# SCH_Hall_sensor_array_2022-12-20.net
KiCad netlist of a schematic drawn in EasyEDA
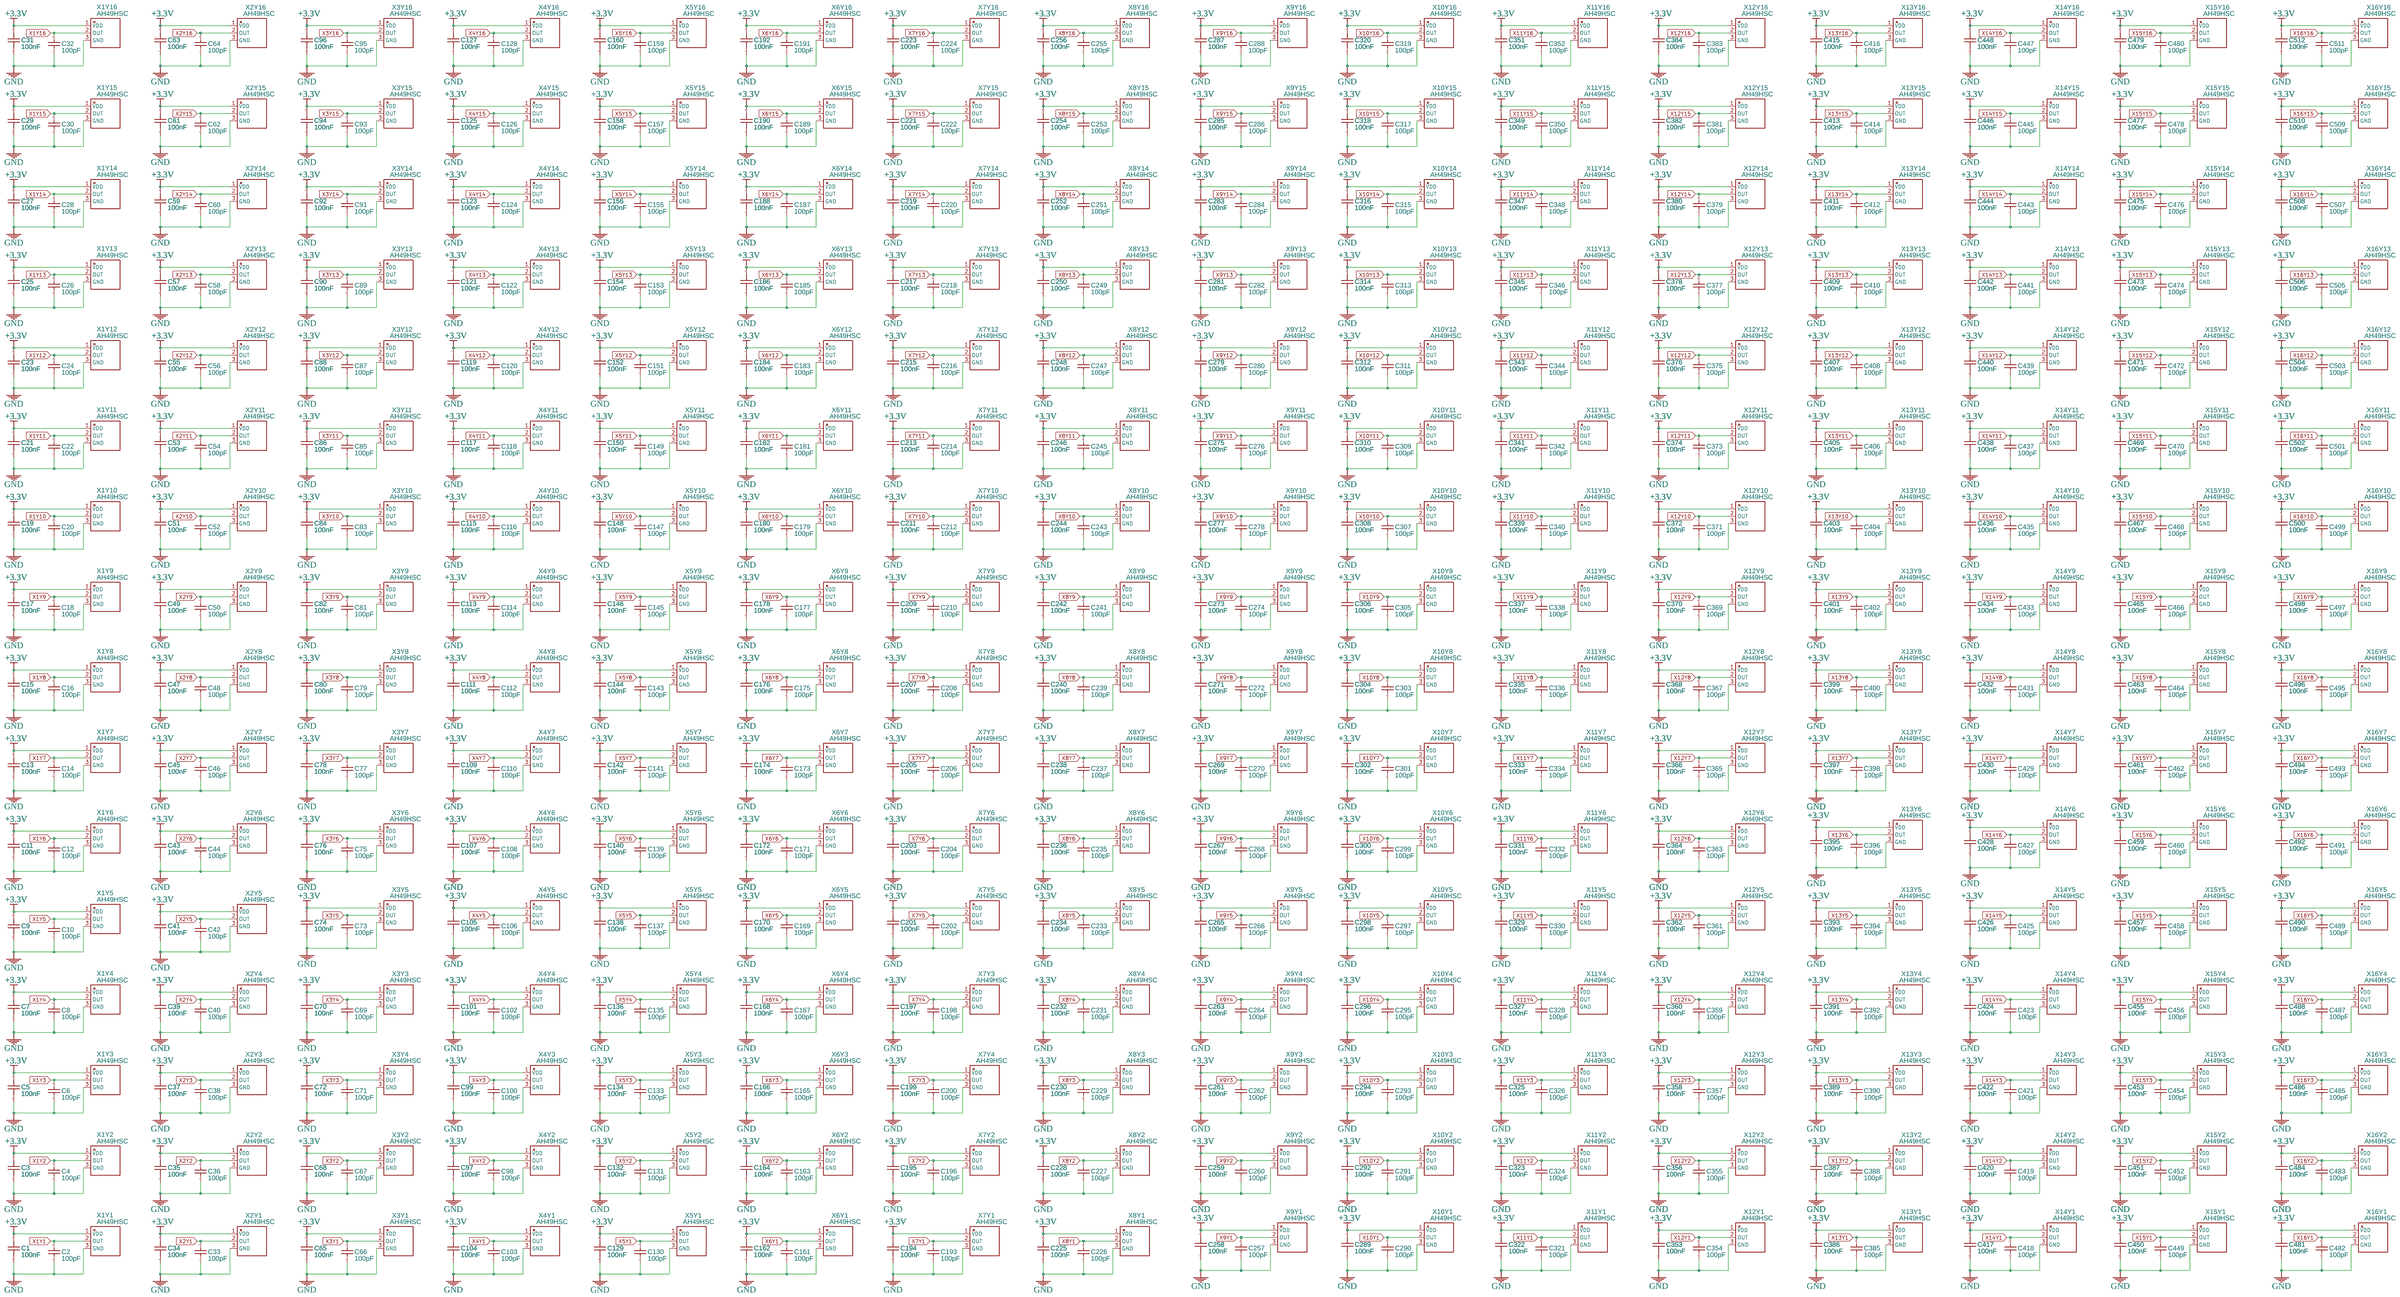
[diagram p0: schematic sheet]

(export (version "E")
  (design (tool "Eeschema 10.0.6"))
  (components
    (comp (ref "C1")
      (value "100nF")
      (fields
        (field (name "BOM_Manufacturer Part") "CL10B104KB8NNNC")
        (field (name "BOM_Supplier Part") "C1591")
      )
      (libsource (lib "") (part "CL10B104KB8NNNC"))
    )
    (comp (ref "C2")
      (value "100pF")
      (fields
        (field (name "BOM_Manufacturer Part") "CL10C101JB8NNNC")
        (field (name "BOM_Supplier Part") "C14858")
      )
      (libsource (lib "") (part "CL10C101JB8NNNC"))
    )
    (comp (ref "C3")
      (value "100nF")
      (fields
        (field (name "BOM_Manufacturer Part") "CL10B104KB8NNNC")
        (field (name "BOM_Supplier Part") "C1591")
      )
      (libsource (lib "") (part "CL10B104KB8NNNC"))
    )
    (comp (ref "C4")
      (value "100pF")
      (fields
        (field (name "BOM_Manufacturer Part") "CL10C101JB8NNNC")
        (field (name "BOM_Supplier Part") "C14858")
      )
      (libsource (lib "") (part "CL10C101JB8NNNC"))
    )
    (comp (ref "C5")
      (value "100nF")
      (fields
        (field (name "BOM_Manufacturer Part") "CL10B104KB8NNNC")
        (field (name "BOM_Supplier Part") "C1591")
      )
      (libsource (lib "") (part "CL10B104KB8NNNC"))
    )
    (comp (ref "C6")
      (value "100pF")
      (fields
        (field (name "BOM_Manufacturer Part") "CL10C101JB8NNNC")
        (field (name "BOM_Supplier Part") "C14858")
      )
      (libsource (lib "") (part "CL10C101JB8NNNC"))
    )
    (comp (ref "C7")
      (value "100nF")
      (fields
        (field (name "BOM_Manufacturer Part") "CL10B104KB8NNNC")
        (field (name "BOM_Supplier Part") "C1591")
      )
      (libsource (lib "") (part "CL10B104KB8NNNC"))
    )
    (comp (ref "C8")
      (value "100pF")
      (fields
        (field (name "BOM_Manufacturer Part") "CL10C101JB8NNNC")
        (field (name "BOM_Supplier Part") "C14858")
      )
      (libsource (lib "") (part "CL10C101JB8NNNC"))
    )
    (comp (ref "C9")
      (value "100nF")
      (fields
        (field (name "BOM_Manufacturer Part") "CL10B104KB8NNNC")
        (field (name "BOM_Supplier Part") "C1591")
      )
      (libsource (lib "") (part "CL10B104KB8NNNC"))
    )
    (comp (ref "C10")
      (value "100pF")
      (fields
        (field (name "BOM_Manufacturer Part") "CL10C101JB8NNNC")
        (field (name "BOM_Supplier Part") "C14858")
      )
      (libsource (lib "") (part "CL10C101JB8NNNC"))
    )
    (comp (ref "C11")
      (value "100nF")
      (fields
        (field (name "BOM_Manufacturer Part") "CL10B104KB8NNNC")
        (field (name "BOM_Supplier Part") "C1591")
      )
      (libsource (lib "") (part "CL10B104KB8NNNC"))
    )
    (comp (ref "C12")
      (value "100pF")
      (fields
        (field (name "BOM_Manufacturer Part") "CL10C101JB8NNNC")
        (field (name "BOM_Supplier Part") "C14858")
      )
      (libsource (lib "") (part "CL10C101JB8NNNC"))
    )
    (comp (ref "C13")
      (value "100nF")
      (fields
        (field (name "BOM_Manufacturer Part") "CL10B104KB8NNNC")
        (field (name "BOM_Supplier Part") "C1591")
      )
      (libsource (lib "") (part "CL10B104KB8NNNC"))
    )
    (comp (ref "C14")
      (value "100pF")
      (fields
        (field (name "BOM_Manufacturer Part") "CL10C101JB8NNNC")
        (field (name "BOM_Supplier Part") "C14858")
      )
      (libsource (lib "") (part "CL10C101JB8NNNC"))
    )
    (comp (ref "C15")
      (value "100nF")
      (fields
        (field (name "BOM_Manufacturer Part") "CL10B104KB8NNNC")
        (field (name "BOM_Supplier Part") "C1591")
      )
      (libsource (lib "") (part "CL10B104KB8NNNC"))
    )
    (comp (ref "C16")
      (value "100pF")
      (fields
        (field (name "BOM_Manufacturer Part") "CL10C101JB8NNNC")
        (field (name "BOM_Supplier Part") "C14858")
      )
      (libsource (lib "") (part "CL10C101JB8NNNC"))
    )
    (comp (ref "C17")
      (value "100nF")
      (fields
        (field (name "BOM_Manufacturer Part") "CL10B104KB8NNNC")
        (field (name "BOM_Supplier Part") "C1591")
      )
      (libsource (lib "") (part "CL10B104KB8NNNC"))
    )
    (comp (ref "C18")
      (value "100pF")
      (fields
        (field (name "BOM_Manufacturer Part") "CL10C101JB8NNNC")
        (field (name "BOM_Supplier Part") "C14858")
      )
      (libsource (lib "") (part "CL10C101JB8NNNC"))
    )
    (comp (ref "C19")
      (value "100nF")
      (fields
        (field (name "BOM_Manufacturer Part") "CL10B104KB8NNNC")
        (field (name "BOM_Supplier Part") "C1591")
      )
      (libsource (lib "") (part "CL10B104KB8NNNC"))
    )
    (comp (ref "C20")
      (value "100pF")
      (fields
        (field (name "BOM_Manufacturer Part") "CL10C101JB8NNNC")
        (field (name "BOM_Supplier Part") "C14858")
      )
      (libsource (lib "") (part "CL10C101JB8NNNC"))
    )
    (comp (ref "C21")
      (value "100nF")
      (fields
        (field (name "BOM_Manufacturer Part") "CL10B104KB8NNNC")
        (field (name "BOM_Supplier Part") "C1591")
      )
      (libsource (lib "") (part "CL10B104KB8NNNC"))
    )
    (comp (ref "C22")
      (value "100pF")
      (fields
        (field (name "BOM_Manufacturer Part") "CL10C101JB8NNNC")
        (field (name "BOM_Supplier Part") "C14858")
      )
      (libsource (lib "") (part "CL10C101JB8NNNC"))
    )
    (comp (ref "C23")
      (value "100nF")
      (fields
        (field (name "BOM_Manufacturer Part") "CL10B104KB8NNNC")
        (field (name "BOM_Supplier Part") "C1591")
      )
      (libsource (lib "") (part "CL10B104KB8NNNC"))
    )
    (comp (ref "C24")
      (value "100pF")
      (fields
        (field (name "BOM_Manufacturer Part") "CL10C101JB8NNNC")
        (field (name "BOM_Supplier Part") "C14858")
      )
      (libsource (lib "") (part "CL10C101JB8NNNC"))
    )
    (comp (ref "C25")
      (value "100nF")
      (fields
        (field (name "BOM_Manufacturer Part") "CL10B104KB8NNNC")
        (field (name "BOM_Supplier Part") "C1591")
      )
      (libsource (lib "") (part "CL10B104KB8NNNC"))
    )
    (comp (ref "C26")
      (value "100pF")
      (fields
        (field (name "BOM_Manufacturer Part") "CL10C101JB8NNNC")
        (field (name "BOM_Supplier Part") "C14858")
      )
      (libsource (lib "") (part "CL10C101JB8NNNC"))
    )
    (comp (ref "C27")
      (value "100nF")
      (fields
        (field (name "BOM_Manufacturer Part") "CL10B104KB8NNNC")
        (field (name "BOM_Supplier Part") "C1591")
      )
      (libsource (lib "") (part "CL10B104KB8NNNC"))
    )
    (comp (ref "C28")
      (value "100pF")
      (fields
        (field (name "BOM_Manufacturer Part") "CL10C101JB8NNNC")
        (field (name "BOM_Supplier Part") "C14858")
      )
      (libsource (lib "") (part "CL10C101JB8NNNC"))
    )
    (comp (ref "C29")
      (value "100nF")
      (fields
        (field (name "BOM_Manufacturer Part") "CL10B104KB8NNNC")
        (field (name "BOM_Supplier Part") "C1591")
      )
      (libsource (lib "") (part "CL10B104KB8NNNC"))
    )
    (comp (ref "C30")
      (value "100pF")
      (fields
        (field (name "BOM_Manufacturer Part") "CL10C101JB8NNNC")
        (field (name "BOM_Supplier Part") "C14858")
      )
      (libsource (lib "") (part "CL10C101JB8NNNC"))
    )
    (comp (ref "C31")
      (value "100nF")
      (fields
        (field (name "BOM_Manufacturer Part") "CL10B104KB8NNNC")
        (field (name "BOM_Supplier Part") "C1591")
      )
      (libsource (lib "") (part "CL10B104KB8NNNC"))
    )
    (comp (ref "C32")
      (value "100pF")
      (fields
        (field (name "BOM_Manufacturer Part") "CL10C101JB8NNNC")
        (field (name "BOM_Supplier Part") "C14858")
      )
      (libsource (lib "") (part "CL10C101JB8NNNC"))
    )
    (comp (ref "C33")
      (value "100pF")
      (fields
        (field (name "BOM_Manufacturer Part") "CL10C101JB8NNNC")
        (field (name "BOM_Supplier Part") "C14858")
      )
      (libsource (lib "") (part "CL10C101JB8NNNC"))
    )
    (comp (ref "C34")
      (value "100nF")
      (fields
        (field (name "BOM_Manufacturer Part") "CL10B104KB8NNNC")
        (field (name "BOM_Supplier Part") "C1591")
      )
      (libsource (lib "") (part "CL10B104KB8NNNC"))
    )
    (comp (ref "C35")
      (value "100nF")
      (fields
        (field (name "BOM_Manufacturer Part") "CL10B104KB8NNNC")
        (field (name "BOM_Supplier Part") "C1591")
      )
      (libsource (lib "") (part "CL10B104KB8NNNC"))
    )
    (comp (ref "C36")
      (value "100pF")
      (fields
        (field (name "BOM_Manufacturer Part") "CL10C101JB8NNNC")
        (field (name "BOM_Supplier Part") "C14858")
      )
      (libsource (lib "") (part "CL10C101JB8NNNC"))
    )
    (comp (ref "C37")
      (value "100nF")
      (fields
        (field (name "BOM_Manufacturer Part") "CL10B104KB8NNNC")
        (field (name "BOM_Supplier Part") "C1591")
      )
      (libsource (lib "") (part "CL10B104KB8NNNC"))
    )
    (comp (ref "C38")
      (value "100pF")
      (fields
        (field (name "BOM_Manufacturer Part") "CL10C101JB8NNNC")
        (field (name "BOM_Supplier Part") "C14858")
      )
      (libsource (lib "") (part "CL10C101JB8NNNC"))
    )
    (comp (ref "C39")
      (value "100nF")
      (fields
        (field (name "BOM_Manufacturer Part") "CL10B104KB8NNNC")
        (field (name "BOM_Supplier Part") "C1591")
      )
      (libsource (lib "") (part "CL10B104KB8NNNC"))
    )
    (comp (ref "C40")
      (value "100pF")
      (fields
        (field (name "BOM_Manufacturer Part") "CL10C101JB8NNNC")
        (field (name "BOM_Supplier Part") "C14858")
      )
      (libsource (lib "") (part "CL10C101JB8NNNC"))
    )
    (comp (ref "C41")
      (value "100nF")
      (fields
        (field (name "BOM_Manufacturer Part") "CL10B104KB8NNNC")
        (field (name "BOM_Supplier Part") "C1591")
      )
      (libsource (lib "") (part "CL10B104KB8NNNC"))
    )
    (comp (ref "C42")
      (value "100pF")
      (fields
        (field (name "BOM_Manufacturer Part") "CL10C101JB8NNNC")
        (field (name "BOM_Supplier Part") "C14858")
      )
      (libsource (lib "") (part "CL10C101JB8NNNC"))
    )
    (comp (ref "C43")
      (value "100nF")
      (fields
        (field (name "BOM_Manufacturer Part") "CL10B104KB8NNNC")
        (field (name "BOM_Supplier Part") "C1591")
      )
      (libsource (lib "") (part "CL10B104KB8NNNC"))
    )
    (comp (ref "C44")
      (value "100pF")
      (fields
        (field (name "BOM_Manufacturer Part") "CL10C101JB8NNNC")
        (field (name "BOM_Supplier Part") "C14858")
      )
      (libsource (lib "") (part "CL10C101JB8NNNC"))
    )
    (comp (ref "C45")
      (value "100nF")
      (fields
        (field (name "BOM_Manufacturer Part") "CL10B104KB8NNNC")
        (field (name "BOM_Supplier Part") "C1591")
      )
      (libsource (lib "") (part "CL10B104KB8NNNC"))
    )
    (comp (ref "C46")
      (value "100pF")
      (fields
        (field (name "BOM_Manufacturer Part") "CL10C101JB8NNNC")
        (field (name "BOM_Supplier Part") "C14858")
      )
      (libsource (lib "") (part "CL10C101JB8NNNC"))
    )
    (comp (ref "C47")
      (value "100nF")
      (fields
        (field (name "BOM_Manufacturer Part") "CL10B104KB8NNNC")
        (field (name "BOM_Supplier Part") "C1591")
      )
      (libsource (lib "") (part "CL10B104KB8NNNC"))
    )
    (comp (ref "C48")
      (value "100pF")
      (fields
        (field (name "BOM_Manufacturer Part") "CL10C101JB8NNNC")
        (field (name "BOM_Supplier Part") "C14858")
      )
      (libsource (lib "") (part "CL10C101JB8NNNC"))
    )
    (comp (ref "C49")
      (value "100nF")
      (fields
        (field (name "BOM_Manufacturer Part") "CL10B104KB8NNNC")
        (field (name "BOM_Supplier Part") "C1591")
      )
      (libsource (lib "") (part "CL10B104KB8NNNC"))
    )
    (comp (ref "C50")
      (value "100pF")
      (fields
        (field (name "BOM_Manufacturer Part") "CL10C101JB8NNNC")
        (field (name "BOM_Supplier Part") "C14858")
      )
      (libsource (lib "") (part "CL10C101JB8NNNC"))
    )
    (comp (ref "C51")
      (value "100nF")
      (fields
        (field (name "BOM_Manufacturer Part") "CL10B104KB8NNNC")
        (field (name "BOM_Supplier Part") "C1591")
      )
      (libsource (lib "") (part "CL10B104KB8NNNC"))
    )
    (comp (ref "C52")
      (value "100pF")
      (fields
        (field (name "BOM_Manufacturer Part") "CL10C101JB8NNNC")
        (field (name "BOM_Supplier Part") "C14858")
      )
      (libsource (lib "") (part "CL10C101JB8NNNC"))
    )
    (comp (ref "C53")
      (value "100nF")
      (fields
        (field (name "BOM_Manufacturer Part") "CL10B104KB8NNNC")
        (field (name "BOM_Supplier Part") "C1591")
      )
      (libsource (lib "") (part "CL10B104KB8NNNC"))
    )
    (comp (ref "C54")
      (value "100pF")
      (fields
        (field (name "BOM_Manufacturer Part") "CL10C101JB8NNNC")
        (field (name "BOM_Supplier Part") "C14858")
      )
      (libsource (lib "") (part "CL10C101JB8NNNC"))
    )
    (comp (ref "C55")
      (value "100nF")
      (fields
        (field (name "BOM_Manufacturer Part") "CL10B104KB8NNNC")
        (field (name "BOM_Supplier Part") "C1591")
      )
      (libsource (lib "") (part "CL10B104KB8NNNC"))
    )
    (comp (ref "C56")
      (value "100pF")
      (fields
        (field (name "BOM_Manufacturer Part") "CL10C101JB8NNNC")
        (field (name "BOM_Supplier Part") "C14858")
      )
      (libsource (lib "") (part "CL10C101JB8NNNC"))
    )
    (comp (ref "C57")
      (value "100nF")
      (fields
        (field (name "BOM_Manufacturer Part") "CL10B104KB8NNNC")
        (field (name "BOM_Supplier Part") "C1591")
      )
      (libsource (lib "") (part "CL10B104KB8NNNC"))
    )
    (comp (ref "C58")
      (value "100pF")
      (fields
        (field (name "BOM_Manufacturer Part") "CL10C101JB8NNNC")
        (field (name "BOM_Supplier Part") "C14858")
      )
      (libsource (lib "") (part "CL10C101JB8NNNC"))
    )
    (comp (ref "C59")
      (value "100nF")
      (fields
        (field (name "BOM_Manufacturer Part") "CL10B104KB8NNNC")
        (field (name "BOM_Supplier Part") "C1591")
      )
      (libsource (lib "") (part "CL10B104KB8NNNC"))
    )
    (comp (ref "C60")
      (value "100pF")
      (fields
        (field (name "BOM_Manufacturer Part") "CL10C101JB8NNNC")
        (field (name "BOM_Supplier Part") "C14858")
      )
      (libsource (lib "") (part "CL10C101JB8NNNC"))
    )
    (comp (ref "C61")
      (value "100nF")
      (fields
        (field (name "BOM_Manufacturer Part") "CL10B104KB8NNNC")
        (field (name "BOM_Supplier Part") "C1591")
      )
      (libsource (lib "") (part "CL10B104KB8NNNC"))
    )
    (comp (ref "C62")
      (value "100pF")
      (fields
        (field (name "BOM_Manufacturer Part") "CL10C101JB8NNNC")
        (field (name "BOM_Supplier Part") "C14858")
      )
      (libsource (lib "") (part "CL10C101JB8NNNC"))
    )
    (comp (ref "C63")
      (value "100nF")
      (fields
        (field (name "BOM_Manufacturer Part") "CL10B104KB8NNNC")
        (field (name "BOM_Supplier Part") "C1591")
      )
      (libsource (lib "") (part "CL10B104KB8NNNC"))
    )
    (comp (ref "C64")
      (value "100pF")
      (fields
        (field (name "BOM_Manufacturer Part") "CL10C101JB8NNNC")
        (field (name "BOM_Supplier Part") "C14858")
      )
      (libsource (lib "") (part "CL10C101JB8NNNC"))
    )
    (comp (ref "C65")
      (value "100nF")
      (fields
        (field (name "BOM_Manufacturer Part") "CL10B104KB8NNNC")
        (field (name "BOM_Supplier Part") "C1591")
      )
      (libsource (lib "") (part "CL10B104KB8NNNC"))
    )
    (comp (ref "C66")
      (value "100pF")
      (fields
        (field (name "BOM_Manufacturer Part") "CL10C101JB8NNNC")
        (field (name "BOM_Supplier Part") "C14858")
      )
      (libsource (lib "") (part "CL10C101JB8NNNC"))
    )
    (comp (ref "C67")
      (value "100pF")
      (fields
        (field (name "BOM_Manufacturer Part") "CL10C101JB8NNNC")
        (field (name "BOM_Supplier Part") "C14858")
      )
      (libsource (lib "") (part "CL10C101JB8NNNC"))
    )
    (comp (ref "C68")
      (value "100nF")
      (fields
        (field (name "BOM_Manufacturer Part") "CL10B104KB8NNNC")
        (field (name "BOM_Supplier Part") "C1591")
      )
      (libsource (lib "") (part "CL10B104KB8NNNC"))
    )
    (comp (ref "C69")
      (value "100pF")
      (fields
        (field (name "BOM_Manufacturer Part") "CL10C101JB8NNNC")
        (field (name "BOM_Supplier Part") "C14858")
      )
      (libsource (lib "") (part "CL10C101JB8NNNC"))
    )
    (comp (ref "C70")
      (value "100nF")
      (fields
        (field (name "BOM_Manufacturer Part") "CL10B104KB8NNNC")
        (field (name "BOM_Supplier Part") "C1591")
      )
      (libsource (lib "") (part "CL10B104KB8NNNC"))
    )
    (comp (ref "C71")
      (value "100pF")
      (fields
        (field (name "BOM_Manufacturer Part") "CL10C101JB8NNNC")
        (field (name "BOM_Supplier Part") "C14858")
      )
      (libsource (lib "") (part "CL10C101JB8NNNC"))
    )
    (comp (ref "C72")
      (value "100nF")
      (fields
        (field (name "BOM_Manufacturer Part") "CL10B104KB8NNNC")
        (field (name "BOM_Supplier Part") "C1591")
      )
      (libsource (lib "") (part "CL10B104KB8NNNC"))
    )
    (comp (ref "C73")
      (value "100pF")
      (fields
        (field (name "BOM_Manufacturer Part") "CL10C101JB8NNNC")
        (field (name "BOM_Supplier Part") "C14858")
      )
      (libsource (lib "") (part "CL10C101JB8NNNC"))
    )
    (comp (ref "C74")
      (value "100nF")
      (fields
        (field (name "BOM_Manufacturer Part") "CL10B104KB8NNNC")
        (field (name "BOM_Supplier Part") "C1591")
      )
      (libsource (lib "") (part "CL10B104KB8NNNC"))
    )
    (comp (ref "C75")
      (value "100pF")
      (fields
        (field (name "BOM_Manufacturer Part") "CL10C101JB8NNNC")
        (field (name "BOM_Supplier Part") "C14858")
      )
      (libsource (lib "") (part "CL10C101JB8NNNC"))
    )
    (comp (ref "C76")
      (value "100nF")
      (fields
        (field (name "BOM_Manufacturer Part") "CL10B104KB8NNNC")
        (field (name "BOM_Supplier Part") "C1591")
      )
      (libsource (lib "") (part "CL10B104KB8NNNC"))
    )
    (comp (ref "C77")
      (value "100pF")
      (fields
        (field (name "BOM_Manufacturer Part") "CL10C101JB8NNNC")
        (field (name "BOM_Supplier Part") "C14858")
      )
      (libsource (lib "") (part "CL10C101JB8NNNC"))
    )
    (comp (ref "C78")
      (value "100nF")
      (fields
        (field (name "BOM_Manufacturer Part") "CL10B104KB8NNNC")
        (field (name "BOM_Supplier Part") "C1591")
      )
      (libsource (lib "") (part "CL10B104KB8NNNC"))
    )
    (comp (ref "C79")
      (value "100pF")
      (fields
        (field (name "BOM_Manufacturer Part") "CL10C101JB8NNNC")
        (field (name "BOM_Supplier Part") "C14858")
      )
      (libsource (lib "") (part "CL10C101JB8NNNC"))
    )
    (comp (ref "C80")
      (value "100nF")
      (fields
        (field (name "BOM_Manufacturer Part") "CL10B104KB8NNNC")
        (field (name "BOM_Supplier Part") "C1591")
      )
      (libsource (lib "") (part "CL10B104KB8NNNC"))
    )
    (comp (ref "C81")
      (value "100pF")
      (fields
        (field (name "BOM_Manufacturer Part") "CL10C101JB8NNNC")
        (field (name "BOM_Supplier Part") "C14858")
      )
      (libsource (lib "") (part "CL10C101JB8NNNC"))
    )
    (comp (ref "C82")
      (value "100nF")
      (fields
        (field (name "BOM_Manufacturer Part") "CL10B104KB8NNNC")
        (field (name "BOM_Supplier Part") "C1591")
      )
      (libsource (lib "") (part "CL10B104KB8NNNC"))
    )
    (comp (ref "C83")
      (value "100pF")
      (fields
        (field (name "BOM_Manufacturer Part") "CL10C101JB8NNNC")
        (field (name "BOM_Supplier Part") "C14858")
      )
      (libsource (lib "") (part "CL10C101JB8NNNC"))
    )
    (comp (ref "C84")
      (value "100nF")
      (fields
        (field (name "BOM_Manufacturer Part") "CL10B104KB8NNNC")
        (field (name "BOM_Supplier Part") "C1591")
      )
      (libsource (lib "") (part "CL10B104KB8NNNC"))
    )
    (comp (ref "C85")
      (value "100pF")
      (fields
        (field (name "BOM_Manufacturer Part") "CL10C101JB8NNNC")
        (field (name "BOM_Supplier Part") "C14858")
      )
      (libsource (lib "") (part "CL10C101JB8NNNC"))
    )
    (comp (ref "C86")
      (value "100nF")
      (fields
        (field (name "BOM_Manufacturer Part") "CL10B104KB8NNNC")
        (field (name "BOM_Supplier Part") "C1591")
      )
      (libsource (lib "") (part "CL10B104KB8NNNC"))
    )
    (comp (ref "C87")
      (value "100pF")
      (fields
        (field (name "BOM_Manufacturer Part") "CL10C101JB8NNNC")
        (field (name "BOM_Supplier Part") "C14858")
      )
      (libsource (lib "") (part "CL10C101JB8NNNC"))
    )
    (comp (ref "C88")
      (value "100nF")
      (fields
        (field (name "BOM_Manufacturer Part") "CL10B104KB8NNNC")
        (field (name "BOM_Supplier Part") "C1591")
      )
      (libsource (lib "") (part "CL10B104KB8NNNC"))
    )
    (comp (ref "C89")
      (value "100pF")
      (fields
        (field (name "BOM_Manufacturer Part") "CL10C101JB8NNNC")
        (field (name "BOM_Supplier Part") "C14858")
      )
      (libsource (lib "") (part "CL10C101JB8NNNC"))
    )
    (comp (ref "C90")
      (value "100nF")
      (fields
        (field (name "BOM_Manufacturer Part") "CL10B104KB8NNNC")
        (field (name "BOM_Supplier Part") "C1591")
      )
      (libsource (lib "") (part "CL10B104KB8NNNC"))
    )
    (comp (ref "C91")
      (value "100pF")
      (fields
        (field (name "BOM_Manufacturer Part") "CL10C101JB8NNNC")
        (field (name "BOM_Supplier Part") "C14858")
      )
      (libsource (lib "") (part "CL10C101JB8NNNC"))
    )
    (comp (ref "C92")
      (value "100nF")
      (fields
        (field (name "BOM_Manufacturer Part") "CL10B104KB8NNNC")
        (field (name "BOM_Supplier Part") "C1591")
      )
      (libsource (lib "") (part "CL10B104KB8NNNC"))
    )
    (comp (ref "C93")
      (value "100pF")
      (fields
        (field (name "BOM_Manufacturer Part") "CL10C101JB8NNNC")
        (field (name "BOM_Supplier Part") "C14858")
      )
      (libsource (lib "") (part "CL10C101JB8NNNC"))
    )
    (comp (ref "C94")
      (value "100nF")
      (fields
        (field (name "BOM_Manufacturer Part") "CL10B104KB8NNNC")
        (field (name "BOM_Supplier Part") "C1591")
      )
      (libsource (lib "") (part "CL10B104KB8NNNC"))
    )
    (comp (ref "C95")
      (value "100pF")
      (fields
        (field (name "BOM_Manufacturer Part") "CL10C101JB8NNNC")
        (field (name "BOM_Supplier Part") "C14858")
      )
      (libsource (lib "") (part "CL10C101JB8NNNC"))
    )
    (comp (ref "C96")
      (value "100nF")
      (fields
        (field (name "BOM_Manufacturer Part") "CL10B104KB8NNNC")
        (field (name "BOM_Supplier Part") "C1591")
      )
      (libsource (lib "") (part "CL10B104KB8NNNC"))
    )
    (comp (ref "C97")
      (value "100nF")
      (fields
        (field (name "BOM_Manufacturer Part") "CL10B104KB8NNNC")
        (field (name "BOM_Supplier Part") "C1591")
      )
      (libsource (lib "") (part "CL10B104KB8NNNC"))
    )
    (comp (ref "C98")
      (value "100pF")
      (fields
        (field (name "BOM_Manufacturer Part") "CL10C101JB8NNNC")
        (field (name "BOM_Supplier Part") "C14858")
      )
      (libsource (lib "") (part "CL10C101JB8NNNC"))
    )
    (comp (ref "C99")
      (value "100nF")
      (fields
        (field (name "BOM_Manufacturer Part") "CL10B104KB8NNNC")
        (field (name "BOM_Supplier Part") "C1591")
      )
      (libsource (lib "") (part "CL10B104KB8NNNC"))
    )
    (comp (ref "C100")
      (value "100pF")
      (fields
        (field (name "BOM_Manufacturer Part") "CL10C101JB8NNNC")
        (field (name "BOM_Supplier Part") "C14858")
      )
      (libsource (lib "") (part "CL10C101JB8NNNC"))
    )
    (comp (ref "C101")
      (value "100nF")
      (fields
        (field (name "BOM_Manufacturer Part") "CL10B104KB8NNNC")
        (field (name "BOM_Supplier Part") "C1591")
      )
      (libsource (lib "") (part "CL10B104KB8NNNC"))
    )
    (comp (ref "C102")
      (value "100pF")
      (fields
        (field (name "BOM_Manufacturer Part") "CL10C101JB8NNNC")
        (field (name "BOM_Supplier Part") "C14858")
      )
      (libsource (lib "") (part "CL10C101JB8NNNC"))
    )
    (comp (ref "C103")
      (value "100pF")
      (fields
        (field (name "BOM_Manufacturer Part") "CL10C101JB8NNNC")
        (field (name "BOM_Supplier Part") "C14858")
      )
      (libsource (lib "") (part "CL10C101JB8NNNC"))
    )
    (comp (ref "C104")
      (value "100nF")
      (fields
        (field (name "BOM_Manufacturer Part") "CL10B104KB8NNNC")
        (field (name "BOM_Supplier Part") "C1591")
      )
      (libsource (lib "") (part "CL10B104KB8NNNC"))
    )
    (comp (ref "C105")
      (value "100nF")
      (fields
        (field (name "BOM_Manufacturer Part") "CL10B104KB8NNNC")
        (field (name "BOM_Supplier Part") "C1591")
      )
      (libsource (lib "") (part "CL10B104KB8NNNC"))
    )
    (comp (ref "C106")
      (value "100pF")
      (fields
        (field (name "BOM_Manufacturer Part") "CL10C101JB8NNNC")
        (field (name "BOM_Supplier Part") "C14858")
      )
      (libsource (lib "") (part "CL10C101JB8NNNC"))
    )
    (comp (ref "C107")
      (value "100nF")
      (fields
        (field (name "BOM_Manufacturer Part") "CL10B104KB8NNNC")
        (field (name "BOM_Supplier Part") "C1591")
      )
      (libsource (lib "") (part "CL10B104KB8NNNC"))
    )
    (comp (ref "C108")
      (value "100pF")
      (fields
        (field (name "BOM_Manufacturer Part") "CL10C101JB8NNNC")
        (field (name "BOM_Supplier Part") "C14858")
      )
      (libsource (lib "") (part "CL10C101JB8NNNC"))
    )
    (comp (ref "C109")
      (value "100nF")
      (fields
        (field (name "BOM_Manufacturer Part") "CL10B104KB8NNNC")
        (field (name "BOM_Supplier Part") "C1591")
      )
      (libsource (lib "") (part "CL10B104KB8NNNC"))
    )
    (comp (ref "C110")
      (value "100pF")
      (fields
        (field (name "BOM_Manufacturer Part") "CL10C101JB8NNNC")
        (field (name "BOM_Supplier Part") "C14858")
      )
      (libsource (lib "") (part "CL10C101JB8NNNC"))
    )
    (comp (ref "C111")
      (value "100nF")
      (fields
        (field (name "BOM_Manufacturer Part") "CL10B104KB8NNNC")
        (field (name "BOM_Supplier Part") "C1591")
      )
      (libsource (lib "") (part "CL10B104KB8NNNC"))
    )
    (comp (ref "C112")
      (value "100pF")
      (fields
        (field (name "BOM_Manufacturer Part") "CL10C101JB8NNNC")
        (field (name "BOM_Supplier Part") "C14858")
      )
      (libsource (lib "") (part "CL10C101JB8NNNC"))
    )
    (comp (ref "C113")
      (value "100nF")
      (fields
        (field (name "BOM_Manufacturer Part") "CL10B104KB8NNNC")
        (field (name "BOM_Supplier Part") "C1591")
      )
      (libsource (lib "") (part "CL10B104KB8NNNC"))
    )
    (comp (ref "C114")
      (value "100pF")
      (fields
        (field (name "BOM_Manufacturer Part") "CL10C101JB8NNNC")
        (field (name "BOM_Supplier Part") "C14858")
      )
      (libsource (lib "") (part "CL10C101JB8NNNC"))
    )
    (comp (ref "C115")
      (value "100nF")
      (fields
        (field (name "BOM_Manufacturer Part") "CL10B104KB8NNNC")
        (field (name "BOM_Supplier Part") "C1591")
      )
      (libsource (lib "") (part "CL10B104KB8NNNC"))
    )
    (comp (ref "C116")
      (value "100pF")
      (fields
        (field (name "BOM_Manufacturer Part") "CL10C101JB8NNNC")
        (field (name "BOM_Supplier Part") "C14858")
      )
      (libsource (lib "") (part "CL10C101JB8NNNC"))
    )
    (comp (ref "C117")
      (value "100nF")
      (fields
        (field (name "BOM_Manufacturer Part") "CL10B104KB8NNNC")
        (field (name "BOM_Supplier Part") "C1591")
      )
      (libsource (lib "") (part "CL10B104KB8NNNC"))
    )
    (comp (ref "C118")
      (value "100pF")
      (fields
        (field (name "BOM_Manufacturer Part") "CL10C101JB8NNNC")
        (field (name "BOM_Supplier Part") "C14858")
      )
      (libsource (lib "") (part "CL10C101JB8NNNC"))
    )
    (comp (ref "C119")
      (value "100nF")
      (fields
        (field (name "BOM_Manufacturer Part") "CL10B104KB8NNNC")
        (field (name "BOM_Supplier Part") "C1591")
      )
      (libsource (lib "") (part "CL10B104KB8NNNC"))
    )
    (comp (ref "C120")
      (value "100pF")
      (fields
        (field (name "BOM_Manufacturer Part") "CL10C101JB8NNNC")
        (field (name "BOM_Supplier Part") "C14858")
      )
      (libsource (lib "") (part "CL10C101JB8NNNC"))
    )
    (comp (ref "C121")
      (value "100nF")
      (fields
        (field (name "BOM_Manufacturer Part") "CL10B104KB8NNNC")
        (field (name "BOM_Supplier Part") "C1591")
      )
      (libsource (lib "") (part "CL10B104KB8NNNC"))
    )
    (comp (ref "C122")
      (value "100pF")
      (fields
        (field (name "BOM_Manufacturer Part") "CL10C101JB8NNNC")
        (field (name "BOM_Supplier Part") "C14858")
      )
      (libsource (lib "") (part "CL10C101JB8NNNC"))
    )
    (comp (ref "C123")
      (value "100nF")
      (fields
        (field (name "BOM_Manufacturer Part") "CL10B104KB8NNNC")
        (field (name "BOM_Supplier Part") "C1591")
      )
      (libsource (lib "") (part "CL10B104KB8NNNC"))
    )
    (comp (ref "C124")
      (value "100pF")
      (fields
        (field (name "BOM_Manufacturer Part") "CL10C101JB8NNNC")
        (field (name "BOM_Supplier Part") "C14858")
      )
      (libsource (lib "") (part "CL10C101JB8NNNC"))
    )
    (comp (ref "C125")
      (value "100nF")
      (fields
        (field (name "BOM_Manufacturer Part") "CL10B104KB8NNNC")
        (field (name "BOM_Supplier Part") "C1591")
      )
      (libsource (lib "") (part "CL10B104KB8NNNC"))
    )
    (comp (ref "C126")
      (value "100pF")
      (fields
        (field (name "BOM_Manufacturer Part") "CL10C101JB8NNNC")
        (field (name "BOM_Supplier Part") "C14858")
      )
      (libsource (lib "") (part "CL10C101JB8NNNC"))
    )
    (comp (ref "C127")
      (value "100nF")
      (fields
        (field (name "BOM_Manufacturer Part") "CL10B104KB8NNNC")
        (field (name "BOM_Supplier Part") "C1591")
      )
      (libsource (lib "") (part "CL10B104KB8NNNC"))
    )
    (comp (ref "C128")
      (value "100pF")
      (fields
        (field (name "BOM_Manufacturer Part") "CL10C101JB8NNNC")
        (field (name "BOM_Supplier Part") "C14858")
      )
      (libsource (lib "") (part "CL10C101JB8NNNC"))
    )
    (comp (ref "C129")
      (value "100nF")
      (fields
        (field (name "BOM_Manufacturer Part") "CL10B104KB8NNNC")
        (field (name "BOM_Supplier Part") "C1591")
      )
      (libsource (lib "") (part "CL10B104KB8NNNC"))
    )
    (comp (ref "C130")
      (value "100pF")
      (fields
        (field (name "BOM_Manufacturer Part") "CL10C101JB8NNNC")
        (field (name "BOM_Supplier Part") "C14858")
      )
      (libsource (lib "") (part "CL10C101JB8NNNC"))
    )
    (comp (ref "C131")
      (value "100pF")
      (fields
        (field (name "BOM_Manufacturer Part") "CL10C101JB8NNNC")
        (field (name "BOM_Supplier Part") "C14858")
      )
      (libsource (lib "") (part "CL10C101JB8NNNC"))
    )
    (comp (ref "C132")
      (value "100nF")
      (fields
        (field (name "BOM_Manufacturer Part") "CL10B104KB8NNNC")
        (field (name "BOM_Supplier Part") "C1591")
      )
      (libsource (lib "") (part "CL10B104KB8NNNC"))
    )
    (comp (ref "C133")
      (value "100pF")
      (fields
        (field (name "BOM_Manufacturer Part") "CL10C101JB8NNNC")
        (field (name "BOM_Supplier Part") "C14858")
      )
      (libsource (lib "") (part "CL10C101JB8NNNC"))
    )
    (comp (ref "C134")
      (value "100nF")
      (fields
        (field (name "BOM_Manufacturer Part") "CL10B104KB8NNNC")
        (field (name "BOM_Supplier Part") "C1591")
      )
      (libsource (lib "") (part "CL10B104KB8NNNC"))
    )
    (comp (ref "C135")
      (value "100pF")
      (fields
        (field (name "BOM_Manufacturer Part") "CL10C101JB8NNNC")
        (field (name "BOM_Supplier Part") "C14858")
      )
      (libsource (lib "") (part "CL10C101JB8NNNC"))
    )
    (comp (ref "C136")
      (value "100nF")
      (fields
        (field (name "BOM_Manufacturer Part") "CL10B104KB8NNNC")
        (field (name "BOM_Supplier Part") "C1591")
      )
      (libsource (lib "") (part "CL10B104KB8NNNC"))
    )
    (comp (ref "C137")
      (value "100pF")
      (fields
        (field (name "BOM_Manufacturer Part") "CL10C101JB8NNNC")
        (field (name "BOM_Supplier Part") "C14858")
      )
      (libsource (lib "") (part "CL10C101JB8NNNC"))
    )
    (comp (ref "C138")
      (value "100nF")
      (fields
        (field (name "BOM_Manufacturer Part") "CL10B104KB8NNNC")
        (field (name "BOM_Supplier Part") "C1591")
      )
      (libsource (lib "") (part "CL10B104KB8NNNC"))
    )
    (comp (ref "C139")
      (value "100pF")
      (fields
        (field (name "BOM_Manufacturer Part") "CL10C101JB8NNNC")
        (field (name "BOM_Supplier Part") "C14858")
      )
      (libsource (lib "") (part "CL10C101JB8NNNC"))
    )
    (comp (ref "C140")
      (value "100nF")
      (fields
        (field (name "BOM_Manufacturer Part") "CL10B104KB8NNNC")
        (field (name "BOM_Supplier Part") "C1591")
      )
      (libsource (lib "") (part "CL10B104KB8NNNC"))
    )
    (comp (ref "C141")
      (value "100pF")
      (fields
        (field (name "BOM_Manufacturer Part") "CL10C101JB8NNNC")
        (field (name "BOM_Supplier Part") "C14858")
      )
      (libsource (lib "") (part "CL10C101JB8NNNC"))
    )
    (comp (ref "C142")
      (value "100nF")
      (fields
        (field (name "BOM_Manufacturer Part") "CL10B104KB8NNNC")
        (field (name "BOM_Supplier Part") "C1591")
      )
      (libsource (lib "") (part "CL10B104KB8NNNC"))
    )
    (comp (ref "C143")
      (value "100pF")
      (fields
        (field (name "BOM_Manufacturer Part") "CL10C101JB8NNNC")
        (field (name "BOM_Supplier Part") "C14858")
      )
      (libsource (lib "") (part "CL10C101JB8NNNC"))
    )
    (comp (ref "C144")
      (value "100nF")
      (fields
        (field (name "BOM_Manufacturer Part") "CL10B104KB8NNNC")
        (field (name "BOM_Supplier Part") "C1591")
      )
      (libsource (lib "") (part "CL10B104KB8NNNC"))
    )
    (comp (ref "C145")
      (value "100pF")
      (fields
        (field (name "BOM_Manufacturer Part") "CL10C101JB8NNNC")
        (field (name "BOM_Supplier Part") "C14858")
      )
      (libsource (lib "") (part "CL10C101JB8NNNC"))
    )
    (comp (ref "C146")
      (value "100nF")
      (fields
        (field (name "BOM_Manufacturer Part") "CL10B104KB8NNNC")
        (field (name "BOM_Supplier Part") "C1591")
      )
      (libsource (lib "") (part "CL10B104KB8NNNC"))
    )
    (comp (ref "C147")
      (value "100pF")
      (fields
        (field (name "BOM_Manufacturer Part") "CL10C101JB8NNNC")
        (field (name "BOM_Supplier Part") "C14858")
      )
      (libsource (lib "") (part "CL10C101JB8NNNC"))
    )
    (comp (ref "C148")
      (value "100nF")
      (fields
        (field (name "BOM_Manufacturer Part") "CL10B104KB8NNNC")
        (field (name "BOM_Supplier Part") "C1591")
      )
      (libsource (lib "") (part "CL10B104KB8NNNC"))
    )
    (comp (ref "C149")
      (value "100pF")
      (fields
        (field (name "BOM_Manufacturer Part") "CL10C101JB8NNNC")
        (field (name "BOM_Supplier Part") "C14858")
      )
      (libsource (lib "") (part "CL10C101JB8NNNC"))
    )
    (comp (ref "C150")
      (value "100nF")
      (fields
        (field (name "BOM_Manufacturer Part") "CL10B104KB8NNNC")
        (field (name "BOM_Supplier Part") "C1591")
      )
      (libsource (lib "") (part "CL10B104KB8NNNC"))
    )
    (comp (ref "C151")
      (value "100pF")
      (fields
        (field (name "BOM_Manufacturer Part") "CL10C101JB8NNNC")
        (field (name "BOM_Supplier Part") "C14858")
      )
      (libsource (lib "") (part "CL10C101JB8NNNC"))
    )
    (comp (ref "C152")
      (value "100nF")
      (fields
        (field (name "BOM_Manufacturer Part") "CL10B104KB8NNNC")
        (field (name "BOM_Supplier Part") "C1591")
      )
      (libsource (lib "") (part "CL10B104KB8NNNC"))
    )
    (comp (ref "C153")
      (value "100pF")
      (fields
        (field (name "BOM_Manufacturer Part") "CL10C101JB8NNNC")
        (field (name "BOM_Supplier Part") "C14858")
      )
      (libsource (lib "") (part "CL10C101JB8NNNC"))
    )
    (comp (ref "C154")
      (value "100nF")
      (fields
        (field (name "BOM_Manufacturer Part") "CL10B104KB8NNNC")
        (field (name "BOM_Supplier Part") "C1591")
      )
      (libsource (lib "") (part "CL10B104KB8NNNC"))
    )
    (comp (ref "C155")
      (value "100pF")
      (fields
        (field (name "BOM_Manufacturer Part") "CL10C101JB8NNNC")
        (field (name "BOM_Supplier Part") "C14858")
      )
      (libsource (lib "") (part "CL10C101JB8NNNC"))
    )
    (comp (ref "C156")
      (value "100nF")
      (fields
        (field (name "BOM_Manufacturer Part") "CL10B104KB8NNNC")
        (field (name "BOM_Supplier Part") "C1591")
      )
      (libsource (lib "") (part "CL10B104KB8NNNC"))
    )
    (comp (ref "C157")
      (value "100pF")
      (fields
        (field (name "BOM_Manufacturer Part") "CL10C101JB8NNNC")
        (field (name "BOM_Supplier Part") "C14858")
      )
      (libsource (lib "") (part "CL10C101JB8NNNC"))
    )
    (comp (ref "C158")
      (value "100nF")
      (fields
        (field (name "BOM_Manufacturer Part") "CL10B104KB8NNNC")
        (field (name "BOM_Supplier Part") "C1591")
      )
      (libsource (lib "") (part "CL10B104KB8NNNC"))
    )
    (comp (ref "C159")
      (value "100pF")
      (fields
        (field (name "BOM_Manufacturer Part") "CL10C101JB8NNNC")
        (field (name "BOM_Supplier Part") "C14858")
      )
      (libsource (lib "") (part "CL10C101JB8NNNC"))
    )
    (comp (ref "C160")
      (value "100nF")
      (fields
        (field (name "BOM_Manufacturer Part") "CL10B104KB8NNNC")
        (field (name "BOM_Supplier Part") "C1591")
      )
      (libsource (lib "") (part "CL10B104KB8NNNC"))
    )
    (comp (ref "C161")
      (value "100pF")
      (fields
        (field (name "BOM_Manufacturer Part") "CL10C101JB8NNNC")
        (field (name "BOM_Supplier Part") "C14858")
      )
      (libsource (lib "") (part "CL10C101JB8NNNC"))
    )
    (comp (ref "C162")
      (value "100nF")
      (fields
        (field (name "BOM_Manufacturer Part") "CL10B104KB8NNNC")
        (field (name "BOM_Supplier Part") "C1591")
      )
      (libsource (lib "") (part "CL10B104KB8NNNC"))
    )
    (comp (ref "C163")
      (value "100pF")
      (fields
        (field (name "BOM_Manufacturer Part") "CL10C101JB8NNNC")
        (field (name "BOM_Supplier Part") "C14858")
      )
      (libsource (lib "") (part "CL10C101JB8NNNC"))
    )
    (comp (ref "C164")
      (value "100nF")
      (fields
        (field (name "BOM_Manufacturer Part") "CL10B104KB8NNNC")
        (field (name "BOM_Supplier Part") "C1591")
      )
      (libsource (lib "") (part "CL10B104KB8NNNC"))
    )
    (comp (ref "C165")
      (value "100pF")
      (fields
        (field (name "BOM_Manufacturer Part") "CL10C101JB8NNNC")
        (field (name "BOM_Supplier Part") "C14858")
      )
      (libsource (lib "") (part "CL10C101JB8NNNC"))
    )
    (comp (ref "C166")
      (value "100nF")
      (fields
        (field (name "BOM_Manufacturer Part") "CL10B104KB8NNNC")
        (field (name "BOM_Supplier Part") "C1591")
      )
      (libsource (lib "") (part "CL10B104KB8NNNC"))
    )
    (comp (ref "C167")
      (value "100pF")
      (fields
        (field (name "BOM_Manufacturer Part") "CL10C101JB8NNNC")
        (field (name "BOM_Supplier Part") "C14858")
      )
      (libsource (lib "") (part "CL10C101JB8NNNC"))
    )
    (comp (ref "C168")
      (value "100nF")
      (fields
        (field (name "BOM_Manufacturer Part") "CL10B104KB8NNNC")
        (field (name "BOM_Supplier Part") "C1591")
      )
      (libsource (lib "") (part "CL10B104KB8NNNC"))
    )
    (comp (ref "C169")
      (value "100pF")
      (fields
        (field (name "BOM_Manufacturer Part") "CL10C101JB8NNNC")
        (field (name "BOM_Supplier Part") "C14858")
      )
      (libsource (lib "") (part "CL10C101JB8NNNC"))
    )
    (comp (ref "C170")
      (value "100nF")
      (fields
        (field (name "BOM_Manufacturer Part") "CL10B104KB8NNNC")
        (field (name "BOM_Supplier Part") "C1591")
      )
      (libsource (lib "") (part "CL10B104KB8NNNC"))
    )
    (comp (ref "C171")
      (value "100pF")
      (fields
        (field (name "BOM_Manufacturer Part") "CL10C101JB8NNNC")
        (field (name "BOM_Supplier Part") "C14858")
      )
      (libsource (lib "") (part "CL10C101JB8NNNC"))
    )
    (comp (ref "C172")
      (value "100nF")
      (fields
        (field (name "BOM_Manufacturer Part") "CL10B104KB8NNNC")
        (field (name "BOM_Supplier Part") "C1591")
      )
      (libsource (lib "") (part "CL10B104KB8NNNC"))
    )
    (comp (ref "C173")
      (value "100pF")
      (fields
        (field (name "BOM_Manufacturer Part") "CL10C101JB8NNNC")
        (field (name "BOM_Supplier Part") "C14858")
      )
      (libsource (lib "") (part "CL10C101JB8NNNC"))
    )
    (comp (ref "C174")
      (value "100nF")
      (fields
        (field (name "BOM_Manufacturer Part") "CL10B104KB8NNNC")
        (field (name "BOM_Supplier Part") "C1591")
      )
      (libsource (lib "") (part "CL10B104KB8NNNC"))
    )
    (comp (ref "C175")
      (value "100pF")
      (fields
        (field (name "BOM_Manufacturer Part") "CL10C101JB8NNNC")
        (field (name "BOM_Supplier Part") "C14858")
      )
      (libsource (lib "") (part "CL10C101JB8NNNC"))
    )
    (comp (ref "C176")
      (value "100nF")
      (fields
        (field (name "BOM_Manufacturer Part") "CL10B104KB8NNNC")
        (field (name "BOM_Supplier Part") "C1591")
      )
      (libsource (lib "") (part "CL10B104KB8NNNC"))
    )
    (comp (ref "C177")
      (value "100pF")
      (fields
        (field (name "BOM_Manufacturer Part") "CL10C101JB8NNNC")
        (field (name "BOM_Supplier Part") "C14858")
      )
      (libsource (lib "") (part "CL10C101JB8NNNC"))
    )
    (comp (ref "C178")
      (value "100nF")
      (fields
        (field (name "BOM_Manufacturer Part") "CL10B104KB8NNNC")
        (field (name "BOM_Supplier Part") "C1591")
      )
      (libsource (lib "") (part "CL10B104KB8NNNC"))
    )
    (comp (ref "C179")
      (value "100pF")
      (fields
        (field (name "BOM_Manufacturer Part") "CL10C101JB8NNNC")
        (field (name "BOM_Supplier Part") "C14858")
      )
      (libsource (lib "") (part "CL10C101JB8NNNC"))
    )
    (comp (ref "C180")
      (value "100nF")
      (fields
        (field (name "BOM_Manufacturer Part") "CL10B104KB8NNNC")
        (field (name "BOM_Supplier Part") "C1591")
      )
      (libsource (lib "") (part "CL10B104KB8NNNC"))
    )
    (comp (ref "C181")
      (value "100pF")
      (fields
        (field (name "BOM_Manufacturer Part") "CL10C101JB8NNNC")
        (field (name "BOM_Supplier Part") "C14858")
      )
      (libsource (lib "") (part "CL10C101JB8NNNC"))
    )
    (comp (ref "C182")
      (value "100nF")
      (fields
        (field (name "BOM_Manufacturer Part") "CL10B104KB8NNNC")
        (field (name "BOM_Supplier Part") "C1591")
      )
      (libsource (lib "") (part "CL10B104KB8NNNC"))
    )
    (comp (ref "C183")
      (value "100pF")
      (fields
        (field (name "BOM_Manufacturer Part") "CL10C101JB8NNNC")
        (field (name "BOM_Supplier Part") "C14858")
      )
      (libsource (lib "") (part "CL10C101JB8NNNC"))
    )
    (comp (ref "C184")
      (value "100nF")
      (fields
        (field (name "BOM_Manufacturer Part") "CL10B104KB8NNNC")
        (field (name "BOM_Supplier Part") "C1591")
      )
      (libsource (lib "") (part "CL10B104KB8NNNC"))
    )
    (comp (ref "C185")
      (value "100pF")
      (fields
        (field (name "BOM_Manufacturer Part") "CL10C101JB8NNNC")
        (field (name "BOM_Supplier Part") "C14858")
      )
      (libsource (lib "") (part "CL10C101JB8NNNC"))
    )
    (comp (ref "C186")
      (value "100nF")
      (fields
        (field (name "BOM_Manufacturer Part") "CL10B104KB8NNNC")
        (field (name "BOM_Supplier Part") "C1591")
      )
      (libsource (lib "") (part "CL10B104KB8NNNC"))
    )
    (comp (ref "C187")
      (value "100pF")
      (fields
        (field (name "BOM_Manufacturer Part") "CL10C101JB8NNNC")
        (field (name "BOM_Supplier Part") "C14858")
      )
      (libsource (lib "") (part "CL10C101JB8NNNC"))
    )
    (comp (ref "C188")
      (value "100nF")
      (fields
        (field (name "BOM_Manufacturer Part") "CL10B104KB8NNNC")
        (field (name "BOM_Supplier Part") "C1591")
      )
      (libsource (lib "") (part "CL10B104KB8NNNC"))
    )
    (comp (ref "C189")
      (value "100pF")
      (fields
        (field (name "BOM_Manufacturer Part") "CL10C101JB8NNNC")
        (field (name "BOM_Supplier Part") "C14858")
      )
      (libsource (lib "") (part "CL10C101JB8NNNC"))
    )
    (comp (ref "C190")
      (value "100nF")
      (fields
        (field (name "BOM_Manufacturer Part") "CL10B104KB8NNNC")
        (field (name "BOM_Supplier Part") "C1591")
      )
      (libsource (lib "") (part "CL10B104KB8NNNC"))
    )
    (comp (ref "C191")
      (value "100pF")
      (fields
        (field (name "BOM_Manufacturer Part") "CL10C101JB8NNNC")
        (field (name "BOM_Supplier Part") "C14858")
      )
      (libsource (lib "") (part "CL10C101JB8NNNC"))
    )
    (comp (ref "C192")
      (value "100nF")
      (fields
        (field (name "BOM_Manufacturer Part") "CL10B104KB8NNNC")
        (field (name "BOM_Supplier Part") "C1591")
      )
      (libsource (lib "") (part "CL10B104KB8NNNC"))
    )
    (comp (ref "C193")
      (value "100pF")
      (fields
        (field (name "BOM_Manufacturer Part") "CL10C101JB8NNNC")
        (field (name "BOM_Supplier Part") "C14858")
      )
      (libsource (lib "") (part "CL10C101JB8NNNC"))
    )
    (comp (ref "C194")
      (value "100nF")
      (fields
        (field (name "BOM_Manufacturer Part") "CL10B104KB8NNNC")
        (field (name "BOM_Supplier Part") "C1591")
      )
      (libsource (lib "") (part "CL10B104KB8NNNC"))
    )
    (comp (ref "C195")
      (value "100nF")
      (fields
        (field (name "BOM_Manufacturer Part") "CL10B104KB8NNNC")
        (field (name "BOM_Supplier Part") "C1591")
      )
      (libsource (lib "") (part "CL10B104KB8NNNC"))
    )
    (comp (ref "C196")
      (value "100pF")
      (fields
        (field (name "BOM_Manufacturer Part") "CL10C101JB8NNNC")
        (field (name "BOM_Supplier Part") "C14858")
      )
      (libsource (lib "") (part "CL10C101JB8NNNC"))
    )
    (comp (ref "C197")
      (value "100nF")
      (fields
        (field (name "BOM_Manufacturer Part") "CL10B104KB8NNNC")
        (field (name "BOM_Supplier Part") "C1591")
      )
      (libsource (lib "") (part "CL10B104KB8NNNC"))
    )
    (comp (ref "C198")
      (value "100pF")
      (fields
        (field (name "BOM_Manufacturer Part") "CL10C101JB8NNNC")
        (field (name "BOM_Supplier Part") "C14858")
      )
      (libsource (lib "") (part "CL10C101JB8NNNC"))
    )
    (comp (ref "C199")
      (value "100nF")
      (fields
        (field (name "BOM_Manufacturer Part") "CL10B104KB8NNNC")
        (field (name "BOM_Supplier Part") "C1591")
      )
      (libsource (lib "") (part "CL10B104KB8NNNC"))
    )
    (comp (ref "C200")
      (value "100pF")
      (fields
        (field (name "BOM_Manufacturer Part") "CL10C101JB8NNNC")
        (field (name "BOM_Supplier Part") "C14858")
      )
      (libsource (lib "") (part "CL10C101JB8NNNC"))
    )
    (comp (ref "C201")
      (value "100nF")
      (fields
        (field (name "BOM_Manufacturer Part") "CL10B104KB8NNNC")
        (field (name "BOM_Supplier Part") "C1591")
      )
      (libsource (lib "") (part "CL10B104KB8NNNC"))
    )
    (comp (ref "C202")
      (value "100pF")
      (fields
        (field (name "BOM_Manufacturer Part") "CL10C101JB8NNNC")
        (field (name "BOM_Supplier Part") "C14858")
      )
      (libsource (lib "") (part "CL10C101JB8NNNC"))
    )
    (comp (ref "C203")
      (value "100nF")
      (fields
        (field (name "BOM_Manufacturer Part") "CL10B104KB8NNNC")
        (field (name "BOM_Supplier Part") "C1591")
      )
      (libsource (lib "") (part "CL10B104KB8NNNC"))
    )
    (comp (ref "C204")
      (value "100pF")
      (fields
        (field (name "BOM_Manufacturer Part") "CL10C101JB8NNNC")
        (field (name "BOM_Supplier Part") "C14858")
      )
      (libsource (lib "") (part "CL10C101JB8NNNC"))
    )
    (comp (ref "C205")
      (value "100nF")
      (fields
        (field (name "BOM_Manufacturer Part") "CL10B104KB8NNNC")
        (field (name "BOM_Supplier Part") "C1591")
      )
      (libsource (lib "") (part "CL10B104KB8NNNC"))
    )
    (comp (ref "C206")
      (value "100pF")
      (fields
        (field (name "BOM_Manufacturer Part") "CL10C101JB8NNNC")
        (field (name "BOM_Supplier Part") "C14858")
      )
      (libsource (lib "") (part "CL10C101JB8NNNC"))
    )
    (comp (ref "C207")
      (value "100nF")
      (fields
        (field (name "BOM_Manufacturer Part") "CL10B104KB8NNNC")
        (field (name "BOM_Supplier Part") "C1591")
      )
      (libsource (lib "") (part "CL10B104KB8NNNC"))
    )
    (comp (ref "C208")
      (value "100pF")
      (fields
        (field (name "BOM_Manufacturer Part") "CL10C101JB8NNNC")
        (field (name "BOM_Supplier Part") "C14858")
      )
      (libsource (lib "") (part "CL10C101JB8NNNC"))
    )
    (comp (ref "C209")
      (value "100nF")
      (fields
        (field (name "BOM_Manufacturer Part") "CL10B104KB8NNNC")
        (field (name "BOM_Supplier Part") "C1591")
      )
      (libsource (lib "") (part "CL10B104KB8NNNC"))
    )
    (comp (ref "C210")
      (value "100pF")
      (fields
        (field (name "BOM_Manufacturer Part") "CL10C101JB8NNNC")
        (field (name "BOM_Supplier Part") "C14858")
      )
      (libsource (lib "") (part "CL10C101JB8NNNC"))
    )
    (comp (ref "C211")
      (value "100nF")
      (fields
        (field (name "BOM_Manufacturer Part") "CL10B104KB8NNNC")
        (field (name "BOM_Supplier Part") "C1591")
      )
      (libsource (lib "") (part "CL10B104KB8NNNC"))
    )
    (comp (ref "C212")
      (value "100pF")
      (fields
        (field (name "BOM_Manufacturer Part") "CL10C101JB8NNNC")
        (field (name "BOM_Supplier Part") "C14858")
      )
      (libsource (lib "") (part "CL10C101JB8NNNC"))
    )
    (comp (ref "C213")
      (value "100nF")
      (fields
        (field (name "BOM_Manufacturer Part") "CL10B104KB8NNNC")
        (field (name "BOM_Supplier Part") "C1591")
      )
      (libsource (lib "") (part "CL10B104KB8NNNC"))
    )
    (comp (ref "C214")
      (value "100pF")
      (fields
        (field (name "BOM_Manufacturer Part") "CL10C101JB8NNNC")
        (field (name "BOM_Supplier Part") "C14858")
      )
      (libsource (lib "") (part "CL10C101JB8NNNC"))
    )
    (comp (ref "C215")
      (value "100nF")
      (fields
        (field (name "BOM_Manufacturer Part") "CL10B104KB8NNNC")
        (field (name "BOM_Supplier Part") "C1591")
      )
      (libsource (lib "") (part "CL10B104KB8NNNC"))
    )
    (comp (ref "C216")
      (value "100pF")
      (fields
        (field (name "BOM_Manufacturer Part") "CL10C101JB8NNNC")
        (field (name "BOM_Supplier Part") "C14858")
      )
      (libsource (lib "") (part "CL10C101JB8NNNC"))
    )
    (comp (ref "C217")
      (value "100nF")
      (fields
        (field (name "BOM_Manufacturer Part") "CL10B104KB8NNNC")
        (field (name "BOM_Supplier Part") "C1591")
      )
      (libsource (lib "") (part "CL10B104KB8NNNC"))
    )
    (comp (ref "C218")
      (value "100pF")
      (fields
        (field (name "BOM_Manufacturer Part") "CL10C101JB8NNNC")
        (field (name "BOM_Supplier Part") "C14858")
      )
      (libsource (lib "") (part "CL10C101JB8NNNC"))
    )
    (comp (ref "C219")
      (value "100nF")
      (fields
        (field (name "BOM_Manufacturer Part") "CL10B104KB8NNNC")
        (field (name "BOM_Supplier Part") "C1591")
      )
      (libsource (lib "") (part "CL10B104KB8NNNC"))
    )
    (comp (ref "C220")
      (value "100pF")
      (fields
        (field (name "BOM_Manufacturer Part") "CL10C101JB8NNNC")
        (field (name "BOM_Supplier Part") "C14858")
      )
      (libsource (lib "") (part "CL10C101JB8NNNC"))
    )
    (comp (ref "C221")
      (value "100nF")
      (fields
        (field (name "BOM_Manufacturer Part") "CL10B104KB8NNNC")
        (field (name "BOM_Supplier Part") "C1591")
      )
      (libsource (lib "") (part "CL10B104KB8NNNC"))
    )
    (comp (ref "C222")
      (value "100pF")
      (fields
        (field (name "BOM_Manufacturer Part") "CL10C101JB8NNNC")
        (field (name "BOM_Supplier Part") "C14858")
      )
      (libsource (lib "") (part "CL10C101JB8NNNC"))
    )
    (comp (ref "C223")
      (value "100nF")
      (fields
        (field (name "BOM_Manufacturer Part") "CL10B104KB8NNNC")
        (field (name "BOM_Supplier Part") "C1591")
      )
      (libsource (lib "") (part "CL10B104KB8NNNC"))
    )
    (comp (ref "C224")
      (value "100pF")
      (fields
        (field (name "BOM_Manufacturer Part") "CL10C101JB8NNNC")
        (field (name "BOM_Supplier Part") "C14858")
      )
      (libsource (lib "") (part "CL10C101JB8NNNC"))
    )
    (comp (ref "C225")
      (value "100nF")
      (fields
        (field (name "BOM_Manufacturer Part") "CL10B104KB8NNNC")
        (field (name "BOM_Supplier Part") "C1591")
      )
      (libsource (lib "") (part "CL10B104KB8NNNC"))
    )
    (comp (ref "C226")
      (value "100pF")
      (fields
        (field (name "BOM_Manufacturer Part") "CL10C101JB8NNNC")
        (field (name "BOM_Supplier Part") "C14858")
      )
      (libsource (lib "") (part "CL10C101JB8NNNC"))
    )
    (comp (ref "C227")
      (value "100pF")
      (fields
        (field (name "BOM_Manufacturer Part") "CL10C101JB8NNNC")
        (field (name "BOM_Supplier Part") "C14858")
      )
      (libsource (lib "") (part "CL10C101JB8NNNC"))
    )
    (comp (ref "C228")
      (value "100nF")
      (fields
        (field (name "BOM_Manufacturer Part") "CL10B104KB8NNNC")
        (field (name "BOM_Supplier Part") "C1591")
      )
      (libsource (lib "") (part "CL10B104KB8NNNC"))
    )
    (comp (ref "C229")
      (value "100pF")
      (fields
        (field (name "BOM_Manufacturer Part") "CL10C101JB8NNNC")
        (field (name "BOM_Supplier Part") "C14858")
      )
      (libsource (lib "") (part "CL10C101JB8NNNC"))
    )
    (comp (ref "C230")
      (value "100nF")
      (fields
        (field (name "BOM_Manufacturer Part") "CL10B104KB8NNNC")
        (field (name "BOM_Supplier Part") "C1591")
      )
      (libsource (lib "") (part "CL10B104KB8NNNC"))
    )
    (comp (ref "C231")
      (value "100pF")
      (fields
        (field (name "BOM_Manufacturer Part") "CL10C101JB8NNNC")
        (field (name "BOM_Supplier Part") "C14858")
      )
      (libsource (lib "") (part "CL10C101JB8NNNC"))
    )
    (comp (ref "C232")
      (value "100nF")
      (fields
        (field (name "BOM_Manufacturer Part") "CL10B104KB8NNNC")
        (field (name "BOM_Supplier Part") "C1591")
      )
      (libsource (lib "") (part "CL10B104KB8NNNC"))
    )
    (comp (ref "C233")
      (value "100pF")
      (fields
        (field (name "BOM_Manufacturer Part") "CL10C101JB8NNNC")
        (field (name "BOM_Supplier Part") "C14858")
      )
      (libsource (lib "") (part "CL10C101JB8NNNC"))
    )
    (comp (ref "C234")
      (value "100nF")
      (fields
        (field (name "BOM_Manufacturer Part") "CL10B104KB8NNNC")
        (field (name "BOM_Supplier Part") "C1591")
      )
      (libsource (lib "") (part "CL10B104KB8NNNC"))
    )
    (comp (ref "C235")
      (value "100pF")
      (fields
        (field (name "BOM_Manufacturer Part") "CL10C101JB8NNNC")
        (field (name "BOM_Supplier Part") "C14858")
      )
      (libsource (lib "") (part "CL10C101JB8NNNC"))
    )
    (comp (ref "C236")
      (value "100nF")
      (fields
        (field (name "BOM_Manufacturer Part") "CL10B104KB8NNNC")
        (field (name "BOM_Supplier Part") "C1591")
      )
      (libsource (lib "") (part "CL10B104KB8NNNC"))
    )
    (comp (ref "C237")
      (value "100pF")
      (fields
        (field (name "BOM_Manufacturer Part") "CL10C101JB8NNNC")
        (field (name "BOM_Supplier Part") "C14858")
      )
      (libsource (lib "") (part "CL10C101JB8NNNC"))
    )
    (comp (ref "C238")
      (value "100nF")
      (fields
        (field (name "BOM_Manufacturer Part") "CL10B104KB8NNNC")
        (field (name "BOM_Supplier Part") "C1591")
      )
      (libsource (lib "") (part "CL10B104KB8NNNC"))
    )
    (comp (ref "C239")
      (value "100pF")
      (fields
        (field (name "BOM_Manufacturer Part") "CL10C101JB8NNNC")
        (field (name "BOM_Supplier Part") "C14858")
      )
      (libsource (lib "") (part "CL10C101JB8NNNC"))
    )
    (comp (ref "C240")
      (value "100nF")
      (fields
        (field (name "BOM_Manufacturer Part") "CL10B104KB8NNNC")
        (field (name "BOM_Supplier Part") "C1591")
      )
      (libsource (lib "") (part "CL10B104KB8NNNC"))
    )
    (comp (ref "C241")
      (value "100pF")
      (fields
        (field (name "BOM_Manufacturer Part") "CL10C101JB8NNNC")
        (field (name "BOM_Supplier Part") "C14858")
      )
      (libsource (lib "") (part "CL10C101JB8NNNC"))
    )
    (comp (ref "C242")
      (value "100nF")
      (fields
        (field (name "BOM_Manufacturer Part") "CL10B104KB8NNNC")
        (field (name "BOM_Supplier Part") "C1591")
      )
      (libsource (lib "") (part "CL10B104KB8NNNC"))
    )
    (comp (ref "C243")
      (value "100pF")
      (fields
        (field (name "BOM_Manufacturer Part") "CL10C101JB8NNNC")
        (field (name "BOM_Supplier Part") "C14858")
      )
      (libsource (lib "") (part "CL10C101JB8NNNC"))
    )
    (comp (ref "C244")
      (value "100nF")
      (fields
        (field (name "BOM_Manufacturer Part") "CL10B104KB8NNNC")
        (field (name "BOM_Supplier Part") "C1591")
      )
      (libsource (lib "") (part "CL10B104KB8NNNC"))
    )
    (comp (ref "C245")
      (value "100pF")
      (fields
        (field (name "BOM_Manufacturer Part") "CL10C101JB8NNNC")
        (field (name "BOM_Supplier Part") "C14858")
      )
      (libsource (lib "") (part "CL10C101JB8NNNC"))
    )
    (comp (ref "C246")
      (value "100nF")
      (fields
        (field (name "BOM_Manufacturer Part") "CL10B104KB8NNNC")
        (field (name "BOM_Supplier Part") "C1591")
      )
      (libsource (lib "") (part "CL10B104KB8NNNC"))
    )
    (comp (ref "C247")
      (value "100pF")
      (fields
        (field (name "BOM_Manufacturer Part") "CL10C101JB8NNNC")
        (field (name "BOM_Supplier Part") "C14858")
      )
      (libsource (lib "") (part "CL10C101JB8NNNC"))
    )
    (comp (ref "C248")
      (value "100nF")
      (fields
        (field (name "BOM_Manufacturer Part") "CL10B104KB8NNNC")
        (field (name "BOM_Supplier Part") "C1591")
      )
      (libsource (lib "") (part "CL10B104KB8NNNC"))
    )
    (comp (ref "C249")
      (value "100pF")
      (fields
        (field (name "BOM_Manufacturer Part") "CL10C101JB8NNNC")
        (field (name "BOM_Supplier Part") "C14858")
      )
      (libsource (lib "") (part "CL10C101JB8NNNC"))
    )
    (comp (ref "C250")
      (value "100nF")
      (fields
        (field (name "BOM_Manufacturer Part") "CL10B104KB8NNNC")
        (field (name "BOM_Supplier Part") "C1591")
      )
      (libsource (lib "") (part "CL10B104KB8NNNC"))
    )
    (comp (ref "C251")
      (value "100pF")
      (fields
        (field (name "BOM_Manufacturer Part") "CL10C101JB8NNNC")
        (field (name "BOM_Supplier Part") "C14858")
      )
      (libsource (lib "") (part "CL10C101JB8NNNC"))
    )
    (comp (ref "C252")
      (value "100nF")
      (fields
        (field (name "BOM_Manufacturer Part") "CL10B104KB8NNNC")
        (field (name "BOM_Supplier Part") "C1591")
      )
      (libsource (lib "") (part "CL10B104KB8NNNC"))
    )
    (comp (ref "C253")
      (value "100pF")
      (fields
        (field (name "BOM_Manufacturer Part") "CL10C101JB8NNNC")
        (field (name "BOM_Supplier Part") "C14858")
      )
      (libsource (lib "") (part "CL10C101JB8NNNC"))
    )
    (comp (ref "C254")
      (value "100nF")
      (fields
        (field (name "BOM_Manufacturer Part") "CL10B104KB8NNNC")
        (field (name "BOM_Supplier Part") "C1591")
      )
      (libsource (lib "") (part "CL10B104KB8NNNC"))
    )
    (comp (ref "C255")
      (value "100pF")
      (fields
        (field (name "BOM_Manufacturer Part") "CL10C101JB8NNNC")
        (field (name "BOM_Supplier Part") "C14858")
      )
      (libsource (lib "") (part "CL10C101JB8NNNC"))
    )
    (comp (ref "C256")
      (value "100nF")
      (fields
        (field (name "BOM_Manufacturer Part") "CL10B104KB8NNNC")
        (field (name "BOM_Supplier Part") "C1591")
      )
      (libsource (lib "") (part "CL10B104KB8NNNC"))
    )
    (comp (ref "C257")
      (value "100pF")
      (fields
        (field (name "BOM_Manufacturer Part") "CL10C101JB8NNNC")
        (field (name "BOM_Supplier Part") "C14858")
      )
      (libsource (lib "") (part "CL10C101JB8NNNC"))
    )
    (comp (ref "C258")
      (value "100nF")
      (fields
        (field (name "BOM_Manufacturer Part") "CL10B104KB8NNNC")
        (field (name "BOM_Supplier Part") "C1591")
      )
      (libsource (lib "") (part "CL10B104KB8NNNC"))
    )
    (comp (ref "C259")
      (value "100nF")
      (fields
        (field (name "BOM_Manufacturer Part") "CL10B104KB8NNNC")
        (field (name "BOM_Supplier Part") "C1591")
      )
      (libsource (lib "") (part "CL10B104KB8NNNC"))
    )
    (comp (ref "C260")
      (value "100pF")
      (fields
        (field (name "BOM_Manufacturer Part") "CL10C101JB8NNNC")
        (field (name "BOM_Supplier Part") "C14858")
      )
      (libsource (lib "") (part "CL10C101JB8NNNC"))
    )
    (comp (ref "C261")
      (value "100nF")
      (fields
        (field (name "BOM_Manufacturer Part") "CL10B104KB8NNNC")
        (field (name "BOM_Supplier Part") "C1591")
      )
      (libsource (lib "") (part "CL10B104KB8NNNC"))
    )
    (comp (ref "C262")
      (value "100pF")
      (fields
        (field (name "BOM_Manufacturer Part") "CL10C101JB8NNNC")
        (field (name "BOM_Supplier Part") "C14858")
      )
      (libsource (lib "") (part "CL10C101JB8NNNC"))
    )
    (comp (ref "C263")
      (value "100nF")
      (fields
        (field (name "BOM_Manufacturer Part") "CL10B104KB8NNNC")
        (field (name "BOM_Supplier Part") "C1591")
      )
      (libsource (lib "") (part "CL10B104KB8NNNC"))
    )
    (comp (ref "C264")
      (value "100pF")
      (fields
        (field (name "BOM_Manufacturer Part") "CL10C101JB8NNNC")
        (field (name "BOM_Supplier Part") "C14858")
      )
      (libsource (lib "") (part "CL10C101JB8NNNC"))
    )
    (comp (ref "C265")
      (value "100nF")
      (fields
        (field (name "BOM_Manufacturer Part") "CL10B104KB8NNNC")
        (field (name "BOM_Supplier Part") "C1591")
      )
      (libsource (lib "") (part "CL10B104KB8NNNC"))
    )
    (comp (ref "C266")
      (value "100pF")
      (fields
        (field (name "BOM_Manufacturer Part") "CL10C101JB8NNNC")
        (field (name "BOM_Supplier Part") "C14858")
      )
      (libsource (lib "") (part "CL10C101JB8NNNC"))
    )
    (comp (ref "C267")
      (value "100nF")
      (fields
        (field (name "BOM_Manufacturer Part") "CL10B104KB8NNNC")
        (field (name "BOM_Supplier Part") "C1591")
      )
      (libsource (lib "") (part "CL10B104KB8NNNC"))
    )
    (comp (ref "C268")
      (value "100pF")
      (fields
        (field (name "BOM_Manufacturer Part") "CL10C101JB8NNNC")
        (field (name "BOM_Supplier Part") "C14858")
      )
      (libsource (lib "") (part "CL10C101JB8NNNC"))
    )
    (comp (ref "C269")
      (value "100nF")
      (fields
        (field (name "BOM_Manufacturer Part") "CL10B104KB8NNNC")
        (field (name "BOM_Supplier Part") "C1591")
      )
      (libsource (lib "") (part "CL10B104KB8NNNC"))
    )
    (comp (ref "C270")
      (value "100pF")
      (fields
        (field (name "BOM_Manufacturer Part") "CL10C101JB8NNNC")
        (field (name "BOM_Supplier Part") "C14858")
      )
      (libsource (lib "") (part "CL10C101JB8NNNC"))
    )
    (comp (ref "C271")
      (value "100nF")
      (fields
        (field (name "BOM_Manufacturer Part") "CL10B104KB8NNNC")
        (field (name "BOM_Supplier Part") "C1591")
      )
      (libsource (lib "") (part "CL10B104KB8NNNC"))
    )
    (comp (ref "C272")
      (value "100pF")
      (fields
        (field (name "BOM_Manufacturer Part") "CL10C101JB8NNNC")
        (field (name "BOM_Supplier Part") "C14858")
      )
      (libsource (lib "") (part "CL10C101JB8NNNC"))
    )
    (comp (ref "C273")
      (value "100nF")
      (fields
        (field (name "BOM_Manufacturer Part") "CL10B104KB8NNNC")
        (field (name "BOM_Supplier Part") "C1591")
      )
      (libsource (lib "") (part "CL10B104KB8NNNC"))
    )
    (comp (ref "C274")
      (value "100pF")
      (fields
        (field (name "BOM_Manufacturer Part") "CL10C101JB8NNNC")
        (field (name "BOM_Supplier Part") "C14858")
      )
      (libsource (lib "") (part "CL10C101JB8NNNC"))
    )
    (comp (ref "C275")
      (value "100nF")
      (fields
        (field (name "BOM_Manufacturer Part") "CL10B104KB8NNNC")
        (field (name "BOM_Supplier Part") "C1591")
      )
      (libsource (lib "") (part "CL10B104KB8NNNC"))
    )
    (comp (ref "C276")
      (value "100pF")
      (fields
        (field (name "BOM_Manufacturer Part") "CL10C101JB8NNNC")
        (field (name "BOM_Supplier Part") "C14858")
      )
      (libsource (lib "") (part "CL10C101JB8NNNC"))
    )
    (comp (ref "C277")
      (value "100nF")
      (fields
        (field (name "BOM_Manufacturer Part") "CL10B104KB8NNNC")
        (field (name "BOM_Supplier Part") "C1591")
      )
      (libsource (lib "") (part "CL10B104KB8NNNC"))
    )
    (comp (ref "C278")
      (value "100pF")
      (fields
        (field (name "BOM_Manufacturer Part") "CL10C101JB8NNNC")
        (field (name "BOM_Supplier Part") "C14858")
      )
      (libsource (lib "") (part "CL10C101JB8NNNC"))
    )
    (comp (ref "C279")
      (value "100nF")
      (fields
        (field (name "BOM_Manufacturer Part") "CL10B104KB8NNNC")
        (field (name "BOM_Supplier Part") "C1591")
      )
      (libsource (lib "") (part "CL10B104KB8NNNC"))
    )
    (comp (ref "C280")
      (value "100pF")
      (fields
        (field (name "BOM_Manufacturer Part") "CL10C101JB8NNNC")
        (field (name "BOM_Supplier Part") "C14858")
      )
      (libsource (lib "") (part "CL10C101JB8NNNC"))
    )
    (comp (ref "C281")
      (value "100nF")
      (fields
        (field (name "BOM_Manufacturer Part") "CL10B104KB8NNNC")
        (field (name "BOM_Supplier Part") "C1591")
      )
      (libsource (lib "") (part "CL10B104KB8NNNC"))
    )
    (comp (ref "C282")
      (value "100pF")
      (fields
        (field (name "BOM_Manufacturer Part") "CL10C101JB8NNNC")
        (field (name "BOM_Supplier Part") "C14858")
      )
      (libsource (lib "") (part "CL10C101JB8NNNC"))
    )
    (comp (ref "C283")
      (value "100nF")
      (fields
        (field (name "BOM_Manufacturer Part") "CL10B104KB8NNNC")
        (field (name "BOM_Supplier Part") "C1591")
      )
      (libsource (lib "") (part "CL10B104KB8NNNC"))
    )
    (comp (ref "C284")
      (value "100pF")
      (fields
        (field (name "BOM_Manufacturer Part") "CL10C101JB8NNNC")
        (field (name "BOM_Supplier Part") "C14858")
      )
      (libsource (lib "") (part "CL10C101JB8NNNC"))
    )
    (comp (ref "C285")
      (value "100nF")
      (fields
        (field (name "BOM_Manufacturer Part") "CL10B104KB8NNNC")
        (field (name "BOM_Supplier Part") "C1591")
      )
      (libsource (lib "") (part "CL10B104KB8NNNC"))
    )
    (comp (ref "C286")
      (value "100pF")
      (fields
        (field (name "BOM_Manufacturer Part") "CL10C101JB8NNNC")
        (field (name "BOM_Supplier Part") "C14858")
      )
      (libsource (lib "") (part "CL10C101JB8NNNC"))
    )
    (comp (ref "C287")
      (value "100nF")
      (fields
        (field (name "BOM_Manufacturer Part") "CL10B104KB8NNNC")
        (field (name "BOM_Supplier Part") "C1591")
      )
      (libsource (lib "") (part "CL10B104KB8NNNC"))
    )
    (comp (ref "C288")
      (value "100pF")
      (fields
        (field (name "BOM_Manufacturer Part") "CL10C101JB8NNNC")
        (field (name "BOM_Supplier Part") "C14858")
      )
      (libsource (lib "") (part "CL10C101JB8NNNC"))
    )
    (comp (ref "C289")
      (value "100nF")
      (fields
        (field (name "BOM_Manufacturer Part") "CL10B104KB8NNNC")
        (field (name "BOM_Supplier Part") "C1591")
      )
      (libsource (lib "") (part "CL10B104KB8NNNC"))
    )
    (comp (ref "C290")
      (value "100pF")
      (fields
        (field (name "BOM_Manufacturer Part") "CL10C101JB8NNNC")
        (field (name "BOM_Supplier Part") "C14858")
      )
      (libsource (lib "") (part "CL10C101JB8NNNC"))
    )
    (comp (ref "C291")
      (value "100pF")
      (fields
        (field (name "BOM_Manufacturer Part") "CL10C101JB8NNNC")
        (field (name "BOM_Supplier Part") "C14858")
      )
      (libsource (lib "") (part "CL10C101JB8NNNC"))
    )
    (comp (ref "C292")
      (value "100nF")
      (fields
        (field (name "BOM_Manufacturer Part") "CL10B104KB8NNNC")
        (field (name "BOM_Supplier Part") "C1591")
      )
      (libsource (lib "") (part "CL10B104KB8NNNC"))
    )
    (comp (ref "C293")
      (value "100pF")
      (fields
        (field (name "BOM_Manufacturer Part") "CL10C101JB8NNNC")
        (field (name "BOM_Supplier Part") "C14858")
      )
      (libsource (lib "") (part "CL10C101JB8NNNC"))
    )
    (comp (ref "C294")
      (value "100nF")
      (fields
        (field (name "BOM_Manufacturer Part") "CL10B104KB8NNNC")
        (field (name "BOM_Supplier Part") "C1591")
      )
      (libsource (lib "") (part "CL10B104KB8NNNC"))
    )
    (comp (ref "C295")
      (value "100pF")
      (fields
        (field (name "BOM_Manufacturer Part") "CL10C101JB8NNNC")
        (field (name "BOM_Supplier Part") "C14858")
      )
      (libsource (lib "") (part "CL10C101JB8NNNC"))
    )
    (comp (ref "C296")
      (value "100nF")
      (fields
        (field (name "BOM_Manufacturer Part") "CL10B104KB8NNNC")
        (field (name "BOM_Supplier Part") "C1591")
      )
      (libsource (lib "") (part "CL10B104KB8NNNC"))
    )
    (comp (ref "C297")
      (value "100pF")
      (fields
        (field (name "BOM_Manufacturer Part") "CL10C101JB8NNNC")
        (field (name "BOM_Supplier Part") "C14858")
      )
      (libsource (lib "") (part "CL10C101JB8NNNC"))
    )
    (comp (ref "C298")
      (value "100nF")
      (fields
        (field (name "BOM_Manufacturer Part") "CL10B104KB8NNNC")
        (field (name "BOM_Supplier Part") "C1591")
      )
      (libsource (lib "") (part "CL10B104KB8NNNC"))
    )
    (comp (ref "C299")
      (value "100pF")
      (fields
        (field (name "BOM_Manufacturer Part") "CL10C101JB8NNNC")
        (field (name "BOM_Supplier Part") "C14858")
      )
      (libsource (lib "") (part "CL10C101JB8NNNC"))
    )
    (comp (ref "C300")
      (value "100nF")
      (fields
        (field (name "BOM_Manufacturer Part") "CL10B104KB8NNNC")
        (field (name "BOM_Supplier Part") "C1591")
      )
      (libsource (lib "") (part "CL10B104KB8NNNC"))
    )
    (comp (ref "C301")
      (value "100pF")
      (fields
        (field (name "BOM_Manufacturer Part") "CL10C101JB8NNNC")
        (field (name "BOM_Supplier Part") "C14858")
      )
      (libsource (lib "") (part "CL10C101JB8NNNC"))
    )
    (comp (ref "C302")
      (value "100nF")
      (fields
        (field (name "BOM_Manufacturer Part") "CL10B104KB8NNNC")
        (field (name "BOM_Supplier Part") "C1591")
      )
      (libsource (lib "") (part "CL10B104KB8NNNC"))
    )
    (comp (ref "C303")
      (value "100pF")
      (fields
        (field (name "BOM_Manufacturer Part") "CL10C101JB8NNNC")
        (field (name "BOM_Supplier Part") "C14858")
      )
      (libsource (lib "") (part "CL10C101JB8NNNC"))
    )
    (comp (ref "C304")
      (value "100nF")
      (fields
        (field (name "BOM_Manufacturer Part") "CL10B104KB8NNNC")
        (field (name "BOM_Supplier Part") "C1591")
      )
      (libsource (lib "") (part "CL10B104KB8NNNC"))
    )
    (comp (ref "C305")
      (value "100pF")
      (fields
        (field (name "BOM_Manufacturer Part") "CL10C101JB8NNNC")
        (field (name "BOM_Supplier Part") "C14858")
      )
      (libsource (lib "") (part "CL10C101JB8NNNC"))
    )
    (comp (ref "C306")
      (value "100nF")
      (fields
        (field (name "BOM_Manufacturer Part") "CL10B104KB8NNNC")
        (field (name "BOM_Supplier Part") "C1591")
      )
      (libsource (lib "") (part "CL10B104KB8NNNC"))
    )
    (comp (ref "C307")
      (value "100pF")
      (fields
        (field (name "BOM_Manufacturer Part") "CL10C101JB8NNNC")
        (field (name "BOM_Supplier Part") "C14858")
      )
      (libsource (lib "") (part "CL10C101JB8NNNC"))
    )
    (comp (ref "C308")
      (value "100nF")
      (fields
        (field (name "BOM_Manufacturer Part") "CL10B104KB8NNNC")
        (field (name "BOM_Supplier Part") "C1591")
      )
      (libsource (lib "") (part "CL10B104KB8NNNC"))
    )
    (comp (ref "C309")
      (value "100pF")
      (fields
        (field (name "BOM_Manufacturer Part") "CL10C101JB8NNNC")
        (field (name "BOM_Supplier Part") "C14858")
      )
      (libsource (lib "") (part "CL10C101JB8NNNC"))
    )
    (comp (ref "C310")
      (value "100nF")
      (fields
        (field (name "BOM_Manufacturer Part") "CL10B104KB8NNNC")
        (field (name "BOM_Supplier Part") "C1591")
      )
      (libsource (lib "") (part "CL10B104KB8NNNC"))
    )
    (comp (ref "C311")
      (value "100pF")
      (fields
        (field (name "BOM_Manufacturer Part") "CL10C101JB8NNNC")
        (field (name "BOM_Supplier Part") "C14858")
      )
      (libsource (lib "") (part "CL10C101JB8NNNC"))
    )
    (comp (ref "C312")
      (value "100nF")
      (fields
        (field (name "BOM_Manufacturer Part") "CL10B104KB8NNNC")
        (field (name "BOM_Supplier Part") "C1591")
      )
      (libsource (lib "") (part "CL10B104KB8NNNC"))
    )
    (comp (ref "C313")
      (value "100pF")
      (fields
        (field (name "BOM_Manufacturer Part") "CL10C101JB8NNNC")
        (field (name "BOM_Supplier Part") "C14858")
      )
      (libsource (lib "") (part "CL10C101JB8NNNC"))
    )
    (comp (ref "C314")
      (value "100nF")
      (fields
        (field (name "BOM_Manufacturer Part") "CL10B104KB8NNNC")
        (field (name "BOM_Supplier Part") "C1591")
      )
      (libsource (lib "") (part "CL10B104KB8NNNC"))
    )
    (comp (ref "C315")
      (value "100pF")
      (fields
        (field (name "BOM_Manufacturer Part") "CL10C101JB8NNNC")
        (field (name "BOM_Supplier Part") "C14858")
      )
      (libsource (lib "") (part "CL10C101JB8NNNC"))
    )
    (comp (ref "C316")
      (value "100nF")
      (fields
        (field (name "BOM_Manufacturer Part") "CL10B104KB8NNNC")
        (field (name "BOM_Supplier Part") "C1591")
      )
      (libsource (lib "") (part "CL10B104KB8NNNC"))
    )
    (comp (ref "C317")
      (value "100pF")
      (fields
        (field (name "BOM_Manufacturer Part") "CL10C101JB8NNNC")
        (field (name "BOM_Supplier Part") "C14858")
      )
      (libsource (lib "") (part "CL10C101JB8NNNC"))
    )
    (comp (ref "C318")
      (value "100nF")
      (fields
        (field (name "BOM_Manufacturer Part") "CL10B104KB8NNNC")
        (field (name "BOM_Supplier Part") "C1591")
      )
      (libsource (lib "") (part "CL10B104KB8NNNC"))
    )
    (comp (ref "C319")
      (value "100pF")
      (fields
        (field (name "BOM_Manufacturer Part") "CL10C101JB8NNNC")
        (field (name "BOM_Supplier Part") "C14858")
      )
      (libsource (lib "") (part "CL10C101JB8NNNC"))
    )
    (comp (ref "C320")
      (value "100nF")
      (fields
        (field (name "BOM_Manufacturer Part") "CL10B104KB8NNNC")
        (field (name "BOM_Supplier Part") "C1591")
      )
      (libsource (lib "") (part "CL10B104KB8NNNC"))
    )
    (comp (ref "C321")
      (value "100pF")
      (fields
        (field (name "BOM_Manufacturer Part") "CL10C101JB8NNNC")
        (field (name "BOM_Supplier Part") "C14858")
      )
      (libsource (lib "") (part "CL10C101JB8NNNC"))
    )
    (comp (ref "C322")
      (value "100nF")
      (fields
        (field (name "BOM_Manufacturer Part") "CL10B104KB8NNNC")
        (field (name "BOM_Supplier Part") "C1591")
      )
      (libsource (lib "") (part "CL10B104KB8NNNC"))
    )
    (comp (ref "C323")
      (value "100nF")
      (fields
        (field (name "BOM_Manufacturer Part") "CL10B104KB8NNNC")
        (field (name "BOM_Supplier Part") "C1591")
      )
      (libsource (lib "") (part "CL10B104KB8NNNC"))
    )
    (comp (ref "C324")
      (value "100pF")
      (fields
        (field (name "BOM_Manufacturer Part") "CL10C101JB8NNNC")
        (field (name "BOM_Supplier Part") "C14858")
      )
      (libsource (lib "") (part "CL10C101JB8NNNC"))
    )
    (comp (ref "C325")
      (value "100nF")
      (fields
        (field (name "BOM_Manufacturer Part") "CL10B104KB8NNNC")
        (field (name "BOM_Supplier Part") "C1591")
      )
      (libsource (lib "") (part "CL10B104KB8NNNC"))
    )
    (comp (ref "C326")
      (value "100pF")
      (fields
        (field (name "BOM_Manufacturer Part") "CL10C101JB8NNNC")
        (field (name "BOM_Supplier Part") "C14858")
      )
      (libsource (lib "") (part "CL10C101JB8NNNC"))
    )
    (comp (ref "C327")
      (value "100nF")
      (fields
        (field (name "BOM_Manufacturer Part") "CL10B104KB8NNNC")
        (field (name "BOM_Supplier Part") "C1591")
      )
      (libsource (lib "") (part "CL10B104KB8NNNC"))
    )
    (comp (ref "C328")
      (value "100pF")
      (fields
        (field (name "BOM_Manufacturer Part") "CL10C101JB8NNNC")
        (field (name "BOM_Supplier Part") "C14858")
      )
      (libsource (lib "") (part "CL10C101JB8NNNC"))
    )
    (comp (ref "C329")
      (value "100nF")
      (fields
        (field (name "BOM_Manufacturer Part") "CL10B104KB8NNNC")
        (field (name "BOM_Supplier Part") "C1591")
      )
      (libsource (lib "") (part "CL10B104KB8NNNC"))
    )
    (comp (ref "C330")
      (value "100pF")
      (fields
        (field (name "BOM_Manufacturer Part") "CL10C101JB8NNNC")
        (field (name "BOM_Supplier Part") "C14858")
      )
      (libsource (lib "") (part "CL10C101JB8NNNC"))
    )
    (comp (ref "C331")
      (value "100nF")
      (fields
        (field (name "BOM_Manufacturer Part") "CL10B104KB8NNNC")
        (field (name "BOM_Supplier Part") "C1591")
      )
      (libsource (lib "") (part "CL10B104KB8NNNC"))
    )
    (comp (ref "C332")
      (value "100pF")
      (fields
        (field (name "BOM_Manufacturer Part") "CL10C101JB8NNNC")
        (field (name "BOM_Supplier Part") "C14858")
      )
      (libsource (lib "") (part "CL10C101JB8NNNC"))
    )
    (comp (ref "C333")
      (value "100nF")
      (fields
        (field (name "BOM_Manufacturer Part") "CL10B104KB8NNNC")
        (field (name "BOM_Supplier Part") "C1591")
      )
      (libsource (lib "") (part "CL10B104KB8NNNC"))
    )
    (comp (ref "C334")
      (value "100pF")
      (fields
        (field (name "BOM_Manufacturer Part") "CL10C101JB8NNNC")
        (field (name "BOM_Supplier Part") "C14858")
      )
      (libsource (lib "") (part "CL10C101JB8NNNC"))
    )
    (comp (ref "C335")
      (value "100nF")
      (fields
        (field (name "BOM_Manufacturer Part") "CL10B104KB8NNNC")
        (field (name "BOM_Supplier Part") "C1591")
      )
      (libsource (lib "") (part "CL10B104KB8NNNC"))
    )
    (comp (ref "C336")
      (value "100pF")
      (fields
        (field (name "BOM_Manufacturer Part") "CL10C101JB8NNNC")
        (field (name "BOM_Supplier Part") "C14858")
      )
      (libsource (lib "") (part "CL10C101JB8NNNC"))
    )
    (comp (ref "C337")
      (value "100nF")
      (fields
        (field (name "BOM_Manufacturer Part") "CL10B104KB8NNNC")
        (field (name "BOM_Supplier Part") "C1591")
      )
      (libsource (lib "") (part "CL10B104KB8NNNC"))
    )
    (comp (ref "C338")
      (value "100pF")
      (fields
        (field (name "BOM_Manufacturer Part") "CL10C101JB8NNNC")
        (field (name "BOM_Supplier Part") "C14858")
      )
      (libsource (lib "") (part "CL10C101JB8NNNC"))
    )
    (comp (ref "C339")
      (value "100nF")
      (fields
        (field (name "BOM_Manufacturer Part") "CL10B104KB8NNNC")
        (field (name "BOM_Supplier Part") "C1591")
      )
      (libsource (lib "") (part "CL10B104KB8NNNC"))
    )
    (comp (ref "C340")
      (value "100pF")
      (fields
        (field (name "BOM_Manufacturer Part") "CL10C101JB8NNNC")
        (field (name "BOM_Supplier Part") "C14858")
      )
      (libsource (lib "") (part "CL10C101JB8NNNC"))
    )
    (comp (ref "C341")
      (value "100nF")
      (fields
        (field (name "BOM_Manufacturer Part") "CL10B104KB8NNNC")
        (field (name "BOM_Supplier Part") "C1591")
      )
      (libsource (lib "") (part "CL10B104KB8NNNC"))
    )
    (comp (ref "C342")
      (value "100pF")
      (fields
        (field (name "BOM_Manufacturer Part") "CL10C101JB8NNNC")
        (field (name "BOM_Supplier Part") "C14858")
      )
      (libsource (lib "") (part "CL10C101JB8NNNC"))
    )
    (comp (ref "C343")
      (value "100nF")
      (fields
        (field (name "BOM_Manufacturer Part") "CL10B104KB8NNNC")
        (field (name "BOM_Supplier Part") "C1591")
      )
      (libsource (lib "") (part "CL10B104KB8NNNC"))
    )
    (comp (ref "C344")
      (value "100pF")
      (fields
        (field (name "BOM_Manufacturer Part") "CL10C101JB8NNNC")
        (field (name "BOM_Supplier Part") "C14858")
      )
      (libsource (lib "") (part "CL10C101JB8NNNC"))
    )
    (comp (ref "C345")
      (value "100nF")
      (fields
        (field (name "BOM_Manufacturer Part") "CL10B104KB8NNNC")
        (field (name "BOM_Supplier Part") "C1591")
      )
      (libsource (lib "") (part "CL10B104KB8NNNC"))
    )
    (comp (ref "C346")
      (value "100pF")
      (fields
        (field (name "BOM_Manufacturer Part") "CL10C101JB8NNNC")
        (field (name "BOM_Supplier Part") "C14858")
      )
      (libsource (lib "") (part "CL10C101JB8NNNC"))
    )
    (comp (ref "C347")
      (value "100nF")
      (fields
        (field (name "BOM_Manufacturer Part") "CL10B104KB8NNNC")
        (field (name "BOM_Supplier Part") "C1591")
      )
      (libsource (lib "") (part "CL10B104KB8NNNC"))
    )
    (comp (ref "C348")
      (value "100pF")
      (fields
        (field (name "BOM_Manufacturer Part") "CL10C101JB8NNNC")
        (field (name "BOM_Supplier Part") "C14858")
      )
      (libsource (lib "") (part "CL10C101JB8NNNC"))
    )
    (comp (ref "C349")
      (value "100nF")
      (fields
        (field (name "BOM_Manufacturer Part") "CL10B104KB8NNNC")
        (field (name "BOM_Supplier Part") "C1591")
      )
      (libsource (lib "") (part "CL10B104KB8NNNC"))
    )
    (comp (ref "C350")
      (value "100pF")
      (fields
        (field (name "BOM_Manufacturer Part") "CL10C101JB8NNNC")
        (field (name "BOM_Supplier Part") "C14858")
      )
      (libsource (lib "") (part "CL10C101JB8NNNC"))
    )
    (comp (ref "C351")
      (value "100nF")
      (fields
        (field (name "BOM_Manufacturer Part") "CL10B104KB8NNNC")
        (field (name "BOM_Supplier Part") "C1591")
      )
      (libsource (lib "") (part "CL10B104KB8NNNC"))
    )
    (comp (ref "C352")
      (value "100pF")
      (fields
        (field (name "BOM_Manufacturer Part") "CL10C101JB8NNNC")
        (field (name "BOM_Supplier Part") "C14858")
      )
      (libsource (lib "") (part "CL10C101JB8NNNC"))
    )
    (comp (ref "C353")
      (value "100nF")
      (fields
        (field (name "BOM_Manufacturer Part") "CL10B104KB8NNNC")
        (field (name "BOM_Supplier Part") "C1591")
      )
      (libsource (lib "") (part "CL10B104KB8NNNC"))
    )
    (comp (ref "C354")
      (value "100pF")
      (fields
        (field (name "BOM_Manufacturer Part") "CL10C101JB8NNNC")
        (field (name "BOM_Supplier Part") "C14858")
      )
      (libsource (lib "") (part "CL10C101JB8NNNC"))
    )
    (comp (ref "C355")
      (value "100pF")
      (fields
        (field (name "BOM_Manufacturer Part") "CL10C101JB8NNNC")
        (field (name "BOM_Supplier Part") "C14858")
      )
      (libsource (lib "") (part "CL10C101JB8NNNC"))
    )
    (comp (ref "C356")
      (value "100nF")
      (fields
        (field (name "BOM_Manufacturer Part") "CL10B104KB8NNNC")
        (field (name "BOM_Supplier Part") "C1591")
      )
      (libsource (lib "") (part "CL10B104KB8NNNC"))
    )
    (comp (ref "C357")
      (value "100pF")
      (fields
        (field (name "BOM_Manufacturer Part") "CL10C101JB8NNNC")
        (field (name "BOM_Supplier Part") "C14858")
      )
      (libsource (lib "") (part "CL10C101JB8NNNC"))
    )
    (comp (ref "C358")
      (value "100nF")
      (fields
        (field (name "BOM_Manufacturer Part") "CL10B104KB8NNNC")
        (field (name "BOM_Supplier Part") "C1591")
      )
      (libsource (lib "") (part "CL10B104KB8NNNC"))
    )
    (comp (ref "C359")
      (value "100pF")
      (fields
        (field (name "BOM_Manufacturer Part") "CL10C101JB8NNNC")
        (field (name "BOM_Supplier Part") "C14858")
      )
      (libsource (lib "") (part "CL10C101JB8NNNC"))
    )
    (comp (ref "C360")
      (value "100nF")
      (fields
        (field (name "BOM_Manufacturer Part") "CL10B104KB8NNNC")
        (field (name "BOM_Supplier Part") "C1591")
      )
      (libsource (lib "") (part "CL10B104KB8NNNC"))
    )
    (comp (ref "C361")
      (value "100pF")
      (fields
        (field (name "BOM_Manufacturer Part") "CL10C101JB8NNNC")
        (field (name "BOM_Supplier Part") "C14858")
      )
      (libsource (lib "") (part "CL10C101JB8NNNC"))
    )
    (comp (ref "C362")
      (value "100nF")
      (fields
        (field (name "BOM_Manufacturer Part") "CL10B104KB8NNNC")
        (field (name "BOM_Supplier Part") "C1591")
      )
      (libsource (lib "") (part "CL10B104KB8NNNC"))
    )
    (comp (ref "C363")
      (value "100pF")
      (fields
        (field (name "BOM_Manufacturer Part") "CL10C101JB8NNNC")
        (field (name "BOM_Supplier Part") "C14858")
      )
      (libsource (lib "") (part "CL10C101JB8NNNC"))
    )
    (comp (ref "C364")
      (value "100nF")
      (fields
        (field (name "BOM_Manufacturer Part") "CL10B104KB8NNNC")
        (field (name "BOM_Supplier Part") "C1591")
      )
      (libsource (lib "") (part "CL10B104KB8NNNC"))
    )
    (comp (ref "C365")
      (value "100pF")
      (fields
        (field (name "BOM_Manufacturer Part") "CL10C101JB8NNNC")
        (field (name "BOM_Supplier Part") "C14858")
      )
      (libsource (lib "") (part "CL10C101JB8NNNC"))
    )
    (comp (ref "C366")
      (value "100nF")
      (fields
        (field (name "BOM_Manufacturer Part") "CL10B104KB8NNNC")
        (field (name "BOM_Supplier Part") "C1591")
      )
      (libsource (lib "") (part "CL10B104KB8NNNC"))
    )
    (comp (ref "C367")
      (value "100pF")
      (fields
        (field (name "BOM_Manufacturer Part") "CL10C101JB8NNNC")
        (field (name "BOM_Supplier Part") "C14858")
      )
      (libsource (lib "") (part "CL10C101JB8NNNC"))
    )
    (comp (ref "C368")
      (value "100nF")
      (fields
        (field (name "BOM_Manufacturer Part") "CL10B104KB8NNNC")
        (field (name "BOM_Supplier Part") "C1591")
      )
      (libsource (lib "") (part "CL10B104KB8NNNC"))
    )
    (comp (ref "C369")
      (value "100pF")
      (fields
        (field (name "BOM_Manufacturer Part") "CL10C101JB8NNNC")
        (field (name "BOM_Supplier Part") "C14858")
      )
      (libsource (lib "") (part "CL10C101JB8NNNC"))
    )
    (comp (ref "C370")
      (value "100nF")
      (fields
        (field (name "BOM_Manufacturer Part") "CL10B104KB8NNNC")
        (field (name "BOM_Supplier Part") "C1591")
      )
      (libsource (lib "") (part "CL10B104KB8NNNC"))
    )
    (comp (ref "C371")
      (value "100pF")
      (fields
        (field (name "BOM_Manufacturer Part") "CL10C101JB8NNNC")
        (field (name "BOM_Supplier Part") "C14858")
      )
      (libsource (lib "") (part "CL10C101JB8NNNC"))
    )
    (comp (ref "C372")
      (value "100nF")
      (fields
        (field (name "BOM_Manufacturer Part") "CL10B104KB8NNNC")
        (field (name "BOM_Supplier Part") "C1591")
      )
      (libsource (lib "") (part "CL10B104KB8NNNC"))
    )
    (comp (ref "C373")
      (value "100pF")
      (fields
        (field (name "BOM_Manufacturer Part") "CL10C101JB8NNNC")
        (field (name "BOM_Supplier Part") "C14858")
      )
      (libsource (lib "") (part "CL10C101JB8NNNC"))
    )
    (comp (ref "C374")
      (value "100nF")
      (fields
        (field (name "BOM_Manufacturer Part") "CL10B104KB8NNNC")
        (field (name "BOM_Supplier Part") "C1591")
      )
      (libsource (lib "") (part "CL10B104KB8NNNC"))
    )
    (comp (ref "C375")
      (value "100pF")
      (fields
        (field (name "BOM_Manufacturer Part") "CL10C101JB8NNNC")
        (field (name "BOM_Supplier Part") "C14858")
      )
      (libsource (lib "") (part "CL10C101JB8NNNC"))
    )
    (comp (ref "C376")
      (value "100nF")
      (fields
        (field (name "BOM_Manufacturer Part") "CL10B104KB8NNNC")
        (field (name "BOM_Supplier Part") "C1591")
      )
      (libsource (lib "") (part "CL10B104KB8NNNC"))
    )
    (comp (ref "C377")
      (value "100pF")
      (fields
        (field (name "BOM_Manufacturer Part") "CL10C101JB8NNNC")
        (field (name "BOM_Supplier Part") "C14858")
      )
      (libsource (lib "") (part "CL10C101JB8NNNC"))
    )
    (comp (ref "C378")
      (value "100nF")
      (fields
        (field (name "BOM_Manufacturer Part") "CL10B104KB8NNNC")
        (field (name "BOM_Supplier Part") "C1591")
      )
      (libsource (lib "") (part "CL10B104KB8NNNC"))
    )
    (comp (ref "C379")
      (value "100pF")
      (fields
        (field (name "BOM_Manufacturer Part") "CL10C101JB8NNNC")
        (field (name "BOM_Supplier Part") "C14858")
      )
      (libsource (lib "") (part "CL10C101JB8NNNC"))
    )
    (comp (ref "C380")
      (value "100nF")
      (fields
        (field (name "BOM_Manufacturer Part") "CL10B104KB8NNNC")
        (field (name "BOM_Supplier Part") "C1591")
      )
      (libsource (lib "") (part "CL10B104KB8NNNC"))
    )
    (comp (ref "C381")
      (value "100pF")
      (fields
        (field (name "BOM_Manufacturer Part") "CL10C101JB8NNNC")
        (field (name "BOM_Supplier Part") "C14858")
      )
      (libsource (lib "") (part "CL10C101JB8NNNC"))
    )
    (comp (ref "C382")
      (value "100nF")
      (fields
        (field (name "BOM_Manufacturer Part") "CL10B104KB8NNNC")
        (field (name "BOM_Supplier Part") "C1591")
      )
      (libsource (lib "") (part "CL10B104KB8NNNC"))
    )
    (comp (ref "C383")
      (value "100pF")
      (fields
        (field (name "BOM_Manufacturer Part") "CL10C101JB8NNNC")
        (field (name "BOM_Supplier Part") "C14858")
      )
      (libsource (lib "") (part "CL10C101JB8NNNC"))
    )
    (comp (ref "C384")
      (value "100nF")
      (fields
        (field (name "BOM_Manufacturer Part") "CL10B104KB8NNNC")
        (field (name "BOM_Supplier Part") "C1591")
      )
      (libsource (lib "") (part "CL10B104KB8NNNC"))
    )
    (comp (ref "C385")
      (value "100pF")
      (fields
        (field (name "BOM_Manufacturer Part") "CL10C101JB8NNNC")
        (field (name "BOM_Supplier Part") "C14858")
      )
      (libsource (lib "") (part "CL10C101JB8NNNC"))
    )
    (comp (ref "C386")
      (value "100nF")
      (fields
        (field (name "BOM_Manufacturer Part") "CL10B104KB8NNNC")
        (field (name "BOM_Supplier Part") "C1591")
      )
      (libsource (lib "") (part "CL10B104KB8NNNC"))
    )
    (comp (ref "C387")
      (value "100nF")
      (fields
        (field (name "BOM_Manufacturer Part") "CL10B104KB8NNNC")
        (field (name "BOM_Supplier Part") "C1591")
      )
      (libsource (lib "") (part "CL10B104KB8NNNC"))
    )
    (comp (ref "C388")
      (value "100pF")
      (fields
        (field (name "BOM_Manufacturer Part") "CL10C101JB8NNNC")
        (field (name "BOM_Supplier Part") "C14858")
      )
      (libsource (lib "") (part "CL10C101JB8NNNC"))
    )
    (comp (ref "C389")
      (value "100nF")
      (fields
        (field (name "BOM_Manufacturer Part") "CL10B104KB8NNNC")
        (field (name "BOM_Supplier Part") "C1591")
      )
      (libsource (lib "") (part "CL10B104KB8NNNC"))
    )
    (comp (ref "C390")
      (value "100pF")
      (fields
        (field (name "BOM_Manufacturer Part") "CL10C101JB8NNNC")
        (field (name "BOM_Supplier Part") "C14858")
      )
      (libsource (lib "") (part "CL10C101JB8NNNC"))
    )
    (comp (ref "C391")
      (value "100nF")
      (fields
        (field (name "BOM_Manufacturer Part") "CL10B104KB8NNNC")
        (field (name "BOM_Supplier Part") "C1591")
      )
      (libsource (lib "") (part "CL10B104KB8NNNC"))
    )
    (comp (ref "C392")
      (value "100pF")
      (fields
        (field (name "BOM_Manufacturer Part") "CL10C101JB8NNNC")
        (field (name "BOM_Supplier Part") "C14858")
      )
      (libsource (lib "") (part "CL10C101JB8NNNC"))
    )
    (comp (ref "C393")
      (value "100nF")
      (fields
        (field (name "BOM_Manufacturer Part") "CL10B104KB8NNNC")
        (field (name "BOM_Supplier Part") "C1591")
      )
      (libsource (lib "") (part "CL10B104KB8NNNC"))
    )
    (comp (ref "C394")
      (value "100pF")
      (fields
        (field (name "BOM_Manufacturer Part") "CL10C101JB8NNNC")
        (field (name "BOM_Supplier Part") "C14858")
      )
      (libsource (lib "") (part "CL10C101JB8NNNC"))
    )
    (comp (ref "C395")
      (value "100nF")
      (fields
        (field (name "BOM_Manufacturer Part") "CL10B104KB8NNNC")
        (field (name "BOM_Supplier Part") "C1591")
      )
      (libsource (lib "") (part "CL10B104KB8NNNC"))
    )
    (comp (ref "C396")
      (value "100pF")
      (fields
        (field (name "BOM_Manufacturer Part") "CL10C101JB8NNNC")
        (field (name "BOM_Supplier Part") "C14858")
      )
      (libsource (lib "") (part "CL10C101JB8NNNC"))
    )
    (comp (ref "C397")
      (value "100nF")
      (fields
        (field (name "BOM_Manufacturer Part") "CL10B104KB8NNNC")
        (field (name "BOM_Supplier Part") "C1591")
      )
      (libsource (lib "") (part "CL10B104KB8NNNC"))
    )
    (comp (ref "C398")
      (value "100pF")
      (fields
        (field (name "BOM_Manufacturer Part") "CL10C101JB8NNNC")
        (field (name "BOM_Supplier Part") "C14858")
      )
      (libsource (lib "") (part "CL10C101JB8NNNC"))
    )
    (comp (ref "C399")
      (value "100nF")
      (fields
        (field (name "BOM_Manufacturer Part") "CL10B104KB8NNNC")
        (field (name "BOM_Supplier Part") "C1591")
      )
      (libsource (lib "") (part "CL10B104KB8NNNC"))
    )
    (comp (ref "C400")
      (value "100pF")
      (fields
        (field (name "BOM_Manufacturer Part") "CL10C101JB8NNNC")
        (field (name "BOM_Supplier Part") "C14858")
      )
      (libsource (lib "") (part "CL10C101JB8NNNC"))
    )
    (comp (ref "C401")
      (value "100nF")
      (fields
        (field (name "BOM_Manufacturer Part") "CL10B104KB8NNNC")
        (field (name "BOM_Supplier Part") "C1591")
      )
      (libsource (lib "") (part "CL10B104KB8NNNC"))
    )
    (comp (ref "C402")
      (value "100pF")
      (fields
        (field (name "BOM_Manufacturer Part") "CL10C101JB8NNNC")
        (field (name "BOM_Supplier Part") "C14858")
      )
      (libsource (lib "") (part "CL10C101JB8NNNC"))
    )
    (comp (ref "C403")
      (value "100nF")
      (fields
        (field (name "BOM_Manufacturer Part") "CL10B104KB8NNNC")
        (field (name "BOM_Supplier Part") "C1591")
      )
      (libsource (lib "") (part "CL10B104KB8NNNC"))
    )
    (comp (ref "C404")
      (value "100pF")
      (fields
        (field (name "BOM_Manufacturer Part") "CL10C101JB8NNNC")
        (field (name "BOM_Supplier Part") "C14858")
      )
      (libsource (lib "") (part "CL10C101JB8NNNC"))
    )
    (comp (ref "C405")
      (value "100nF")
      (fields
        (field (name "BOM_Manufacturer Part") "CL10B104KB8NNNC")
        (field (name "BOM_Supplier Part") "C1591")
      )
      (libsource (lib "") (part "CL10B104KB8NNNC"))
    )
    (comp (ref "C406")
      (value "100pF")
      (fields
        (field (name "BOM_Manufacturer Part") "CL10C101JB8NNNC")
        (field (name "BOM_Supplier Part") "C14858")
      )
      (libsource (lib "") (part "CL10C101JB8NNNC"))
    )
    (comp (ref "C407")
      (value "100nF")
      (fields
        (field (name "BOM_Manufacturer Part") "CL10B104KB8NNNC")
        (field (name "BOM_Supplier Part") "C1591")
      )
      (libsource (lib "") (part "CL10B104KB8NNNC"))
    )
    (comp (ref "C408")
      (value "100pF")
      (fields
        (field (name "BOM_Manufacturer Part") "CL10C101JB8NNNC")
        (field (name "BOM_Supplier Part") "C14858")
      )
      (libsource (lib "") (part "CL10C101JB8NNNC"))
    )
    (comp (ref "C409")
      (value "100nF")
      (fields
        (field (name "BOM_Manufacturer Part") "CL10B104KB8NNNC")
        (field (name "BOM_Supplier Part") "C1591")
      )
      (libsource (lib "") (part "CL10B104KB8NNNC"))
    )
    (comp (ref "C410")
      (value "100pF")
      (fields
        (field (name "BOM_Manufacturer Part") "CL10C101JB8NNNC")
        (field (name "BOM_Supplier Part") "C14858")
      )
      (libsource (lib "") (part "CL10C101JB8NNNC"))
    )
    (comp (ref "C411")
      (value "100nF")
      (fields
        (field (name "BOM_Manufacturer Part") "CL10B104KB8NNNC")
        (field (name "BOM_Supplier Part") "C1591")
      )
      (libsource (lib "") (part "CL10B104KB8NNNC"))
    )
    (comp (ref "C412")
      (value "100pF")
      (fields
        (field (name "BOM_Manufacturer Part") "CL10C101JB8NNNC")
        (field (name "BOM_Supplier Part") "C14858")
      )
      (libsource (lib "") (part "CL10C101JB8NNNC"))
    )
    (comp (ref "C413")
      (value "100nF")
      (fields
        (field (name "BOM_Manufacturer Part") "CL10B104KB8NNNC")
        (field (name "BOM_Supplier Part") "C1591")
      )
      (libsource (lib "") (part "CL10B104KB8NNNC"))
    )
    (comp (ref "C414")
      (value "100pF")
      (fields
        (field (name "BOM_Manufacturer Part") "CL10C101JB8NNNC")
        (field (name "BOM_Supplier Part") "C14858")
      )
      (libsource (lib "") (part "CL10C101JB8NNNC"))
    )
    (comp (ref "C415")
      (value "100nF")
      (fields
        (field (name "BOM_Manufacturer Part") "CL10B104KB8NNNC")
        (field (name "BOM_Supplier Part") "C1591")
      )
      (libsource (lib "") (part "CL10B104KB8NNNC"))
    )
    (comp (ref "C416")
      (value "100pF")
      (fields
        (field (name "BOM_Manufacturer Part") "CL10C101JB8NNNC")
        (field (name "BOM_Supplier Part") "C14858")
      )
      (libsource (lib "") (part "CL10C101JB8NNNC"))
    )
    (comp (ref "C417")
      (value "100nF")
      (fields
        (field (name "BOM_Manufacturer Part") "CL10B104KB8NNNC")
        (field (name "BOM_Supplier Part") "C1591")
      )
      (libsource (lib "") (part "CL10B104KB8NNNC"))
    )
    (comp (ref "C418")
      (value "100pF")
      (fields
        (field (name "BOM_Manufacturer Part") "CL10C101JB8NNNC")
        (field (name "BOM_Supplier Part") "C14858")
      )
      (libsource (lib "") (part "CL10C101JB8NNNC"))
    )
    (comp (ref "C419")
      (value "100pF")
      (fields
        (field (name "BOM_Manufacturer Part") "CL10C101JB8NNNC")
        (field (name "BOM_Supplier Part") "C14858")
      )
      (libsource (lib "") (part "CL10C101JB8NNNC"))
    )
    (comp (ref "C420")
      (value "100nF")
      (fields
        (field (name "BOM_Manufacturer Part") "CL10B104KB8NNNC")
        (field (name "BOM_Supplier Part") "C1591")
      )
      (libsource (lib "") (part "CL10B104KB8NNNC"))
    )
    (comp (ref "C421")
      (value "100pF")
      (fields
        (field (name "BOM_Manufacturer Part") "CL10C101JB8NNNC")
        (field (name "BOM_Supplier Part") "C14858")
      )
      (libsource (lib "") (part "CL10C101JB8NNNC"))
    )
    (comp (ref "C422")
      (value "100nF")
      (fields
        (field (name "BOM_Manufacturer Part") "CL10B104KB8NNNC")
        (field (name "BOM_Supplier Part") "C1591")
      )
      (libsource (lib "") (part "CL10B104KB8NNNC"))
    )
    (comp (ref "C423")
      (value "100pF")
      (fields
        (field (name "BOM_Manufacturer Part") "CL10C101JB8NNNC")
        (field (name "BOM_Supplier Part") "C14858")
      )
      (libsource (lib "") (part "CL10C101JB8NNNC"))
    )
    (comp (ref "C424")
      (value "100nF")
      (fields
        (field (name "BOM_Manufacturer Part") "CL10B104KB8NNNC")
        (field (name "BOM_Supplier Part") "C1591")
      )
      (libsource (lib "") (part "CL10B104KB8NNNC"))
    )
    (comp (ref "C425")
      (value "100pF")
      (fields
        (field (name "BOM_Manufacturer Part") "CL10C101JB8NNNC")
        (field (name "BOM_Supplier Part") "C14858")
      )
      (libsource (lib "") (part "CL10C101JB8NNNC"))
    )
    (comp (ref "C426")
      (value "100nF")
      (fields
        (field (name "BOM_Manufacturer Part") "CL10B104KB8NNNC")
        (field (name "BOM_Supplier Part") "C1591")
      )
      (libsource (lib "") (part "CL10B104KB8NNNC"))
    )
    (comp (ref "C427")
      (value "100pF")
      (fields
        (field (name "BOM_Manufacturer Part") "CL10C101JB8NNNC")
        (field (name "BOM_Supplier Part") "C14858")
      )
      (libsource (lib "") (part "CL10C101JB8NNNC"))
    )
    (comp (ref "C428")
      (value "100nF")
      (fields
        (field (name "BOM_Manufacturer Part") "CL10B104KB8NNNC")
        (field (name "BOM_Supplier Part") "C1591")
      )
      (libsource (lib "") (part "CL10B104KB8NNNC"))
    )
    (comp (ref "C429")
      (value "100pF")
      (fields
        (field (name "BOM_Manufacturer Part") "CL10C101JB8NNNC")
        (field (name "BOM_Supplier Part") "C14858")
      )
      (libsource (lib "") (part "CL10C101JB8NNNC"))
    )
    (comp (ref "C430")
      (value "100nF")
      (fields
        (field (name "BOM_Manufacturer Part") "CL10B104KB8NNNC")
        (field (name "BOM_Supplier Part") "C1591")
      )
      (libsource (lib "") (part "CL10B104KB8NNNC"))
    )
    (comp (ref "C431")
      (value "100pF")
      (fields
        (field (name "BOM_Manufacturer Part") "CL10C101JB8NNNC")
        (field (name "BOM_Supplier Part") "C14858")
      )
      (libsource (lib "") (part "CL10C101JB8NNNC"))
    )
    (comp (ref "C432")
      (value "100nF")
      (fields
        (field (name "BOM_Manufacturer Part") "CL10B104KB8NNNC")
        (field (name "BOM_Supplier Part") "C1591")
      )
      (libsource (lib "") (part "CL10B104KB8NNNC"))
    )
    (comp (ref "C433")
      (value "100pF")
      (fields
        (field (name "BOM_Manufacturer Part") "CL10C101JB8NNNC")
        (field (name "BOM_Supplier Part") "C14858")
      )
      (libsource (lib "") (part "CL10C101JB8NNNC"))
    )
    (comp (ref "C434")
      (value "100nF")
      (fields
        (field (name "BOM_Manufacturer Part") "CL10B104KB8NNNC")
        (field (name "BOM_Supplier Part") "C1591")
      )
      (libsource (lib "") (part "CL10B104KB8NNNC"))
    )
    (comp (ref "C435")
      (value "100pF")
      (fields
        (field (name "BOM_Manufacturer Part") "CL10C101JB8NNNC")
        (field (name "BOM_Supplier Part") "C14858")
      )
      (libsource (lib "") (part "CL10C101JB8NNNC"))
    )
    (comp (ref "C436")
      (value "100nF")
      (fields
        (field (name "BOM_Manufacturer Part") "CL10B104KB8NNNC")
        (field (name "BOM_Supplier Part") "C1591")
      )
      (libsource (lib "") (part "CL10B104KB8NNNC"))
    )
    (comp (ref "C437")
      (value "100pF")
      (fields
        (field (name "BOM_Manufacturer Part") "CL10C101JB8NNNC")
        (field (name "BOM_Supplier Part") "C14858")
      )
      (libsource (lib "") (part "CL10C101JB8NNNC"))
    )
    (comp (ref "C438")
      (value "100nF")
      (fields
        (field (name "BOM_Manufacturer Part") "CL10B104KB8NNNC")
        (field (name "BOM_Supplier Part") "C1591")
      )
      (libsource (lib "") (part "CL10B104KB8NNNC"))
    )
    (comp (ref "C439")
      (value "100pF")
      (fields
        (field (name "BOM_Manufacturer Part") "CL10C101JB8NNNC")
        (field (name "BOM_Supplier Part") "C14858")
      )
      (libsource (lib "") (part "CL10C101JB8NNNC"))
    )
    (comp (ref "C440")
      (value "100nF")
      (fields
        (field (name "BOM_Manufacturer Part") "CL10B104KB8NNNC")
        (field (name "BOM_Supplier Part") "C1591")
      )
      (libsource (lib "") (part "CL10B104KB8NNNC"))
    )
    (comp (ref "C441")
      (value "100pF")
      (fields
        (field (name "BOM_Manufacturer Part") "CL10C101JB8NNNC")
        (field (name "BOM_Supplier Part") "C14858")
      )
      (libsource (lib "") (part "CL10C101JB8NNNC"))
    )
    (comp (ref "C442")
      (value "100nF")
      (fields
        (field (name "BOM_Manufacturer Part") "CL10B104KB8NNNC")
        (field (name "BOM_Supplier Part") "C1591")
      )
      (libsource (lib "") (part "CL10B104KB8NNNC"))
    )
    (comp (ref "C443")
      (value "100pF")
      (fields
        (field (name "BOM_Manufacturer Part") "CL10C101JB8NNNC")
        (field (name "BOM_Supplier Part") "C14858")
      )
      (libsource (lib "") (part "CL10C101JB8NNNC"))
    )
    (comp (ref "C444")
      (value "100nF")
      (fields
        (field (name "BOM_Manufacturer Part") "CL10B104KB8NNNC")
        (field (name "BOM_Supplier Part") "C1591")
      )
      (libsource (lib "") (part "CL10B104KB8NNNC"))
    )
    (comp (ref "C445")
      (value "100pF")
      (fields
        (field (name "BOM_Manufacturer Part") "CL10C101JB8NNNC")
        (field (name "BOM_Supplier Part") "C14858")
      )
      (libsource (lib "") (part "CL10C101JB8NNNC"))
    )
    (comp (ref "C446")
      (value "100nF")
      (fields
        (field (name "BOM_Manufacturer Part") "CL10B104KB8NNNC")
        (field (name "BOM_Supplier Part") "C1591")
      )
      (libsource (lib "") (part "CL10B104KB8NNNC"))
    )
    (comp (ref "C447")
      (value "100pF")
      (fields
        (field (name "BOM_Manufacturer Part") "CL10C101JB8NNNC")
        (field (name "BOM_Supplier Part") "C14858")
      )
      (libsource (lib "") (part "CL10C101JB8NNNC"))
    )
    (comp (ref "C448")
      (value "100nF")
      (fields
        (field (name "BOM_Manufacturer Part") "CL10B104KB8NNNC")
        (field (name "BOM_Supplier Part") "C1591")
      )
      (libsource (lib "") (part "CL10B104KB8NNNC"))
    )
    (comp (ref "C449")
      (value "100pF")
      (fields
        (field (name "BOM_Manufacturer Part") "CL10C101JB8NNNC")
        (field (name "BOM_Supplier Part") "C14858")
      )
      (libsource (lib "") (part "CL10C101JB8NNNC"))
    )
    (comp (ref "C450")
      (value "100nF")
      (fields
        (field (name "BOM_Manufacturer Part") "CL10B104KB8NNNC")
        (field (name "BOM_Supplier Part") "C1591")
      )
      (libsource (lib "") (part "CL10B104KB8NNNC"))
    )
    (comp (ref "C451")
      (value "100nF")
      (fields
        (field (name "BOM_Manufacturer Part") "CL10B104KB8NNNC")
        (field (name "BOM_Supplier Part") "C1591")
      )
      (libsource (lib "") (part "CL10B104KB8NNNC"))
    )
    (comp (ref "C452")
      (value "100pF")
      (fields
        (field (name "BOM_Manufacturer Part") "CL10C101JB8NNNC")
        (field (name "BOM_Supplier Part") "C14858")
      )
      (libsource (lib "") (part "CL10C101JB8NNNC"))
    )
    (comp (ref "C453")
      (value "100nF")
      (fields
        (field (name "BOM_Manufacturer Part") "CL10B104KB8NNNC")
        (field (name "BOM_Supplier Part") "C1591")
      )
      (libsource (lib "") (part "CL10B104KB8NNNC"))
    )
    (comp (ref "C454")
      (value "100pF")
      (fields
        (field (name "BOM_Manufacturer Part") "CL10C101JB8NNNC")
        (field (name "BOM_Supplier Part") "C14858")
      )
      (libsource (lib "") (part "CL10C101JB8NNNC"))
    )
    (comp (ref "C455")
      (value "100nF")
      (fields
        (field (name "BOM_Manufacturer Part") "CL10B104KB8NNNC")
        (field (name "BOM_Supplier Part") "C1591")
      )
      (libsource (lib "") (part "CL10B104KB8NNNC"))
    )
    (comp (ref "C456")
      (value "100pF")
      (fields
        (field (name "BOM_Manufacturer Part") "CL10C101JB8NNNC")
        (field (name "BOM_Supplier Part") "C14858")
      )
      (libsource (lib "") (part "CL10C101JB8NNNC"))
    )
    (comp (ref "C457")
      (value "100nF")
      (fields
        (field (name "BOM_Manufacturer Part") "CL10B104KB8NNNC")
        (field (name "BOM_Supplier Part") "C1591")
      )
      (libsource (lib "") (part "CL10B104KB8NNNC"))
    )
    (comp (ref "C458")
      (value "100pF")
      (fields
        (field (name "BOM_Manufacturer Part") "CL10C101JB8NNNC")
        (field (name "BOM_Supplier Part") "C14858")
      )
      (libsource (lib "") (part "CL10C101JB8NNNC"))
    )
    (comp (ref "C459")
      (value "100nF")
      (fields
        (field (name "BOM_Manufacturer Part") "CL10B104KB8NNNC")
        (field (name "BOM_Supplier Part") "C1591")
      )
      (libsource (lib "") (part "CL10B104KB8NNNC"))
    )
    (comp (ref "C460")
      (value "100pF")
      (fields
        (field (name "BOM_Manufacturer Part") "CL10C101JB8NNNC")
        (field (name "BOM_Supplier Part") "C14858")
      )
      (libsource (lib "") (part "CL10C101JB8NNNC"))
    )
    (comp (ref "C461")
      (value "100nF")
      (fields
        (field (name "BOM_Manufacturer Part") "CL10B104KB8NNNC")
        (field (name "BOM_Supplier Part") "C1591")
      )
      (libsource (lib "") (part "CL10B104KB8NNNC"))
    )
    (comp (ref "C462")
      (value "100pF")
      (fields
        (field (name "BOM_Manufacturer Part") "CL10C101JB8NNNC")
        (field (name "BOM_Supplier Part") "C14858")
      )
      (libsource (lib "") (part "CL10C101JB8NNNC"))
    )
    (comp (ref "C463")
      (value "100nF")
      (fields
        (field (name "BOM_Manufacturer Part") "CL10B104KB8NNNC")
        (field (name "BOM_Supplier Part") "C1591")
      )
      (libsource (lib "") (part "CL10B104KB8NNNC"))
    )
    (comp (ref "C464")
      (value "100pF")
      (fields
        (field (name "BOM_Manufacturer Part") "CL10C101JB8NNNC")
        (field (name "BOM_Supplier Part") "C14858")
      )
      (libsource (lib "") (part "CL10C101JB8NNNC"))
    )
    (comp (ref "C465")
      (value "100nF")
      (fields
        (field (name "BOM_Manufacturer Part") "CL10B104KB8NNNC")
        (field (name "BOM_Supplier Part") "C1591")
      )
      (libsource (lib "") (part "CL10B104KB8NNNC"))
    )
    (comp (ref "C466")
      (value "100pF")
      (fields
        (field (name "BOM_Manufacturer Part") "CL10C101JB8NNNC")
        (field (name "BOM_Supplier Part") "C14858")
      )
      (libsource (lib "") (part "CL10C101JB8NNNC"))
    )
    (comp (ref "C467")
      (value "100nF")
      (fields
        (field (name "BOM_Manufacturer Part") "CL10B104KB8NNNC")
        (field (name "BOM_Supplier Part") "C1591")
      )
      (libsource (lib "") (part "CL10B104KB8NNNC"))
    )
    (comp (ref "C468")
      (value "100pF")
      (fields
        (field (name "BOM_Manufacturer Part") "CL10C101JB8NNNC")
        (field (name "BOM_Supplier Part") "C14858")
      )
      (libsource (lib "") (part "CL10C101JB8NNNC"))
    )
    (comp (ref "C469")
      (value "100nF")
      (fields
        (field (name "BOM_Manufacturer Part") "CL10B104KB8NNNC")
        (field (name "BOM_Supplier Part") "C1591")
      )
      (libsource (lib "") (part "CL10B104KB8NNNC"))
    )
    (comp (ref "C470")
      (value "100pF")
      (fields
        (field (name "BOM_Manufacturer Part") "CL10C101JB8NNNC")
        (field (name "BOM_Supplier Part") "C14858")
      )
      (libsource (lib "") (part "CL10C101JB8NNNC"))
    )
    (comp (ref "C471")
      (value "100nF")
      (fields
        (field (name "BOM_Manufacturer Part") "CL10B104KB8NNNC")
        (field (name "BOM_Supplier Part") "C1591")
      )
      (libsource (lib "") (part "CL10B104KB8NNNC"))
    )
    (comp (ref "C472")
      (value "100pF")
      (fields
        (field (name "BOM_Manufacturer Part") "CL10C101JB8NNNC")
        (field (name "BOM_Supplier Part") "C14858")
      )
      (libsource (lib "") (part "CL10C101JB8NNNC"))
    )
    (comp (ref "C473")
      (value "100nF")
      (fields
        (field (name "BOM_Manufacturer Part") "CL10B104KB8NNNC")
        (field (name "BOM_Supplier Part") "C1591")
      )
      (libsource (lib "") (part "CL10B104KB8NNNC"))
    )
    (comp (ref "C474")
      (value "100pF")
      (fields
        (field (name "BOM_Manufacturer Part") "CL10C101JB8NNNC")
        (field (name "BOM_Supplier Part") "C14858")
      )
      (libsource (lib "") (part "CL10C101JB8NNNC"))
    )
    (comp (ref "C475")
      (value "100nF")
      (fields
        (field (name "BOM_Manufacturer Part") "CL10B104KB8NNNC")
        (field (name "BOM_Supplier Part") "C1591")
      )
      (libsource (lib "") (part "CL10B104KB8NNNC"))
    )
    (comp (ref "C476")
      (value "100pF")
      (fields
        (field (name "BOM_Manufacturer Part") "CL10C101JB8NNNC")
        (field (name "BOM_Supplier Part") "C14858")
      )
      (libsource (lib "") (part "CL10C101JB8NNNC"))
    )
    (comp (ref "C477")
      (value "100nF")
      (fields
        (field (name "BOM_Manufacturer Part") "CL10B104KB8NNNC")
        (field (name "BOM_Supplier Part") "C1591")
      )
      (libsource (lib "") (part "CL10B104KB8NNNC"))
    )
    (comp (ref "C478")
      (value "100pF")
      (fields
        (field (name "BOM_Manufacturer Part") "CL10C101JB8NNNC")
        (field (name "BOM_Supplier Part") "C14858")
      )
      (libsource (lib "") (part "CL10C101JB8NNNC"))
    )
    (comp (ref "C479")
      (value "100nF")
      (fields
        (field (name "BOM_Manufacturer Part") "CL10B104KB8NNNC")
        (field (name "BOM_Supplier Part") "C1591")
      )
      (libsource (lib "") (part "CL10B104KB8NNNC"))
    )
    (comp (ref "C480")
      (value "100pF")
      (fields
        (field (name "BOM_Manufacturer Part") "CL10C101JB8NNNC")
        (field (name "BOM_Supplier Part") "C14858")
      )
      (libsource (lib "") (part "CL10C101JB8NNNC"))
    )
    (comp (ref "C481")
      (value "100nF")
      (fields
        (field (name "BOM_Manufacturer Part") "CL10B104KB8NNNC")
        (field (name "BOM_Supplier Part") "C1591")
      )
      (libsource (lib "") (part "CL10B104KB8NNNC"))
    )
    (comp (ref "C482")
      (value "100pF")
      (fields
        (field (name "BOM_Manufacturer Part") "CL10C101JB8NNNC")
        (field (name "BOM_Supplier Part") "C14858")
      )
      (libsource (lib "") (part "CL10C101JB8NNNC"))
    )
    (comp (ref "C483")
      (value "100pF")
      (fields
        (field (name "BOM_Manufacturer Part") "CL10C101JB8NNNC")
        (field (name "BOM_Supplier Part") "C14858")
      )
      (libsource (lib "") (part "CL10C101JB8NNNC"))
    )
    (comp (ref "C484")
      (value "100nF")
      (fields
        (field (name "BOM_Manufacturer Part") "CL10B104KB8NNNC")
        (field (name "BOM_Supplier Part") "C1591")
      )
      (libsource (lib "") (part "CL10B104KB8NNNC"))
    )
    (comp (ref "C485")
      (value "100pF")
      (fields
        (field (name "BOM_Manufacturer Part") "CL10C101JB8NNNC")
        (field (name "BOM_Supplier Part") "C14858")
      )
      (libsource (lib "") (part "CL10C101JB8NNNC"))
    )
    (comp (ref "C486")
      (value "100nF")
      (fields
        (field (name "BOM_Manufacturer Part") "CL10B104KB8NNNC")
        (field (name "BOM_Supplier Part") "C1591")
      )
      (libsource (lib "") (part "CL10B104KB8NNNC"))
    )
    (comp (ref "C487")
      (value "100pF")
      (fields
        (field (name "BOM_Manufacturer Part") "CL10C101JB8NNNC")
        (field (name "BOM_Supplier Part") "C14858")
      )
      (libsource (lib "") (part "CL10C101JB8NNNC"))
    )
    (comp (ref "C488")
      (value "100nF")
      (fields
        (field (name "BOM_Manufacturer Part") "CL10B104KB8NNNC")
        (field (name "BOM_Supplier Part") "C1591")
      )
      (libsource (lib "") (part "CL10B104KB8NNNC"))
    )
    (comp (ref "C489")
      (value "100pF")
      (fields
        (field (name "BOM_Manufacturer Part") "CL10C101JB8NNNC")
        (field (name "BOM_Supplier Part") "C14858")
      )
      (libsource (lib "") (part "CL10C101JB8NNNC"))
    )
    (comp (ref "C490")
      (value "100nF")
      (fields
        (field (name "BOM_Manufacturer Part") "CL10B104KB8NNNC")
        (field (name "BOM_Supplier Part") "C1591")
      )
      (libsource (lib "") (part "CL10B104KB8NNNC"))
    )
    (comp (ref "C491")
      (value "100pF")
      (fields
        (field (name "BOM_Manufacturer Part") "CL10C101JB8NNNC")
        (field (name "BOM_Supplier Part") "C14858")
      )
      (libsource (lib "") (part "CL10C101JB8NNNC"))
    )
    (comp (ref "C492")
      (value "100nF")
      (fields
        (field (name "BOM_Manufacturer Part") "CL10B104KB8NNNC")
        (field (name "BOM_Supplier Part") "C1591")
      )
      (libsource (lib "") (part "CL10B104KB8NNNC"))
    )
    (comp (ref "C493")
      (value "100pF")
      (fields
        (field (name "BOM_Manufacturer Part") "CL10C101JB8NNNC")
        (field (name "BOM_Supplier Part") "C14858")
      )
      (libsource (lib "") (part "CL10C101JB8NNNC"))
    )
    (comp (ref "C494")
      (value "100nF")
      (fields
        (field (name "BOM_Manufacturer Part") "CL10B104KB8NNNC")
        (field (name "BOM_Supplier Part") "C1591")
      )
      (libsource (lib "") (part "CL10B104KB8NNNC"))
    )
    (comp (ref "C495")
      (value "100pF")
      (fields
        (field (name "BOM_Manufacturer Part") "CL10C101JB8NNNC")
        (field (name "BOM_Supplier Part") "C14858")
      )
      (libsource (lib "") (part "CL10C101JB8NNNC"))
    )
    (comp (ref "C496")
      (value "100nF")
      (fields
        (field (name "BOM_Manufacturer Part") "CL10B104KB8NNNC")
        (field (name "BOM_Supplier Part") "C1591")
      )
      (libsource (lib "") (part "CL10B104KB8NNNC"))
    )
    (comp (ref "C497")
      (value "100pF")
      (fields
        (field (name "BOM_Manufacturer Part") "CL10C101JB8NNNC")
        (field (name "BOM_Supplier Part") "C14858")
      )
      (libsource (lib "") (part "CL10C101JB8NNNC"))
    )
    (comp (ref "C498")
      (value "100nF")
      (fields
        (field (name "BOM_Manufacturer Part") "CL10B104KB8NNNC")
        (field (name "BOM_Supplier Part") "C1591")
      )
      (libsource (lib "") (part "CL10B104KB8NNNC"))
    )
    (comp (ref "C499")
      (value "100pF")
      (fields
        (field (name "BOM_Manufacturer Part") "CL10C101JB8NNNC")
        (field (name "BOM_Supplier Part") "C14858")
      )
      (libsource (lib "") (part "CL10C101JB8NNNC"))
    )
    (comp (ref "C500")
      (value "100nF")
      (fields
        (field (name "BOM_Manufacturer Part") "CL10B104KB8NNNC")
        (field (name "BOM_Supplier Part") "C1591")
      )
      (libsource (lib "") (part "CL10B104KB8NNNC"))
    )
    (comp (ref "C501")
      (value "100pF")
      (fields
        (field (name "BOM_Manufacturer Part") "CL10C101JB8NNNC")
        (field (name "BOM_Supplier Part") "C14858")
      )
      (libsource (lib "") (part "CL10C101JB8NNNC"))
    )
    (comp (ref "C502")
      (value "100nF")
      (fields
        (field (name "BOM_Manufacturer Part") "CL10B104KB8NNNC")
        (field (name "BOM_Supplier Part") "C1591")
      )
      (libsource (lib "") (part "CL10B104KB8NNNC"))
    )
    (comp (ref "C503")
      (value "100pF")
      (fields
        (field (name "BOM_Manufacturer Part") "CL10C101JB8NNNC")
        (field (name "BOM_Supplier Part") "C14858")
      )
      (libsource (lib "") (part "CL10C101JB8NNNC"))
    )
    (comp (ref "C504")
      (value "100nF")
      (fields
        (field (name "BOM_Manufacturer Part") "CL10B104KB8NNNC")
        (field (name "BOM_Supplier Part") "C1591")
      )
      (libsource (lib "") (part "CL10B104KB8NNNC"))
    )
    (comp (ref "C505")
      (value "100pF")
      (fields
        (field (name "BOM_Manufacturer Part") "CL10C101JB8NNNC")
        (field (name "BOM_Supplier Part") "C14858")
      )
      (libsource (lib "") (part "CL10C101JB8NNNC"))
    )
    (comp (ref "C506")
      (value "100nF")
      (fields
        (field (name "BOM_Manufacturer Part") "CL10B104KB8NNNC")
        (field (name "BOM_Supplier Part") "C1591")
      )
      (libsource (lib "") (part "CL10B104KB8NNNC"))
    )
    (comp (ref "C507")
      (value "100pF")
      (fields
        (field (name "BOM_Manufacturer Part") "CL10C101JB8NNNC")
        (field (name "BOM_Supplier Part") "C14858")
      )
      (libsource (lib "") (part "CL10C101JB8NNNC"))
    )
    (comp (ref "C508")
      (value "100nF")
      (fields
        (field (name "BOM_Manufacturer Part") "CL10B104KB8NNNC")
        (field (name "BOM_Supplier Part") "C1591")
      )
      (libsource (lib "") (part "CL10B104KB8NNNC"))
    )
    (comp (ref "C509")
      (value "100pF")
      (fields
        (field (name "BOM_Manufacturer Part") "CL10C101JB8NNNC")
        (field (name "BOM_Supplier Part") "C14858")
      )
      (libsource (lib "") (part "CL10C101JB8NNNC"))
    )
    (comp (ref "C510")
      (value "100nF")
      (fields
        (field (name "BOM_Manufacturer Part") "CL10B104KB8NNNC")
        (field (name "BOM_Supplier Part") "C1591")
      )
      (libsource (lib "") (part "CL10B104KB8NNNC"))
    )
    (comp (ref "C511")
      (value "100pF")
      (fields
        (field (name "BOM_Manufacturer Part") "CL10C101JB8NNNC")
        (field (name "BOM_Supplier Part") "C14858")
      )
      (libsource (lib "") (part "CL10C101JB8NNNC"))
    )
    (comp (ref "C512")
      (value "100nF")
      (fields
        (field (name "BOM_Manufacturer Part") "CL10B104KB8NNNC")
        (field (name "BOM_Supplier Part") "C1591")
      )
      (libsource (lib "") (part "CL10B104KB8NNNC"))
    )
    (comp (ref "X1Y1")
      (value "AH49HSC")
      (fields (field (name "BOM_Supplier Part") "C510723"))
      (libsource (lib "") (part "AH49HSC_11"))
    )
    (comp (ref "X1Y2")
      (value "AH49HSC")
      (fields (field (name "BOM_Supplier Part") "C510723"))
      (libsource (lib "") (part "AH49HSC_11"))
    )
    (comp (ref "X1Y3")
      (value "AH49HSC")
      (fields (field (name "BOM_Supplier Part") "C510723"))
      (libsource (lib "") (part "AH49HSC_11"))
    )
    (comp (ref "X1Y4")
      (value "AH49HSC")
      (fields (field (name "BOM_Supplier Part") "C510723"))
      (libsource (lib "") (part "AH49HSC_11"))
    )
    (comp (ref "X1Y5")
      (value "AH49HSC")
      (fields (field (name "BOM_Supplier Part") "C510723"))
      (libsource (lib "") (part "AH49HSC_11"))
    )
    (comp (ref "X1Y6")
      (value "AH49HSC")
      (fields (field (name "BOM_Supplier Part") "C510723"))
      (libsource (lib "") (part "AH49HSC_11"))
    )
    (comp (ref "X1Y7")
      (value "AH49HSC")
      (fields (field (name "BOM_Supplier Part") "C510723"))
      (libsource (lib "") (part "AH49HSC_11"))
    )
    (comp (ref "X1Y8")
      (value "AH49HSC")
      (fields (field (name "BOM_Supplier Part") "C510723"))
      (libsource (lib "") (part "AH49HSC_11"))
    )
    (comp (ref "X1Y9")
      (value "AH49HSC")
      (fields (field (name "BOM_Supplier Part") "C510723"))
      (libsource (lib "") (part "AH49HSC_11"))
    )
    (comp (ref "X1Y10")
      (value "AH49HSC")
      (fields (field (name "BOM_Supplier Part") "C510723"))
      (libsource (lib "") (part "AH49HSC_11"))
    )
    (comp (ref "X1Y11")
      (value "AH49HSC")
      (fields (field (name "BOM_Supplier Part") "C510723"))
      (libsource (lib "") (part "AH49HSC_11"))
    )
    (comp (ref "X1Y12")
      (value "AH49HSC")
      (fields (field (name "BOM_Supplier Part") "C510723"))
      (libsource (lib "") (part "AH49HSC_11"))
    )
    (comp (ref "X1Y13")
      (value "AH49HSC")
      (fields (field (name "BOM_Supplier Part") "C510723"))
      (libsource (lib "") (part "AH49HSC_11"))
    )
    (comp (ref "X1Y14")
      (value "AH49HSC")
      (fields (field (name "BOM_Supplier Part") "C510723"))
      (libsource (lib "") (part "AH49HSC_11"))
    )
    (comp (ref "X1Y15")
      (value "AH49HSC")
      (fields (field (name "BOM_Supplier Part") "C510723"))
      (libsource (lib "") (part "AH49HSC_11"))
    )
    (comp (ref "X1Y16")
      (value "AH49HSC")
      (fields (field (name "BOM_Supplier Part") "C510723"))
      (libsource (lib "") (part "AH49HSC_11"))
    )
    (comp (ref "X2Y1")
      (value "AH49HSC")
      (fields (field (name "BOM_Supplier Part") "C510723"))
      (libsource (lib "") (part "AH49HSC_8"))
    )
    (comp (ref "X2Y2")
      (value "AH49HSC")
      (fields (field (name "BOM_Supplier Part") "C510723"))
      (libsource (lib "") (part "AH49HSC_8"))
    )
    (comp (ref "X2Y3")
      (value "AH49HSC")
      (fields (field (name "BOM_Supplier Part") "C510723"))
      (libsource (lib "") (part "AH49HSC_8"))
    )
    (comp (ref "X2Y4")
      (value "AH49HSC")
      (fields (field (name "BOM_Supplier Part") "C510723"))
      (libsource (lib "") (part "AH49HSC_8"))
    )
    (comp (ref "X2Y5")
      (value "AH49HSC")
      (fields (field (name "BOM_Supplier Part") "C510723"))
      (libsource (lib "") (part "AH49HSC_8"))
    )
    (comp (ref "X2Y6")
      (value "AH49HSC")
      (fields (field (name "BOM_Supplier Part") "C510723"))
      (libsource (lib "") (part "AH49HSC_8"))
    )
    (comp (ref "X2Y7")
      (value "AH49HSC")
      (fields (field (name "BOM_Supplier Part") "C510723"))
      (libsource (lib "") (part "AH49HSC_8"))
    )
    (comp (ref "X2Y8")
      (value "AH49HSC")
      (fields (field (name "BOM_Supplier Part") "C510723"))
      (libsource (lib "") (part "AH49HSC_8"))
    )
    (comp (ref "X2Y9")
      (value "AH49HSC")
      (fields (field (name "BOM_Supplier Part") "C510723"))
      (libsource (lib "") (part "AH49HSC_8"))
    )
    (comp (ref "X2Y10")
      (value "AH49HSC")
      (fields (field (name "BOM_Supplier Part") "C510723"))
      (libsource (lib "") (part "AH49HSC_8"))
    )
    (comp (ref "X2Y11")
      (value "AH49HSC")
      (fields (field (name "BOM_Supplier Part") "C510723"))
      (libsource (lib "") (part "AH49HSC_8"))
    )
    (comp (ref "X2Y12")
      (value "AH49HSC")
      (fields (field (name "BOM_Supplier Part") "C510723"))
      (libsource (lib "") (part "AH49HSC_8"))
    )
    (comp (ref "X2Y13")
      (value "AH49HSC")
      (fields (field (name "BOM_Supplier Part") "C510723"))
      (libsource (lib "") (part "AH49HSC_8"))
    )
    (comp (ref "X2Y14")
      (value "AH49HSC")
      (fields (field (name "BOM_Supplier Part") "C510723"))
      (libsource (lib "") (part "AH49HSC_8"))
    )
    (comp (ref "X2Y15")
      (value "AH49HSC")
      (fields (field (name "BOM_Supplier Part") "C510723"))
      (libsource (lib "") (part "AH49HSC_8"))
    )
    (comp (ref "X2Y16")
      (value "AH49HSC")
      (fields (field (name "BOM_Supplier Part") "C510723"))
      (libsource (lib "") (part "AH49HSC_8"))
    )
    (comp (ref "X3Y1")
      (value "AH49HSC")
      (fields (field (name "BOM_Supplier Part") "C510723"))
      (libsource (lib "") (part "AH49HSC_3"))
    )
    (comp (ref "X3Y2")
      (value "AH49HSC")
      (fields (field (name "BOM_Supplier Part") "C510723"))
      (libsource (lib "") (part "AH49HSC_3"))
    )
    (comp (ref "X3Y3")
      (value "AH49HSC")
      (fields (field (name "BOM_Supplier Part") "C510723"))
      (libsource (lib "") (part "AH49HSC_3"))
    )
    (comp (ref "X3Y4")
      (value "AH49HSC")
      (fields (field (name "BOM_Supplier Part") "C510723"))
      (libsource (lib "") (part "AH49HSC_3"))
    )
    (comp (ref "X3Y5")
      (value "AH49HSC")
      (fields (field (name "BOM_Supplier Part") "C510723"))
      (libsource (lib "") (part "AH49HSC_3"))
    )
    (comp (ref "X3Y6")
      (value "AH49HSC")
      (fields (field (name "BOM_Supplier Part") "C510723"))
      (libsource (lib "") (part "AH49HSC_3"))
    )
    (comp (ref "X3Y7")
      (value "AH49HSC")
      (fields (field (name "BOM_Supplier Part") "C510723"))
      (libsource (lib "") (part "AH49HSC_3"))
    )
    (comp (ref "X3Y8")
      (value "AH49HSC")
      (fields (field (name "BOM_Supplier Part") "C510723"))
      (libsource (lib "") (part "AH49HSC_3"))
    )
    (comp (ref "X3Y9")
      (value "AH49HSC")
      (fields (field (name "BOM_Supplier Part") "C510723"))
      (libsource (lib "") (part "AH49HSC_3"))
    )
    (comp (ref "X3Y10")
      (value "AH49HSC")
      (fields (field (name "BOM_Supplier Part") "C510723"))
      (libsource (lib "") (part "AH49HSC_3"))
    )
    (comp (ref "X3Y11")
      (value "AH49HSC")
      (fields (field (name "BOM_Supplier Part") "C510723"))
      (libsource (lib "") (part "AH49HSC_3"))
    )
    (comp (ref "X3Y12")
      (value "AH49HSC")
      (fields (field (name "BOM_Supplier Part") "C510723"))
      (libsource (lib "") (part "AH49HSC_3"))
    )
    (comp (ref "X3Y13")
      (value "AH49HSC")
      (fields (field (name "BOM_Supplier Part") "C510723"))
      (libsource (lib "") (part "AH49HSC_3"))
    )
    (comp (ref "X3Y14")
      (value "AH49HSC")
      (fields (field (name "BOM_Supplier Part") "C510723"))
      (libsource (lib "") (part "AH49HSC_3"))
    )
    (comp (ref "X3Y15")
      (value "AH49HSC")
      (fields (field (name "BOM_Supplier Part") "C510723"))
      (libsource (lib "") (part "AH49HSC_3"))
    )
    (comp (ref "X3Y16")
      (value "AH49HSC")
      (fields (field (name "BOM_Supplier Part") "C510723"))
      (libsource (lib "") (part "AH49HSC_3"))
    )
    (comp (ref "X4Y1")
      (value "AH49HSC")
      (fields (field (name "BOM_Supplier Part") "C510723"))
      (libsource (lib "") (part "AH49HSC_7"))
    )
    (comp (ref "X4Y2")
      (value "AH49HSC")
      (fields (field (name "BOM_Supplier Part") "C510723"))
      (libsource (lib "") (part "AH49HSC_7"))
    )
    (comp (ref "X4Y3")
      (value "AH49HSC")
      (fields (field (name "BOM_Supplier Part") "C510723"))
      (libsource (lib "") (part "AH49HSC_7"))
    )
    (comp (ref "X4Y4")
      (value "AH49HSC")
      (fields (field (name "BOM_Supplier Part") "C510723"))
      (libsource (lib "") (part "AH49HSC_7"))
    )
    (comp (ref "X4Y5")
      (value "AH49HSC")
      (fields (field (name "BOM_Supplier Part") "C510723"))
      (libsource (lib "") (part "AH49HSC_7"))
    )
    (comp (ref "X4Y6")
      (value "AH49HSC")
      (fields (field (name "BOM_Supplier Part") "C510723"))
      (libsource (lib "") (part "AH49HSC_7"))
    )
    (comp (ref "X4Y7")
      (value "AH49HSC")
      (fields (field (name "BOM_Supplier Part") "C510723"))
      (libsource (lib "") (part "AH49HSC_7"))
    )
    (comp (ref "X4Y8")
      (value "AH49HSC")
      (fields (field (name "BOM_Supplier Part") "C510723"))
      (libsource (lib "") (part "AH49HSC_7"))
    )
    (comp (ref "X4Y9")
      (value "AH49HSC")
      (fields (field (name "BOM_Supplier Part") "C510723"))
      (libsource (lib "") (part "AH49HSC_7"))
    )
    (comp (ref "X4Y10")
      (value "AH49HSC")
      (fields (field (name "BOM_Supplier Part") "C510723"))
      (libsource (lib "") (part "AH49HSC_7"))
    )
    (comp (ref "X4Y11")
      (value "AH49HSC")
      (fields (field (name "BOM_Supplier Part") "C510723"))
      (libsource (lib "") (part "AH49HSC_7"))
    )
    (comp (ref "X4Y12")
      (value "AH49HSC")
      (fields (field (name "BOM_Supplier Part") "C510723"))
      (libsource (lib "") (part "AH49HSC_7"))
    )
    (comp (ref "X4Y13")
      (value "AH49HSC")
      (fields (field (name "BOM_Supplier Part") "C510723"))
      (libsource (lib "") (part "AH49HSC_7"))
    )
    (comp (ref "X4Y14")
      (value "AH49HSC")
      (fields (field (name "BOM_Supplier Part") "C510723"))
      (libsource (lib "") (part "AH49HSC_7"))
    )
    (comp (ref "X4Y15")
      (value "AH49HSC")
      (fields (field (name "BOM_Supplier Part") "C510723"))
      (libsource (lib "") (part "AH49HSC_7"))
    )
    (comp (ref "X4Y16")
      (value "AH49HSC")
      (fields (field (name "BOM_Supplier Part") "C510723"))
      (libsource (lib "") (part "AH49HSC_7"))
    )
    (comp (ref "X5Y1")
      (value "AH49HSC")
      (fields (field (name "BOM_Supplier Part") "C510723"))
      (libsource (lib "") (part "AH49HSC_4"))
    )
    (comp (ref "X5Y2")
      (value "AH49HSC")
      (fields (field (name "BOM_Supplier Part") "C510723"))
      (libsource (lib "") (part "AH49HSC_4"))
    )
    (comp (ref "X5Y3")
      (value "AH49HSC")
      (fields (field (name "BOM_Supplier Part") "C510723"))
      (libsource (lib "") (part "AH49HSC_4"))
    )
    (comp (ref "X5Y4")
      (value "AH49HSC")
      (fields (field (name "BOM_Supplier Part") "C510723"))
      (libsource (lib "") (part "AH49HSC_4"))
    )
    (comp (ref "X5Y5")
      (value "AH49HSC")
      (fields (field (name "BOM_Supplier Part") "C510723"))
      (libsource (lib "") (part "AH49HSC_4"))
    )
    (comp (ref "X5Y6")
      (value "AH49HSC")
      (fields (field (name "BOM_Supplier Part") "C510723"))
      (libsource (lib "") (part "AH49HSC_4"))
    )
    (comp (ref "X5Y7")
      (value "AH49HSC")
      (fields (field (name "BOM_Supplier Part") "C510723"))
      (libsource (lib "") (part "AH49HSC_4"))
    )
    (comp (ref "X5Y8")
      (value "AH49HSC")
      (fields (field (name "BOM_Supplier Part") "C510723"))
      (libsource (lib "") (part "AH49HSC_4"))
    )
    (comp (ref "X5Y9")
      (value "AH49HSC")
      (fields (field (name "BOM_Supplier Part") "C510723"))
      (libsource (lib "") (part "AH49HSC_4"))
    )
    (comp (ref "X5Y10")
      (value "AH49HSC")
      (fields (field (name "BOM_Supplier Part") "C510723"))
      (libsource (lib "") (part "AH49HSC_4"))
    )
    (comp (ref "X5Y11")
      (value "AH49HSC")
      (fields (field (name "BOM_Supplier Part") "C510723"))
      (libsource (lib "") (part "AH49HSC_4"))
    )
    (comp (ref "X5Y12")
      (value "AH49HSC")
      (fields (field (name "BOM_Supplier Part") "C510723"))
      (libsource (lib "") (part "AH49HSC_4"))
    )
    (comp (ref "X5Y13")
      (value "AH49HSC")
      (fields (field (name "BOM_Supplier Part") "C510723"))
      (libsource (lib "") (part "AH49HSC_4"))
    )
    (comp (ref "X5Y14")
      (value "AH49HSC")
      (fields (field (name "BOM_Supplier Part") "C510723"))
      (libsource (lib "") (part "AH49HSC_4"))
    )
    (comp (ref "X5Y15")
      (value "AH49HSC")
      (fields (field (name "BOM_Supplier Part") "C510723"))
      (libsource (lib "") (part "AH49HSC_4"))
    )
    (comp (ref "X5Y16")
      (value "AH49HSC")
      (fields (field (name "BOM_Supplier Part") "C510723"))
      (libsource (lib "") (part "AH49HSC_4"))
    )
    (comp (ref "X6Y1")
      (value "AH49HSC")
      (fields (field (name "BOM_Supplier Part") "C510723"))
      (libsource (lib "") (part "AH49HSC_9"))
    )
    (comp (ref "X6Y2")
      (value "AH49HSC")
      (fields (field (name "BOM_Supplier Part") "C510723"))
      (libsource (lib "") (part "AH49HSC_9"))
    )
    (comp (ref "X6Y3")
      (value "AH49HSC")
      (fields (field (name "BOM_Supplier Part") "C510723"))
      (libsource (lib "") (part "AH49HSC_9"))
    )
    (comp (ref "X6Y4")
      (value "AH49HSC")
      (fields (field (name "BOM_Supplier Part") "C510723"))
      (libsource (lib "") (part "AH49HSC_9"))
    )
    (comp (ref "X6Y5")
      (value "AH49HSC")
      (fields (field (name "BOM_Supplier Part") "C510723"))
      (libsource (lib "") (part "AH49HSC_9"))
    )
    (comp (ref "X6Y6")
      (value "AH49HSC")
      (fields (field (name "BOM_Supplier Part") "C510723"))
      (libsource (lib "") (part "AH49HSC_9"))
    )
    (comp (ref "X6Y7")
      (value "AH49HSC")
      (fields (field (name "BOM_Supplier Part") "C510723"))
      (libsource (lib "") (part "AH49HSC_9"))
    )
    (comp (ref "X6Y8")
      (value "AH49HSC")
      (fields (field (name "BOM_Supplier Part") "C510723"))
      (libsource (lib "") (part "AH49HSC_9"))
    )
    (comp (ref "X6Y9")
      (value "AH49HSC")
      (fields (field (name "BOM_Supplier Part") "C510723"))
      (libsource (lib "") (part "AH49HSC_9"))
    )
    (comp (ref "X6Y10")
      (value "AH49HSC")
      (fields (field (name "BOM_Supplier Part") "C510723"))
      (libsource (lib "") (part "AH49HSC_9"))
    )
    (comp (ref "X6Y11")
      (value "AH49HSC")
      (fields (field (name "BOM_Supplier Part") "C510723"))
      (libsource (lib "") (part "AH49HSC_9"))
    )
    (comp (ref "X6Y12")
      (value "AH49HSC")
      (fields (field (name "BOM_Supplier Part") "C510723"))
      (libsource (lib "") (part "AH49HSC_9"))
    )
    (comp (ref "X6Y13")
      (value "AH49HSC")
      (fields (field (name "BOM_Supplier Part") "C510723"))
      (libsource (lib "") (part "AH49HSC_9"))
    )
    (comp (ref "X6Y14")
      (value "AH49HSC")
      (fields (field (name "BOM_Supplier Part") "C510723"))
      (libsource (lib "") (part "AH49HSC_9"))
    )
    (comp (ref "X6Y15")
      (value "AH49HSC")
      (fields (field (name "BOM_Supplier Part") "C510723"))
      (libsource (lib "") (part "AH49HSC_9"))
    )
    (comp (ref "X6Y16")
      (value "AH49HSC")
      (fields (field (name "BOM_Supplier Part") "C510723"))
      (libsource (lib "") (part "AH49HSC_9"))
    )
    (comp (ref "X7Y1")
      (value "AH49HSC")
      (fields (field (name "BOM_Supplier Part") "C510723"))
      (libsource (lib "") (part "AH49HSC_14"))
    )
    (comp (ref "X7Y2")
      (value "AH49HSC")
      (fields (field (name "BOM_Supplier Part") "C510723"))
      (libsource (lib "") (part "AH49HSC_14"))
    )
    (comp (ref "X7Y3")
      (value "AH49HSC")
      (fields (field (name "BOM_Supplier Part") "C510723"))
      (libsource (lib "") (part "AH49HSC_14"))
    )
    (comp (ref "X7Y4")
      (value "AH49HSC")
      (fields (field (name "BOM_Supplier Part") "C510723"))
      (libsource (lib "") (part "AH49HSC_14"))
    )
    (comp (ref "X7Y5")
      (value "AH49HSC")
      (fields (field (name "BOM_Supplier Part") "C510723"))
      (libsource (lib "") (part "AH49HSC_14"))
    )
    (comp (ref "X7Y6")
      (value "AH49HSC")
      (fields (field (name "BOM_Supplier Part") "C510723"))
      (libsource (lib "") (part "AH49HSC_14"))
    )
    (comp (ref "X7Y7")
      (value "AH49HSC")
      (fields (field (name "BOM_Supplier Part") "C510723"))
      (libsource (lib "") (part "AH49HSC_14"))
    )
    (comp (ref "X7Y8")
      (value "AH49HSC")
      (fields (field (name "BOM_Supplier Part") "C510723"))
      (libsource (lib "") (part "AH49HSC_14"))
    )
    (comp (ref "X7Y9")
      (value "AH49HSC")
      (fields (field (name "BOM_Supplier Part") "C510723"))
      (libsource (lib "") (part "AH49HSC_14"))
    )
    (comp (ref "X7Y10")
      (value "AH49HSC")
      (fields (field (name "BOM_Supplier Part") "C510723"))
      (libsource (lib "") (part "AH49HSC_14"))
    )
    (comp (ref "X7Y11")
      (value "AH49HSC")
      (fields (field (name "BOM_Supplier Part") "C510723"))
      (libsource (lib "") (part "AH49HSC_14"))
    )
    (comp (ref "X7Y12")
      (value "AH49HSC")
      (fields (field (name "BOM_Supplier Part") "C510723"))
      (libsource (lib "") (part "AH49HSC_14"))
    )
    (comp (ref "X7Y13")
      (value "AH49HSC")
      (fields (field (name "BOM_Supplier Part") "C510723"))
      (libsource (lib "") (part "AH49HSC_14"))
    )
    (comp (ref "X7Y14")
      (value "AH49HSC")
      (fields (field (name "BOM_Supplier Part") "C510723"))
      (libsource (lib "") (part "AH49HSC_14"))
    )
    (comp (ref "X7Y15")
      (value "AH49HSC")
      (fields (field (name "BOM_Supplier Part") "C510723"))
      (libsource (lib "") (part "AH49HSC_14"))
    )
    (comp (ref "X7Y16")
      (value "AH49HSC")
      (fields (field (name "BOM_Supplier Part") "C510723"))
      (libsource (lib "") (part "AH49HSC_14"))
    )
    (comp (ref "X8Y1")
      (value "AH49HSC")
      (fields (field (name "BOM_Supplier Part") "C510723"))
      (libsource (lib "") (part "AH49HSC_10"))
    )
    (comp (ref "X8Y2")
      (value "AH49HSC")
      (fields (field (name "BOM_Supplier Part") "C510723"))
      (libsource (lib "") (part "AH49HSC_10"))
    )
    (comp (ref "X8Y3")
      (value "AH49HSC")
      (fields (field (name "BOM_Supplier Part") "C510723"))
      (libsource (lib "") (part "AH49HSC_10"))
    )
    (comp (ref "X8Y4")
      (value "AH49HSC")
      (fields (field (name "BOM_Supplier Part") "C510723"))
      (libsource (lib "") (part "AH49HSC_10"))
    )
    (comp (ref "X8Y5")
      (value "AH49HSC")
      (fields (field (name "BOM_Supplier Part") "C510723"))
      (libsource (lib "") (part "AH49HSC_10"))
    )
    (comp (ref "X8Y6")
      (value "AH49HSC")
      (fields (field (name "BOM_Supplier Part") "C510723"))
      (libsource (lib "") (part "AH49HSC_10"))
    )
    (comp (ref "X8Y7")
      (value "AH49HSC")
      (fields (field (name "BOM_Supplier Part") "C510723"))
      (libsource (lib "") (part "AH49HSC_10"))
    )
    (comp (ref "X8Y8")
      (value "AH49HSC")
      (fields (field (name "BOM_Supplier Part") "C510723"))
      (libsource (lib "") (part "AH49HSC_10"))
    )
    (comp (ref "X8Y9")
      (value "AH49HSC")
      (fields (field (name "BOM_Supplier Part") "C510723"))
      (libsource (lib "") (part "AH49HSC_10"))
    )
    (comp (ref "X8Y10")
      (value "AH49HSC")
      (fields (field (name "BOM_Supplier Part") "C510723"))
      (libsource (lib "") (part "AH49HSC_10"))
    )
    (comp (ref "X8Y11")
      (value "AH49HSC")
      (fields (field (name "BOM_Supplier Part") "C510723"))
      (libsource (lib "") (part "AH49HSC_10"))
    )
    (comp (ref "X8Y12")
      (value "AH49HSC")
      (fields (field (name "BOM_Supplier Part") "C510723"))
      (libsource (lib "") (part "AH49HSC_10"))
    )
    (comp (ref "X8Y13")
      (value "AH49HSC")
      (fields (field (name "BOM_Supplier Part") "C510723"))
      (libsource (lib "") (part "AH49HSC_10"))
    )
    (comp (ref "X8Y14")
      (value "AH49HSC")
      (fields (field (name "BOM_Supplier Part") "C510723"))
      (libsource (lib "") (part "AH49HSC_10"))
    )
    (comp (ref "X8Y15")
      (value "AH49HSC")
      (fields (field (name "BOM_Supplier Part") "C510723"))
      (libsource (lib "") (part "AH49HSC_10"))
    )
    (comp (ref "X8Y16")
      (value "AH49HSC")
      (fields (field (name "BOM_Supplier Part") "C510723"))
      (libsource (lib "") (part "AH49HSC_10"))
    )
    (comp (ref "X9Y1")
      (value "AH49HSC")
      (fields (field (name "BOM_Supplier Part") "C510723"))
      (libsource (lib "") (part "AH49HSC_6"))
    )
    (comp (ref "X9Y2")
      (value "AH49HSC")
      (fields (field (name "BOM_Supplier Part") "C510723"))
      (libsource (lib "") (part "AH49HSC_6"))
    )
    (comp (ref "X9Y3")
      (value "AH49HSC")
      (fields (field (name "BOM_Supplier Part") "C510723"))
      (libsource (lib "") (part "AH49HSC_6"))
    )
    (comp (ref "X9Y4")
      (value "AH49HSC")
      (fields (field (name "BOM_Supplier Part") "C510723"))
      (libsource (lib "") (part "AH49HSC_6"))
    )
    (comp (ref "X9Y5")
      (value "AH49HSC")
      (fields (field (name "BOM_Supplier Part") "C510723"))
      (libsource (lib "") (part "AH49HSC_6"))
    )
    (comp (ref "X9Y6")
      (value "AH49HSC")
      (fields (field (name "BOM_Supplier Part") "C510723"))
      (libsource (lib "") (part "AH49HSC_6"))
    )
    (comp (ref "X9Y7")
      (value "AH49HSC")
      (fields (field (name "BOM_Supplier Part") "C510723"))
      (libsource (lib "") (part "AH49HSC_6"))
    )
    (comp (ref "X9Y8")
      (value "AH49HSC")
      (fields (field (name "BOM_Supplier Part") "C510723"))
      (libsource (lib "") (part "AH49HSC_6"))
    )
    (comp (ref "X9Y9")
      (value "AH49HSC")
      (fields (field (name "BOM_Supplier Part") "C510723"))
      (libsource (lib "") (part "AH49HSC_6"))
    )
    (comp (ref "X9Y10")
      (value "AH49HSC")
      (fields (field (name "BOM_Supplier Part") "C510723"))
      (libsource (lib "") (part "AH49HSC_6"))
    )
    (comp (ref "X9Y11")
      (value "AH49HSC")
      (fields (field (name "BOM_Supplier Part") "C510723"))
      (libsource (lib "") (part "AH49HSC_6"))
    )
    (comp (ref "X9Y12")
      (value "AH49HSC")
      (fields (field (name "BOM_Supplier Part") "C510723"))
      (libsource (lib "") (part "AH49HSC_6"))
    )
    (comp (ref "X9Y13")
      (value "AH49HSC")
      (fields (field (name "BOM_Supplier Part") "C510723"))
      (libsource (lib "") (part "AH49HSC_6"))
    )
    (comp (ref "X9Y14")
      (value "AH49HSC")
      (fields (field (name "BOM_Supplier Part") "C510723"))
      (libsource (lib "") (part "AH49HSC_6"))
    )
    (comp (ref "X9Y15")
      (value "AH49HSC")
      (fields (field (name "BOM_Supplier Part") "C510723"))
      (libsource (lib "") (part "AH49HSC_6"))
    )
    (comp (ref "X9Y16")
      (value "AH49HSC")
      (fields (field (name "BOM_Supplier Part") "C510723"))
      (libsource (lib "") (part "AH49HSC_6"))
    )
    (comp (ref "X10Y1")
      (value "AH49HSC")
      (fields (field (name "BOM_Supplier Part") "C510723"))
      (libsource (lib "") (part "AH49HSC_2"))
    )
    (comp (ref "X10Y2")
      (value "AH49HSC")
      (fields (field (name "BOM_Supplier Part") "C510723"))
      (libsource (lib "") (part "AH49HSC_2"))
    )
    (comp (ref "X10Y3")
      (value "AH49HSC")
      (fields (field (name "BOM_Supplier Part") "C510723"))
      (libsource (lib "") (part "AH49HSC_2"))
    )
    (comp (ref "X10Y4")
      (value "AH49HSC")
      (fields (field (name "BOM_Supplier Part") "C510723"))
      (libsource (lib "") (part "AH49HSC_2"))
    )
    (comp (ref "X10Y5")
      (value "AH49HSC")
      (fields (field (name "BOM_Supplier Part") "C510723"))
      (libsource (lib "") (part "AH49HSC_2"))
    )
    (comp (ref "X10Y6")
      (value "AH49HSC")
      (fields (field (name "BOM_Supplier Part") "C510723"))
      (libsource (lib "") (part "AH49HSC_2"))
    )
    (comp (ref "X10Y7")
      (value "AH49HSC")
      (fields (field (name "BOM_Supplier Part") "C510723"))
      (libsource (lib "") (part "AH49HSC_2"))
    )
    (comp (ref "X10Y8")
      (value "AH49HSC")
      (fields (field (name "BOM_Supplier Part") "C510723"))
      (libsource (lib "") (part "AH49HSC_2"))
    )
    (comp (ref "X10Y9")
      (value "AH49HSC")
      (fields (field (name "BOM_Supplier Part") "C510723"))
      (libsource (lib "") (part "AH49HSC_2"))
    )
    (comp (ref "X10Y10")
      (value "AH49HSC")
      (fields (field (name "BOM_Supplier Part") "C510723"))
      (libsource (lib "") (part "AH49HSC_2"))
    )
    (comp (ref "X10Y11")
      (value "AH49HSC")
      (fields (field (name "BOM_Supplier Part") "C510723"))
      (libsource (lib "") (part "AH49HSC_2"))
    )
    (comp (ref "X10Y12")
      (value "AH49HSC")
      (fields (field (name "BOM_Supplier Part") "C510723"))
      (libsource (lib "") (part "AH49HSC_2"))
    )
    (comp (ref "X10Y13")
      (value "AH49HSC")
      (fields (field (name "BOM_Supplier Part") "C510723"))
      (libsource (lib "") (part "AH49HSC_2"))
    )
    (comp (ref "X10Y14")
      (value "AH49HSC")
      (fields (field (name "BOM_Supplier Part") "C510723"))
      (libsource (lib "") (part "AH49HSC_2"))
    )
    (comp (ref "X10Y15")
      (value "AH49HSC")
      (fields (field (name "BOM_Supplier Part") "C510723"))
      (libsource (lib "") (part "AH49HSC_2"))
    )
    (comp (ref "X10Y16")
      (value "AH49HSC")
      (fields (field (name "BOM_Supplier Part") "C510723"))
      (libsource (lib "") (part "AH49HSC_2"))
    )
    (comp (ref "X11Y1")
      (value "AH49HSC")
      (fields (field (name "BOM_Supplier Part") "C510723"))
      (libsource (lib "") (part "AH49HSC_12"))
    )
    (comp (ref "X11Y2")
      (value "AH49HSC")
      (fields (field (name "BOM_Supplier Part") "C510723"))
      (libsource (lib "") (part "AH49HSC_12"))
    )
    (comp (ref "X11Y3")
      (value "AH49HSC")
      (fields (field (name "BOM_Supplier Part") "C510723"))
      (libsource (lib "") (part "AH49HSC_12"))
    )
    (comp (ref "X11Y4")
      (value "AH49HSC")
      (fields (field (name "BOM_Supplier Part") "C510723"))
      (libsource (lib "") (part "AH49HSC_12"))
    )
    (comp (ref "X11Y5")
      (value "AH49HSC")
      (fields (field (name "BOM_Supplier Part") "C510723"))
      (libsource (lib "") (part "AH49HSC_12"))
    )
    (comp (ref "X11Y6")
      (value "AH49HSC")
      (fields (field (name "BOM_Supplier Part") "C510723"))
      (libsource (lib "") (part "AH49HSC_12"))
    )
    (comp (ref "X11Y7")
      (value "AH49HSC")
      (fields (field (name "BOM_Supplier Part") "C510723"))
      (libsource (lib "") (part "AH49HSC_12"))
    )
    (comp (ref "X11Y8")
      (value "AH49HSC")
      (fields (field (name "BOM_Supplier Part") "C510723"))
      (libsource (lib "") (part "AH49HSC_12"))
    )
    (comp (ref "X11Y9")
      (value "AH49HSC")
      (fields (field (name "BOM_Supplier Part") "C510723"))
      (libsource (lib "") (part "AH49HSC_12"))
    )
    (comp (ref "X11Y10")
      (value "AH49HSC")
      (fields (field (name "BOM_Supplier Part") "C510723"))
      (libsource (lib "") (part "AH49HSC_12"))
    )
    (comp (ref "X11Y11")
      (value "AH49HSC")
      (fields (field (name "BOM_Supplier Part") "C510723"))
      (libsource (lib "") (part "AH49HSC_12"))
    )
    (comp (ref "X11Y12")
      (value "AH49HSC")
      (fields (field (name "BOM_Supplier Part") "C510723"))
      (libsource (lib "") (part "AH49HSC_12"))
    )
    (comp (ref "X11Y13")
      (value "AH49HSC")
      (fields (field (name "BOM_Supplier Part") "C510723"))
      (libsource (lib "") (part "AH49HSC_12"))
    )
    (comp (ref "X11Y14")
      (value "AH49HSC")
      (fields (field (name "BOM_Supplier Part") "C510723"))
      (libsource (lib "") (part "AH49HSC_12"))
    )
    (comp (ref "X11Y15")
      (value "AH49HSC")
      (fields (field (name "BOM_Supplier Part") "C510723"))
      (libsource (lib "") (part "AH49HSC_12"))
    )
    (comp (ref "X11Y16")
      (value "AH49HSC")
      (fields (field (name "BOM_Supplier Part") "C510723"))
      (libsource (lib "") (part "AH49HSC_12"))
    )
    (comp (ref "X12Y1")
      (value "AH49HSC")
      (fields (field (name "BOM_Supplier Part") "C510723"))
      (libsource (lib "") (part "AH49HSC"))
    )
    (comp (ref "X12Y2")
      (value "AH49HSC")
      (fields (field (name "BOM_Supplier Part") "C510723"))
      (libsource (lib "") (part "AH49HSC"))
    )
    (comp (ref "X12Y3")
      (value "AH49HSC")
      (fields (field (name "BOM_Supplier Part") "C510723"))
      (libsource (lib "") (part "AH49HSC"))
    )
    (comp (ref "X12Y4")
      (value "AH49HSC")
      (fields (field (name "BOM_Supplier Part") "C510723"))
      (libsource (lib "") (part "AH49HSC"))
    )
    (comp (ref "X12Y5")
      (value "AH49HSC")
      (fields (field (name "BOM_Supplier Part") "C510723"))
      (libsource (lib "") (part "AH49HSC"))
    )
    (comp (ref "X12Y6")
      (value "AH49HSC")
      (fields (field (name "BOM_Supplier Part") "C510723"))
      (libsource (lib "") (part "AH49HSC"))
    )
    (comp (ref "X12Y7")
      (value "AH49HSC")
      (fields (field (name "BOM_Supplier Part") "C510723"))
      (libsource (lib "") (part "AH49HSC"))
    )
    (comp (ref "X12Y8")
      (value "AH49HSC")
      (fields (field (name "BOM_Supplier Part") "C510723"))
      (libsource (lib "") (part "AH49HSC"))
    )
    (comp (ref "X12Y9")
      (value "AH49HSC")
      (fields (field (name "BOM_Supplier Part") "C510723"))
      (libsource (lib "") (part "AH49HSC"))
    )
    (comp (ref "X12Y10")
      (value "AH49HSC")
      (fields (field (name "BOM_Supplier Part") "C510723"))
      (libsource (lib "") (part "AH49HSC"))
    )
    (comp (ref "X12Y11")
      (value "AH49HSC")
      (fields (field (name "BOM_Supplier Part") "C510723"))
      (libsource (lib "") (part "AH49HSC"))
    )
    (comp (ref "X12Y12")
      (value "AH49HSC")
      (fields (field (name "BOM_Supplier Part") "C510723"))
      (libsource (lib "") (part "AH49HSC"))
    )
    (comp (ref "X12Y13")
      (value "AH49HSC")
      (fields (field (name "BOM_Supplier Part") "C510723"))
      (libsource (lib "") (part "AH49HSC"))
    )
    (comp (ref "X12Y14")
      (value "AH49HSC")
      (fields (field (name "BOM_Supplier Part") "C510723"))
      (libsource (lib "") (part "AH49HSC"))
    )
    (comp (ref "X12Y15")
      (value "AH49HSC")
      (fields (field (name "BOM_Supplier Part") "C510723"))
      (libsource (lib "") (part "AH49HSC"))
    )
    (comp (ref "X12Y16")
      (value "AH49HSC")
      (fields (field (name "BOM_Supplier Part") "C510723"))
      (libsource (lib "") (part "AH49HSC"))
    )
    (comp (ref "X13Y1")
      (value "AH49HSC")
      (fields (field (name "BOM_Supplier Part") "C510723"))
      (libsource (lib "") (part "AH49HSC_15"))
    )
    (comp (ref "X13Y2")
      (value "AH49HSC")
      (fields (field (name "BOM_Supplier Part") "C510723"))
      (libsource (lib "") (part "AH49HSC_15"))
    )
    (comp (ref "X13Y3")
      (value "AH49HSC")
      (fields (field (name "BOM_Supplier Part") "C510723"))
      (libsource (lib "") (part "AH49HSC_15"))
    )
    (comp (ref "X13Y4")
      (value "AH49HSC")
      (fields (field (name "BOM_Supplier Part") "C510723"))
      (libsource (lib "") (part "AH49HSC_15"))
    )
    (comp (ref "X13Y5")
      (value "AH49HSC")
      (fields (field (name "BOM_Supplier Part") "C510723"))
      (libsource (lib "") (part "AH49HSC_15"))
    )
    (comp (ref "X13Y6")
      (value "AH49HSC")
      (fields (field (name "BOM_Supplier Part") "C510723"))
      (libsource (lib "") (part "AH49HSC_15"))
    )
    (comp (ref "X13Y7")
      (value "AH49HSC")
      (fields (field (name "BOM_Supplier Part") "C510723"))
      (libsource (lib "") (part "AH49HSC_15"))
    )
    (comp (ref "X13Y8")
      (value "AH49HSC")
      (fields (field (name "BOM_Supplier Part") "C510723"))
      (libsource (lib "") (part "AH49HSC_15"))
    )
    (comp (ref "X13Y9")
      (value "AH49HSC")
      (fields (field (name "BOM_Supplier Part") "C510723"))
      (libsource (lib "") (part "AH49HSC_15"))
    )
    (comp (ref "X13Y10")
      (value "AH49HSC")
      (fields (field (name "BOM_Supplier Part") "C510723"))
      (libsource (lib "") (part "AH49HSC_15"))
    )
    (comp (ref "X13Y11")
      (value "AH49HSC")
      (fields (field (name "BOM_Supplier Part") "C510723"))
      (libsource (lib "") (part "AH49HSC_15"))
    )
    (comp (ref "X13Y12")
      (value "AH49HSC")
      (fields (field (name "BOM_Supplier Part") "C510723"))
      (libsource (lib "") (part "AH49HSC_15"))
    )
    (comp (ref "X13Y13")
      (value "AH49HSC")
      (fields (field (name "BOM_Supplier Part") "C510723"))
      (libsource (lib "") (part "AH49HSC_15"))
    )
    (comp (ref "X13Y14")
      (value "AH49HSC")
      (fields (field (name "BOM_Supplier Part") "C510723"))
      (libsource (lib "") (part "AH49HSC_15"))
    )
    (comp (ref "X13Y15")
      (value "AH49HSC")
      (fields (field (name "BOM_Supplier Part") "C510723"))
      (libsource (lib "") (part "AH49HSC_15"))
    )
    (comp (ref "X13Y16")
      (value "AH49HSC")
      (fields (field (name "BOM_Supplier Part") "C510723"))
      (libsource (lib "") (part "AH49HSC_15"))
    )
    (comp (ref "X14Y1")
      (value "AH49HSC")
      (fields (field (name "BOM_Supplier Part") "C510723"))
      (libsource (lib "") (part "AH49HSC_5"))
    )
    (comp (ref "X14Y2")
      (value "AH49HSC")
      (fields (field (name "BOM_Supplier Part") "C510723"))
      (libsource (lib "") (part "AH49HSC_5"))
    )
    (comp (ref "X14Y3")
      (value "AH49HSC")
      (fields (field (name "BOM_Supplier Part") "C510723"))
      (libsource (lib "") (part "AH49HSC_5"))
    )
    (comp (ref "X14Y4")
      (value "AH49HSC")
      (fields (field (name "BOM_Supplier Part") "C510723"))
      (libsource (lib "") (part "AH49HSC_5"))
    )
    (comp (ref "X14Y5")
      (value "AH49HSC")
      (fields (field (name "BOM_Supplier Part") "C510723"))
      (libsource (lib "") (part "AH49HSC_5"))
    )
    (comp (ref "X14Y6")
      (value "AH49HSC")
      (fields (field (name "BOM_Supplier Part") "C510723"))
      (libsource (lib "") (part "AH49HSC_5"))
    )
    (comp (ref "X14Y7")
      (value "AH49HSC")
      (fields (field (name "BOM_Supplier Part") "C510723"))
      (libsource (lib "") (part "AH49HSC_5"))
    )
    (comp (ref "X14Y8")
      (value "AH49HSC")
      (fields (field (name "BOM_Supplier Part") "C510723"))
      (libsource (lib "") (part "AH49HSC_5"))
    )
    (comp (ref "X14Y9")
      (value "AH49HSC")
      (fields (field (name "BOM_Supplier Part") "C510723"))
      (libsource (lib "") (part "AH49HSC_5"))
    )
    (comp (ref "X14Y10")
      (value "AH49HSC")
      (fields (field (name "BOM_Supplier Part") "C510723"))
      (libsource (lib "") (part "AH49HSC_5"))
    )
    (comp (ref "X14Y11")
      (value "AH49HSC")
      (fields (field (name "BOM_Supplier Part") "C510723"))
      (libsource (lib "") (part "AH49HSC_5"))
    )
    (comp (ref "X14Y12")
      (value "AH49HSC")
      (fields (field (name "BOM_Supplier Part") "C510723"))
      (libsource (lib "") (part "AH49HSC_5"))
    )
    (comp (ref "X14Y13")
      (value "AH49HSC")
      (fields (field (name "BOM_Supplier Part") "C510723"))
      (libsource (lib "") (part "AH49HSC_5"))
    )
    (comp (ref "X14Y14")
      (value "AH49HSC")
      (fields (field (name "BOM_Supplier Part") "C510723"))
      (libsource (lib "") (part "AH49HSC_5"))
    )
    (comp (ref "X14Y15")
      (value "AH49HSC")
      (fields (field (name "BOM_Supplier Part") "C510723"))
      (libsource (lib "") (part "AH49HSC_5"))
    )
    (comp (ref "X14Y16")
      (value "AH49HSC")
      (fields (field (name "BOM_Supplier Part") "C510723"))
      (libsource (lib "") (part "AH49HSC_5"))
    )
    (comp (ref "X15Y1")
      (value "AH49HSC")
      (fields (field (name "BOM_Supplier Part") "C510723"))
      (libsource (lib "") (part "AH49HSC_1"))
    )
    (comp (ref "X15Y2")
      (value "AH49HSC")
      (fields (field (name "BOM_Supplier Part") "C510723"))
      (libsource (lib "") (part "AH49HSC_1"))
    )
    (comp (ref "X15Y3")
      (value "AH49HSC")
      (fields (field (name "BOM_Supplier Part") "C510723"))
      (libsource (lib "") (part "AH49HSC_1"))
    )
    (comp (ref "X15Y4")
      (value "AH49HSC")
      (fields (field (name "BOM_Supplier Part") "C510723"))
      (libsource (lib "") (part "AH49HSC_1"))
    )
    (comp (ref "X15Y5")
      (value "AH49HSC")
      (fields (field (name "BOM_Supplier Part") "C510723"))
      (libsource (lib "") (part "AH49HSC_1"))
    )
    (comp (ref "X15Y6")
      (value "AH49HSC")
      (fields (field (name "BOM_Supplier Part") "C510723"))
      (libsource (lib "") (part "AH49HSC_1"))
    )
    (comp (ref "X15Y7")
      (value "AH49HSC")
      (fields (field (name "BOM_Supplier Part") "C510723"))
      (libsource (lib "") (part "AH49HSC_1"))
    )
    (comp (ref "X15Y8")
      (value "AH49HSC")
      (fields (field (name "BOM_Supplier Part") "C510723"))
      (libsource (lib "") (part "AH49HSC_1"))
    )
    (comp (ref "X15Y9")
      (value "AH49HSC")
      (fields (field (name "BOM_Supplier Part") "C510723"))
      (libsource (lib "") (part "AH49HSC_1"))
    )
    (comp (ref "X15Y10")
      (value "AH49HSC")
      (fields (field (name "BOM_Supplier Part") "C510723"))
      (libsource (lib "") (part "AH49HSC_1"))
    )
    (comp (ref "X15Y11")
      (value "AH49HSC")
      (fields (field (name "BOM_Supplier Part") "C510723"))
      (libsource (lib "") (part "AH49HSC_1"))
    )
    (comp (ref "X15Y12")
      (value "AH49HSC")
      (fields (field (name "BOM_Supplier Part") "C510723"))
      (libsource (lib "") (part "AH49HSC_1"))
    )
    (comp (ref "X15Y13")
      (value "AH49HSC")
      (fields (field (name "BOM_Supplier Part") "C510723"))
      (libsource (lib "") (part "AH49HSC_1"))
    )
    (comp (ref "X15Y14")
      (value "AH49HSC")
      (fields (field (name "BOM_Supplier Part") "C510723"))
      (libsource (lib "") (part "AH49HSC_1"))
    )
    (comp (ref "X15Y15")
      (value "AH49HSC")
      (fields (field (name "BOM_Supplier Part") "C510723"))
      (libsource (lib "") (part "AH49HSC_1"))
    )
    (comp (ref "X15Y16")
      (value "AH49HSC")
      (fields (field (name "BOM_Supplier Part") "C510723"))
      (libsource (lib "") (part "AH49HSC_1"))
    )
    (comp (ref "X16Y1")
      (value "AH49HSC")
      (fields (field (name "BOM_Supplier Part") "C510723"))
      (libsource (lib "") (part "AH49HSC_13"))
    )
    (comp (ref "X16Y2")
      (value "AH49HSC")
      (fields (field (name "BOM_Supplier Part") "C510723"))
      (libsource (lib "") (part "AH49HSC_13"))
    )
    (comp (ref "X16Y3")
      (value "AH49HSC")
      (fields (field (name "BOM_Supplier Part") "C510723"))
      (libsource (lib "") (part "AH49HSC_13"))
    )
    (comp (ref "X16Y4")
      (value "AH49HSC")
      (fields (field (name "BOM_Supplier Part") "C510723"))
      (libsource (lib "") (part "AH49HSC_13"))
    )
    (comp (ref "X16Y5")
      (value "AH49HSC")
      (fields (field (name "BOM_Supplier Part") "C510723"))
      (libsource (lib "") (part "AH49HSC_13"))
    )
    (comp (ref "X16Y6")
      (value "AH49HSC")
      (fields (field (name "BOM_Supplier Part") "C510723"))
      (libsource (lib "") (part "AH49HSC_13"))
    )
    (comp (ref "X16Y7")
      (value "AH49HSC")
      (fields (field (name "BOM_Supplier Part") "C510723"))
      (libsource (lib "") (part "AH49HSC_13"))
    )
    (comp (ref "X16Y8")
      (value "AH49HSC")
      (fields (field (name "BOM_Supplier Part") "C510723"))
      (libsource (lib "") (part "AH49HSC_13"))
    )
    (comp (ref "X16Y9")
      (value "AH49HSC")
      (fields (field (name "BOM_Supplier Part") "C510723"))
      (libsource (lib "") (part "AH49HSC_13"))
    )
    (comp (ref "X16Y10")
      (value "AH49HSC")
      (fields (field (name "BOM_Supplier Part") "C510723"))
      (libsource (lib "") (part "AH49HSC_13"))
    )
    (comp (ref "X16Y11")
      (value "AH49HSC")
      (fields (field (name "BOM_Supplier Part") "C510723"))
      (libsource (lib "") (part "AH49HSC_13"))
    )
    (comp (ref "X16Y12")
      (value "AH49HSC")
      (fields (field (name "BOM_Supplier Part") "C510723"))
      (libsource (lib "") (part "AH49HSC_13"))
    )
    (comp (ref "X16Y13")
      (value "AH49HSC")
      (fields (field (name "BOM_Supplier Part") "C510723"))
      (libsource (lib "") (part "AH49HSC_13"))
    )
    (comp (ref "X16Y14")
      (value "AH49HSC")
      (fields (field (name "BOM_Supplier Part") "C510723"))
      (libsource (lib "") (part "AH49HSC_13"))
    )
    (comp (ref "X16Y15")
      (value "AH49HSC")
      (fields (field (name "BOM_Supplier Part") "C510723"))
      (libsource (lib "") (part "AH49HSC_13"))
    )
    (comp (ref "X16Y16")
      (value "AH49HSC")
      (fields (field (name "BOM_Supplier Part") "C510723"))
      (libsource (lib "") (part "AH49HSC_13"))
    )
  )
  (nets
    (net (code "1") (name "+3.3V") (class "Default")
      (node (ref "C1") (pin "2") (pinfunction "2_2") (pintype "unspecified"))
      (node (ref "C101") (pin "2") (pinfunction "2_2") (pintype "unspecified"))
      (node (ref "C104") (pin "2") (pinfunction "2_2") (pintype "unspecified"))
      (node (ref "C105") (pin "2") (pinfunction "2_2") (pintype "unspecified"))
      (node (ref "C107") (pin "2") (pinfunction "2_2") (pintype "unspecified"))
      (node (ref "C109") (pin "2") (pinfunction "2_2") (pintype "unspecified"))
      (node (ref "C11") (pin "2") (pinfunction "2_2") (pintype "unspecified"))
      (node (ref "C111") (pin "2") (pinfunction "2_2") (pintype "unspecified"))
      (node (ref "C113") (pin "2") (pinfunction "2_2") (pintype "unspecified"))
      (node (ref "C115") (pin "2") (pinfunction "2_2") (pintype "unspecified"))
      (node (ref "C117") (pin "2") (pinfunction "2_2") (pintype "unspecified"))
      (node (ref "C119") (pin "2") (pinfunction "2_2") (pintype "unspecified"))
      (node (ref "C121") (pin "2") (pinfunction "2_2") (pintype "unspecified"))
      (node (ref "C123") (pin "2") (pinfunction "2_2") (pintype "unspecified"))
      (node (ref "C125") (pin "2") (pinfunction "2_2") (pintype "unspecified"))
      (node (ref "C127") (pin "2") (pinfunction "2_2") (pintype "unspecified"))
      (node (ref "C129") (pin "2") (pinfunction "2_2") (pintype "unspecified"))
      (node (ref "C13") (pin "2") (pinfunction "2_2") (pintype "unspecified"))
      (node (ref "C132") (pin "2") (pinfunction "2_2") (pintype "unspecified"))
      (node (ref "C134") (pin "2") (pinfunction "2_2") (pintype "unspecified"))
      (node (ref "C136") (pin "2") (pinfunction "2_2") (pintype "unspecified"))
      (node (ref "C138") (pin "2") (pinfunction "2_2") (pintype "unspecified"))
      (node (ref "C140") (pin "2") (pinfunction "2_2") (pintype "unspecified"))
      (node (ref "C142") (pin "2") (pinfunction "2_2") (pintype "unspecified"))
      (node (ref "C144") (pin "2") (pinfunction "2_2") (pintype "unspecified"))
      (node (ref "C146") (pin "2") (pinfunction "2_2") (pintype "unspecified"))
      (node (ref "C148") (pin "2") (pinfunction "2_2") (pintype "unspecified"))
      (node (ref "C15") (pin "2") (pinfunction "2_2") (pintype "unspecified"))
      (node (ref "C150") (pin "2") (pinfunction "2_2") (pintype "unspecified"))
      (node (ref "C152") (pin "2") (pinfunction "2_2") (pintype "unspecified"))
      (node (ref "C154") (pin "2") (pinfunction "2_2") (pintype "unspecified"))
      (node (ref "C156") (pin "2") (pinfunction "2_2") (pintype "unspecified"))
      (node (ref "C158") (pin "2") (pinfunction "2_2") (pintype "unspecified"))
      (node (ref "C160") (pin "2") (pinfunction "2_2") (pintype "unspecified"))
      (node (ref "C162") (pin "2") (pinfunction "2_2") (pintype "unspecified"))
      (node (ref "C164") (pin "2") (pinfunction "2_2") (pintype "unspecified"))
      (node (ref "C166") (pin "2") (pinfunction "2_2") (pintype "unspecified"))
      (node (ref "C168") (pin "2") (pinfunction "2_2") (pintype "unspecified"))
      (node (ref "C17") (pin "2") (pinfunction "2_2") (pintype "unspecified"))
      (node (ref "C170") (pin "2") (pinfunction "2_2") (pintype "unspecified"))
      (node (ref "C172") (pin "2") (pinfunction "2_2") (pintype "unspecified"))
      (node (ref "C174") (pin "2") (pinfunction "2_2") (pintype "unspecified"))
      (node (ref "C176") (pin "2") (pinfunction "2_2") (pintype "unspecified"))
      (node (ref "C178") (pin "2") (pinfunction "2_2") (pintype "unspecified"))
      (node (ref "C180") (pin "2") (pinfunction "2_2") (pintype "unspecified"))
      (node (ref "C182") (pin "2") (pinfunction "2_2") (pintype "unspecified"))
      (node (ref "C184") (pin "2") (pinfunction "2_2") (pintype "unspecified"))
      (node (ref "C186") (pin "2") (pinfunction "2_2") (pintype "unspecified"))
      (node (ref "C188") (pin "2") (pinfunction "2_2") (pintype "unspecified"))
      (node (ref "C19") (pin "2") (pinfunction "2_2") (pintype "unspecified"))
      (node (ref "C190") (pin "2") (pinfunction "2_2") (pintype "unspecified"))
      (node (ref "C192") (pin "2") (pinfunction "2_2") (pintype "unspecified"))
      (node (ref "C194") (pin "2") (pinfunction "2_2") (pintype "unspecified"))
      (node (ref "C195") (pin "2") (pinfunction "2_2") (pintype "unspecified"))
      (node (ref "C197") (pin "2") (pinfunction "2_2") (pintype "unspecified"))
      (node (ref "C199") (pin "2") (pinfunction "2_2") (pintype "unspecified"))
      (node (ref "C201") (pin "2") (pinfunction "2_2") (pintype "unspecified"))
      (node (ref "C203") (pin "2") (pinfunction "2_2") (pintype "unspecified"))
      (node (ref "C205") (pin "2") (pinfunction "2_2") (pintype "unspecified"))
      (node (ref "C207") (pin "2") (pinfunction "2_2") (pintype "unspecified"))
      (node (ref "C209") (pin "2") (pinfunction "2_2") (pintype "unspecified"))
      (node (ref "C21") (pin "2") (pinfunction "2_2") (pintype "unspecified"))
      (node (ref "C211") (pin "2") (pinfunction "2_2") (pintype "unspecified"))
      (node (ref "C213") (pin "2") (pinfunction "2_2") (pintype "unspecified"))
      (node (ref "C215") (pin "2") (pinfunction "2_2") (pintype "unspecified"))
      (node (ref "C217") (pin "2") (pinfunction "2_2") (pintype "unspecified"))
      (node (ref "C219") (pin "2") (pinfunction "2_2") (pintype "unspecified"))
      (node (ref "C221") (pin "2") (pinfunction "2_2") (pintype "unspecified"))
      (node (ref "C223") (pin "2") (pinfunction "2_2") (pintype "unspecified"))
      (node (ref "C225") (pin "2") (pinfunction "2_2") (pintype "unspecified"))
      (node (ref "C228") (pin "2") (pinfunction "2_2") (pintype "unspecified"))
      (node (ref "C23") (pin "2") (pinfunction "2_2") (pintype "unspecified"))
      (node (ref "C230") (pin "2") (pinfunction "2_2") (pintype "unspecified"))
      (node (ref "C232") (pin "2") (pinfunction "2_2") (pintype "unspecified"))
      (node (ref "C234") (pin "2") (pinfunction "2_2") (pintype "unspecified"))
      (node (ref "C236") (pin "2") (pinfunction "2_2") (pintype "unspecified"))
      (node (ref "C238") (pin "2") (pinfunction "2_2") (pintype "unspecified"))
      (node (ref "C240") (pin "2") (pinfunction "2_2") (pintype "unspecified"))
      (node (ref "C242") (pin "2") (pinfunction "2_2") (pintype "unspecified"))
      (node (ref "C244") (pin "2") (pinfunction "2_2") (pintype "unspecified"))
      (node (ref "C246") (pin "2") (pinfunction "2_2") (pintype "unspecified"))
      (node (ref "C248") (pin "2") (pinfunction "2_2") (pintype "unspecified"))
      (node (ref "C25") (pin "2") (pinfunction "2_2") (pintype "unspecified"))
      (node (ref "C250") (pin "2") (pinfunction "2_2") (pintype "unspecified"))
      (node (ref "C252") (pin "2") (pinfunction "2_2") (pintype "unspecified"))
      (node (ref "C254") (pin "2") (pinfunction "2_2") (pintype "unspecified"))
      (node (ref "C256") (pin "2") (pinfunction "2_2") (pintype "unspecified"))
      (node (ref "C258") (pin "2") (pinfunction "2_2") (pintype "unspecified"))
      (node (ref "C259") (pin "2") (pinfunction "2_2") (pintype "unspecified"))
      (node (ref "C261") (pin "2") (pinfunction "2_2") (pintype "unspecified"))
      (node (ref "C263") (pin "2") (pinfunction "2_2") (pintype "unspecified"))
      (node (ref "C265") (pin "2") (pinfunction "2_2") (pintype "unspecified"))
      (node (ref "C267") (pin "2") (pinfunction "2_2") (pintype "unspecified"))
      (node (ref "C269") (pin "2") (pinfunction "2_2") (pintype "unspecified"))
      (node (ref "C27") (pin "2") (pinfunction "2_2") (pintype "unspecified"))
      (node (ref "C271") (pin "2") (pinfunction "2_2") (pintype "unspecified"))
      (node (ref "C273") (pin "2") (pinfunction "2_2") (pintype "unspecified"))
      (node (ref "C275") (pin "2") (pinfunction "2_2") (pintype "unspecified"))
      (node (ref "C277") (pin "2") (pinfunction "2_2") (pintype "unspecified"))
      (node (ref "C279") (pin "2") (pinfunction "2_2") (pintype "unspecified"))
      (node (ref "C281") (pin "2") (pinfunction "2_2") (pintype "unspecified"))
      (node (ref "C283") (pin "2") (pinfunction "2_2") (pintype "unspecified"))
      (node (ref "C285") (pin "2") (pinfunction "2_2") (pintype "unspecified"))
      (node (ref "C287") (pin "2") (pinfunction "2_2") (pintype "unspecified"))
      (node (ref "C289") (pin "2") (pinfunction "2_2") (pintype "unspecified"))
      (node (ref "C29") (pin "2") (pinfunction "2_2") (pintype "unspecified"))
      (node (ref "C292") (pin "2") (pinfunction "2_2") (pintype "unspecified"))
      (node (ref "C294") (pin "2") (pinfunction "2_2") (pintype "unspecified"))
      (node (ref "C296") (pin "2") (pinfunction "2_2") (pintype "unspecified"))
      (node (ref "C298") (pin "2") (pinfunction "2_2") (pintype "unspecified"))
      (node (ref "C3") (pin "2") (pinfunction "2_2") (pintype "unspecified"))
      (node (ref "C300") (pin "2") (pinfunction "2_2") (pintype "unspecified"))
      (node (ref "C302") (pin "2") (pinfunction "2_2") (pintype "unspecified"))
      (node (ref "C304") (pin "2") (pinfunction "2_2") (pintype "unspecified"))
      (node (ref "C306") (pin "2") (pinfunction "2_2") (pintype "unspecified"))
      (node (ref "C308") (pin "2") (pinfunction "2_2") (pintype "unspecified"))
      (node (ref "C31") (pin "2") (pinfunction "2_2") (pintype "unspecified"))
      (node (ref "C310") (pin "2") (pinfunction "2_2") (pintype "unspecified"))
      (node (ref "C312") (pin "2") (pinfunction "2_2") (pintype "unspecified"))
      (node (ref "C314") (pin "2") (pinfunction "2_2") (pintype "unspecified"))
      (node (ref "C316") (pin "2") (pinfunction "2_2") (pintype "unspecified"))
      (node (ref "C318") (pin "2") (pinfunction "2_2") (pintype "unspecified"))
      (node (ref "C320") (pin "2") (pinfunction "2_2") (pintype "unspecified"))
      (node (ref "C322") (pin "2") (pinfunction "2_2") (pintype "unspecified"))
      (node (ref "C323") (pin "2") (pinfunction "2_2") (pintype "unspecified"))
      (node (ref "C325") (pin "2") (pinfunction "2_2") (pintype "unspecified"))
      (node (ref "C327") (pin "2") (pinfunction "2_2") (pintype "unspecified"))
      (node (ref "C329") (pin "2") (pinfunction "2_2") (pintype "unspecified"))
      (node (ref "C331") (pin "2") (pinfunction "2_2") (pintype "unspecified"))
      (node (ref "C333") (pin "2") (pinfunction "2_2") (pintype "unspecified"))
      (node (ref "C335") (pin "2") (pinfunction "2_2") (pintype "unspecified"))
      (node (ref "C337") (pin "2") (pinfunction "2_2") (pintype "unspecified"))
      (node (ref "C339") (pin "2") (pinfunction "2_2") (pintype "unspecified"))
      (node (ref "C34") (pin "2") (pinfunction "2_2") (pintype "unspecified"))
      (node (ref "C341") (pin "2") (pinfunction "2_2") (pintype "unspecified"))
      (node (ref "C343") (pin "2") (pinfunction "2_2") (pintype "unspecified"))
      (node (ref "C345") (pin "2") (pinfunction "2_2") (pintype "unspecified"))
      (node (ref "C347") (pin "2") (pinfunction "2_2") (pintype "unspecified"))
      (node (ref "C349") (pin "2") (pinfunction "2_2") (pintype "unspecified"))
      (node (ref "C35") (pin "2") (pinfunction "2_2") (pintype "unspecified"))
      (node (ref "C351") (pin "2") (pinfunction "2_2") (pintype "unspecified"))
      (node (ref "C353") (pin "2") (pinfunction "2_2") (pintype "unspecified"))
      (node (ref "C356") (pin "2") (pinfunction "2_2") (pintype "unspecified"))
      (node (ref "C358") (pin "2") (pinfunction "2_2") (pintype "unspecified"))
      (node (ref "C360") (pin "2") (pinfunction "2_2") (pintype "unspecified"))
      (node (ref "C362") (pin "2") (pinfunction "2_2") (pintype "unspecified"))
      (node (ref "C364") (pin "2") (pinfunction "2_2") (pintype "unspecified"))
      (node (ref "C366") (pin "2") (pinfunction "2_2") (pintype "unspecified"))
      (node (ref "C368") (pin "2") (pinfunction "2_2") (pintype "unspecified"))
      (node (ref "C37") (pin "2") (pinfunction "2_2") (pintype "unspecified"))
      (node (ref "C370") (pin "2") (pinfunction "2_2") (pintype "unspecified"))
      (node (ref "C372") (pin "2") (pinfunction "2_2") (pintype "unspecified"))
      (node (ref "C374") (pin "2") (pinfunction "2_2") (pintype "unspecified"))
      (node (ref "C376") (pin "2") (pinfunction "2_2") (pintype "unspecified"))
      (node (ref "C378") (pin "2") (pinfunction "2_2") (pintype "unspecified"))
      (node (ref "C380") (pin "2") (pinfunction "2_2") (pintype "unspecified"))
      (node (ref "C382") (pin "2") (pinfunction "2_2") (pintype "unspecified"))
      (node (ref "C384") (pin "2") (pinfunction "2_2") (pintype "unspecified"))
      (node (ref "C386") (pin "2") (pinfunction "2_2") (pintype "unspecified"))
      (node (ref "C387") (pin "2") (pinfunction "2_2") (pintype "unspecified"))
      (node (ref "C389") (pin "2") (pinfunction "2_2") (pintype "unspecified"))
      (node (ref "C39") (pin "2") (pinfunction "2_2") (pintype "unspecified"))
      (node (ref "C391") (pin "2") (pinfunction "2_2") (pintype "unspecified"))
      (node (ref "C393") (pin "2") (pinfunction "2_2") (pintype "unspecified"))
      (node (ref "C395") (pin "2") (pinfunction "2_2") (pintype "unspecified"))
      (node (ref "C397") (pin "2") (pinfunction "2_2") (pintype "unspecified"))
      (node (ref "C399") (pin "2") (pinfunction "2_2") (pintype "unspecified"))
      (node (ref "C401") (pin "2") (pinfunction "2_2") (pintype "unspecified"))
      (node (ref "C403") (pin "2") (pinfunction "2_2") (pintype "unspecified"))
      (node (ref "C405") (pin "2") (pinfunction "2_2") (pintype "unspecified"))
      (node (ref "C407") (pin "2") (pinfunction "2_2") (pintype "unspecified"))
      (node (ref "C409") (pin "2") (pinfunction "2_2") (pintype "unspecified"))
      (node (ref "C41") (pin "2") (pinfunction "2_2") (pintype "unspecified"))
      (node (ref "C411") (pin "2") (pinfunction "2_2") (pintype "unspecified"))
      (node (ref "C413") (pin "2") (pinfunction "2_2") (pintype "unspecified"))
      (node (ref "C415") (pin "2") (pinfunction "2_2") (pintype "unspecified"))
      (node (ref "C417") (pin "2") (pinfunction "2_2") (pintype "unspecified"))
      (node (ref "C420") (pin "2") (pinfunction "2_2") (pintype "unspecified"))
      (node (ref "C422") (pin "2") (pinfunction "2_2") (pintype "unspecified"))
      (node (ref "C424") (pin "2") (pinfunction "2_2") (pintype "unspecified"))
      (node (ref "C426") (pin "2") (pinfunction "2_2") (pintype "unspecified"))
      (node (ref "C428") (pin "2") (pinfunction "2_2") (pintype "unspecified"))
      (node (ref "C43") (pin "2") (pinfunction "2_2") (pintype "unspecified"))
      (node (ref "C430") (pin "2") (pinfunction "2_2") (pintype "unspecified"))
      (node (ref "C432") (pin "2") (pinfunction "2_2") (pintype "unspecified"))
      (node (ref "C434") (pin "2") (pinfunction "2_2") (pintype "unspecified"))
      (node (ref "C436") (pin "2") (pinfunction "2_2") (pintype "unspecified"))
      (node (ref "C438") (pin "2") (pinfunction "2_2") (pintype "unspecified"))
      (node (ref "C440") (pin "2") (pinfunction "2_2") (pintype "unspecified"))
      (node (ref "C442") (pin "2") (pinfunction "2_2") (pintype "unspecified"))
      (node (ref "C444") (pin "2") (pinfunction "2_2") (pintype "unspecified"))
      (node (ref "C446") (pin "2") (pinfunction "2_2") (pintype "unspecified"))
      (node (ref "C448") (pin "2") (pinfunction "2_2") (pintype "unspecified"))
      (node (ref "C45") (pin "2") (pinfunction "2_2") (pintype "unspecified"))
      (node (ref "C450") (pin "2") (pinfunction "2_2") (pintype "unspecified"))
      (node (ref "C451") (pin "2") (pinfunction "2_2") (pintype "unspecified"))
      (node (ref "C453") (pin "2") (pinfunction "2_2") (pintype "unspecified"))
      (node (ref "C455") (pin "2") (pinfunction "2_2") (pintype "unspecified"))
      (node (ref "C457") (pin "2") (pinfunction "2_2") (pintype "unspecified"))
      (node (ref "C459") (pin "2") (pinfunction "2_2") (pintype "unspecified"))
      (node (ref "C461") (pin "2") (pinfunction "2_2") (pintype "unspecified"))
      (node (ref "C463") (pin "2") (pinfunction "2_2") (pintype "unspecified"))
      (node (ref "C465") (pin "2") (pinfunction "2_2") (pintype "unspecified"))
      (node (ref "C467") (pin "2") (pinfunction "2_2") (pintype "unspecified"))
      (node (ref "C469") (pin "2") (pinfunction "2_2") (pintype "unspecified"))
      (node (ref "C47") (pin "2") (pinfunction "2_2") (pintype "unspecified"))
      (node (ref "C471") (pin "2") (pinfunction "2_2") (pintype "unspecified"))
      (node (ref "C473") (pin "2") (pinfunction "2_2") (pintype "unspecified"))
      (node (ref "C475") (pin "2") (pinfunction "2_2") (pintype "unspecified"))
      (node (ref "C477") (pin "2") (pinfunction "2_2") (pintype "unspecified"))
      (node (ref "C479") (pin "2") (pinfunction "2_2") (pintype "unspecified"))
      (node (ref "C481") (pin "2") (pinfunction "2_2") (pintype "unspecified"))
      (node (ref "C484") (pin "2") (pinfunction "2_2") (pintype "unspecified"))
      (node (ref "C486") (pin "2") (pinfunction "2_2") (pintype "unspecified"))
      (node (ref "C488") (pin "2") (pinfunction "2_2") (pintype "unspecified"))
      (node (ref "C49") (pin "2") (pinfunction "2_2") (pintype "unspecified"))
      (node (ref "C490") (pin "2") (pinfunction "2_2") (pintype "unspecified"))
      (node (ref "C492") (pin "2") (pinfunction "2_2") (pintype "unspecified"))
      (node (ref "C494") (pin "2") (pinfunction "2_2") (pintype "unspecified"))
      (node (ref "C496") (pin "2") (pinfunction "2_2") (pintype "unspecified"))
      (node (ref "C498") (pin "2") (pinfunction "2_2") (pintype "unspecified"))
      (node (ref "C5") (pin "2") (pinfunction "2_2") (pintype "unspecified"))
      (node (ref "C500") (pin "2") (pinfunction "2_2") (pintype "unspecified"))
      (node (ref "C502") (pin "2") (pinfunction "2_2") (pintype "unspecified"))
      (node (ref "C504") (pin "2") (pinfunction "2_2") (pintype "unspecified"))
      (node (ref "C506") (pin "2") (pinfunction "2_2") (pintype "unspecified"))
      (node (ref "C508") (pin "2") (pinfunction "2_2") (pintype "unspecified"))
      (node (ref "C51") (pin "2") (pinfunction "2_2") (pintype "unspecified"))
      (node (ref "C510") (pin "2") (pinfunction "2_2") (pintype "unspecified"))
      (node (ref "C512") (pin "2") (pinfunction "2_2") (pintype "unspecified"))
      (node (ref "C53") (pin "2") (pinfunction "2_2") (pintype "unspecified"))
      (node (ref "C55") (pin "2") (pinfunction "2_2") (pintype "unspecified"))
      (node (ref "C57") (pin "2") (pinfunction "2_2") (pintype "unspecified"))
      (node (ref "C59") (pin "2") (pinfunction "2_2") (pintype "unspecified"))
      (node (ref "C61") (pin "2") (pinfunction "2_2") (pintype "unspecified"))
      (node (ref "C63") (pin "2") (pinfunction "2_2") (pintype "unspecified"))
      (node (ref "C65") (pin "2") (pinfunction "2_2") (pintype "unspecified"))
      (node (ref "C68") (pin "2") (pinfunction "2_2") (pintype "unspecified"))
      (node (ref "C7") (pin "2") (pinfunction "2_2") (pintype "unspecified"))
      (node (ref "C70") (pin "2") (pinfunction "2_2") (pintype "unspecified"))
      (node (ref "C72") (pin "2") (pinfunction "2_2") (pintype "unspecified"))
      (node (ref "C74") (pin "2") (pinfunction "2_2") (pintype "unspecified"))
      (node (ref "C76") (pin "2") (pinfunction "2_2") (pintype "unspecified"))
      (node (ref "C78") (pin "2") (pinfunction "2_2") (pintype "unspecified"))
      (node (ref "C80") (pin "2") (pinfunction "2_2") (pintype "unspecified"))
      (node (ref "C82") (pin "2") (pinfunction "2_2") (pintype "unspecified"))
      (node (ref "C84") (pin "2") (pinfunction "2_2") (pintype "unspecified"))
      (node (ref "C86") (pin "2") (pinfunction "2_2") (pintype "unspecified"))
      (node (ref "C88") (pin "2") (pinfunction "2_2") (pintype "unspecified"))
      (node (ref "C9") (pin "2") (pinfunction "2_2") (pintype "unspecified"))
      (node (ref "C90") (pin "2") (pinfunction "2_2") (pintype "unspecified"))
      (node (ref "C92") (pin "2") (pinfunction "2_2") (pintype "unspecified"))
      (node (ref "C94") (pin "2") (pinfunction "2_2") (pintype "unspecified"))
      (node (ref "C96") (pin "2") (pinfunction "2_2") (pintype "unspecified"))
      (node (ref "C97") (pin "2") (pinfunction "2_2") (pintype "unspecified"))
      (node (ref "C99") (pin "2") (pinfunction "2_2") (pintype "unspecified"))
      (node (ref "X10Y1") (pin "1") (pinfunction "VDD_1") (pintype "unspecified"))
      (node (ref "X10Y10") (pin "1") (pinfunction "VDD_1") (pintype "unspecified"))
      (node (ref "X10Y11") (pin "1") (pinfunction "VDD_1") (pintype "unspecified"))
      (node (ref "X10Y12") (pin "1") (pinfunction "VDD_1") (pintype "unspecified"))
      (node (ref "X10Y13") (pin "1") (pinfunction "VDD_1") (pintype "unspecified"))
      (node (ref "X10Y14") (pin "1") (pinfunction "VDD_1") (pintype "unspecified"))
      (node (ref "X10Y15") (pin "1") (pinfunction "VDD_1") (pintype "unspecified"))
      (node (ref "X10Y16") (pin "1") (pinfunction "VDD_1") (pintype "unspecified"))
      (node (ref "X10Y2") (pin "1") (pinfunction "VDD_1") (pintype "unspecified"))
      (node (ref "X10Y3") (pin "1") (pinfunction "VDD_1") (pintype "unspecified"))
      (node (ref "X10Y4") (pin "1") (pinfunction "VDD_1") (pintype "unspecified"))
      (node (ref "X10Y5") (pin "1") (pinfunction "VDD_1") (pintype "unspecified"))
      (node (ref "X10Y6") (pin "1") (pinfunction "VDD_1") (pintype "unspecified"))
      (node (ref "X10Y7") (pin "1") (pinfunction "VDD_1") (pintype "unspecified"))
      (node (ref "X10Y8") (pin "1") (pinfunction "VDD_1") (pintype "unspecified"))
      (node (ref "X10Y9") (pin "1") (pinfunction "VDD_1") (pintype "unspecified"))
      (node (ref "X11Y1") (pin "1") (pinfunction "VDD_1") (pintype "unspecified"))
      (node (ref "X11Y10") (pin "1") (pinfunction "VDD_1") (pintype "unspecified"))
      (node (ref "X11Y11") (pin "1") (pinfunction "VDD_1") (pintype "unspecified"))
      (node (ref "X11Y12") (pin "1") (pinfunction "VDD_1") (pintype "unspecified"))
      (node (ref "X11Y13") (pin "1") (pinfunction "VDD_1") (pintype "unspecified"))
      (node (ref "X11Y14") (pin "1") (pinfunction "VDD_1") (pintype "unspecified"))
      (node (ref "X11Y15") (pin "1") (pinfunction "VDD_1") (pintype "unspecified"))
      (node (ref "X11Y16") (pin "1") (pinfunction "VDD_1") (pintype "unspecified"))
      (node (ref "X11Y2") (pin "1") (pinfunction "VDD_1") (pintype "unspecified"))
      (node (ref "X11Y3") (pin "1") (pinfunction "VDD_1") (pintype "unspecified"))
      (node (ref "X11Y4") (pin "1") (pinfunction "VDD_1") (pintype "unspecified"))
      (node (ref "X11Y5") (pin "1") (pinfunction "VDD_1") (pintype "unspecified"))
      (node (ref "X11Y6") (pin "1") (pinfunction "VDD_1") (pintype "unspecified"))
      (node (ref "X11Y7") (pin "1") (pinfunction "VDD_1") (pintype "unspecified"))
      (node (ref "X11Y8") (pin "1") (pinfunction "VDD_1") (pintype "unspecified"))
      (node (ref "X11Y9") (pin "1") (pinfunction "VDD_1") (pintype "unspecified"))
      (node (ref "X12Y1") (pin "1") (pinfunction "VDD_1") (pintype "unspecified"))
      (node (ref "X12Y10") (pin "1") (pinfunction "VDD_1") (pintype "unspecified"))
      (node (ref "X12Y11") (pin "1") (pinfunction "VDD_1") (pintype "unspecified"))
      (node (ref "X12Y12") (pin "1") (pinfunction "VDD_1") (pintype "unspecified"))
      (node (ref "X12Y13") (pin "1") (pinfunction "VDD_1") (pintype "unspecified"))
      (node (ref "X12Y14") (pin "1") (pinfunction "VDD_1") (pintype "unspecified"))
      (node (ref "X12Y15") (pin "1") (pinfunction "VDD_1") (pintype "unspecified"))
      (node (ref "X12Y16") (pin "1") (pinfunction "VDD_1") (pintype "unspecified"))
      (node (ref "X12Y2") (pin "1") (pinfunction "VDD_1") (pintype "unspecified"))
      (node (ref "X12Y3") (pin "1") (pinfunction "VDD_1") (pintype "unspecified"))
      (node (ref "X12Y4") (pin "1") (pinfunction "VDD_1") (pintype "unspecified"))
      (node (ref "X12Y5") (pin "1") (pinfunction "VDD_1") (pintype "unspecified"))
      (node (ref "X12Y6") (pin "1") (pinfunction "VDD_1") (pintype "unspecified"))
      (node (ref "X12Y7") (pin "1") (pinfunction "VDD_1") (pintype "unspecified"))
      (node (ref "X12Y8") (pin "1") (pinfunction "VDD_1") (pintype "unspecified"))
      (node (ref "X12Y9") (pin "1") (pinfunction "VDD_1") (pintype "unspecified"))
      (node (ref "X13Y1") (pin "1") (pinfunction "VDD_1") (pintype "unspecified"))
      (node (ref "X13Y10") (pin "1") (pinfunction "VDD_1") (pintype "unspecified"))
      (node (ref "X13Y11") (pin "1") (pinfunction "VDD_1") (pintype "unspecified"))
      (node (ref "X13Y12") (pin "1") (pinfunction "VDD_1") (pintype "unspecified"))
      (node (ref "X13Y13") (pin "1") (pinfunction "VDD_1") (pintype "unspecified"))
      (node (ref "X13Y14") (pin "1") (pinfunction "VDD_1") (pintype "unspecified"))
      (node (ref "X13Y15") (pin "1") (pinfunction "VDD_1") (pintype "unspecified"))
      (node (ref "X13Y16") (pin "1") (pinfunction "VDD_1") (pintype "unspecified"))
      (node (ref "X13Y2") (pin "1") (pinfunction "VDD_1") (pintype "unspecified"))
      (node (ref "X13Y3") (pin "1") (pinfunction "VDD_1") (pintype "unspecified"))
      (node (ref "X13Y4") (pin "1") (pinfunction "VDD_1") (pintype "unspecified"))
      (node (ref "X13Y5") (pin "1") (pinfunction "VDD_1") (pintype "unspecified"))
      (node (ref "X13Y6") (pin "1") (pinfunction "VDD_1") (pintype "unspecified"))
      (node (ref "X13Y7") (pin "1") (pinfunction "VDD_1") (pintype "unspecified"))
      (node (ref "X13Y8") (pin "1") (pinfunction "VDD_1") (pintype "unspecified"))
      (node (ref "X13Y9") (pin "1") (pinfunction "VDD_1") (pintype "unspecified"))
      (node (ref "X14Y1") (pin "1") (pinfunction "VDD_1") (pintype "unspecified"))
      (node (ref "X14Y10") (pin "1") (pinfunction "VDD_1") (pintype "unspecified"))
      (node (ref "X14Y11") (pin "1") (pinfunction "VDD_1") (pintype "unspecified"))
      (node (ref "X14Y12") (pin "1") (pinfunction "VDD_1") (pintype "unspecified"))
      (node (ref "X14Y13") (pin "1") (pinfunction "VDD_1") (pintype "unspecified"))
      (node (ref "X14Y14") (pin "1") (pinfunction "VDD_1") (pintype "unspecified"))
      (node (ref "X14Y15") (pin "1") (pinfunction "VDD_1") (pintype "unspecified"))
      (node (ref "X14Y16") (pin "1") (pinfunction "VDD_1") (pintype "unspecified"))
      (node (ref "X14Y2") (pin "1") (pinfunction "VDD_1") (pintype "unspecified"))
      (node (ref "X14Y3") (pin "1") (pinfunction "VDD_1") (pintype "unspecified"))
      (node (ref "X14Y4") (pin "1") (pinfunction "VDD_1") (pintype "unspecified"))
      (node (ref "X14Y5") (pin "1") (pinfunction "VDD_1") (pintype "unspecified"))
      (node (ref "X14Y6") (pin "1") (pinfunction "VDD_1") (pintype "unspecified"))
      (node (ref "X14Y7") (pin "1") (pinfunction "VDD_1") (pintype "unspecified"))
      (node (ref "X14Y8") (pin "1") (pinfunction "VDD_1") (pintype "unspecified"))
      (node (ref "X14Y9") (pin "1") (pinfunction "VDD_1") (pintype "unspecified"))
      (node (ref "X15Y1") (pin "1") (pinfunction "VDD_1") (pintype "unspecified"))
      (node (ref "X15Y10") (pin "1") (pinfunction "VDD_1") (pintype "unspecified"))
      (node (ref "X15Y11") (pin "1") (pinfunction "VDD_1") (pintype "unspecified"))
      (node (ref "X15Y12") (pin "1") (pinfunction "VDD_1") (pintype "unspecified"))
      (node (ref "X15Y13") (pin "1") (pinfunction "VDD_1") (pintype "unspecified"))
      (node (ref "X15Y14") (pin "1") (pinfunction "VDD_1") (pintype "unspecified"))
      (node (ref "X15Y15") (pin "1") (pinfunction "VDD_1") (pintype "unspecified"))
      (node (ref "X15Y16") (pin "1") (pinfunction "VDD_1") (pintype "unspecified"))
      (node (ref "X15Y2") (pin "1") (pinfunction "VDD_1") (pintype "unspecified"))
      (node (ref "X15Y3") (pin "1") (pinfunction "VDD_1") (pintype "unspecified"))
      (node (ref "X15Y4") (pin "1") (pinfunction "VDD_1") (pintype "unspecified"))
      (node (ref "X15Y5") (pin "1") (pinfunction "VDD_1") (pintype "unspecified"))
      (node (ref "X15Y6") (pin "1") (pinfunction "VDD_1") (pintype "unspecified"))
      (node (ref "X15Y7") (pin "1") (pinfunction "VDD_1") (pintype "unspecified"))
      (node (ref "X15Y8") (pin "1") (pinfunction "VDD_1") (pintype "unspecified"))
      (node (ref "X15Y9") (pin "1") (pinfunction "VDD_1") (pintype "unspecified"))
      (node (ref "X16Y1") (pin "1") (pinfunction "VDD_1") (pintype "unspecified"))
      (node (ref "X16Y10") (pin "1") (pinfunction "VDD_1") (pintype "unspecified"))
      (node (ref "X16Y11") (pin "1") (pinfunction "VDD_1") (pintype "unspecified"))
      (node (ref "X16Y12") (pin "1") (pinfunction "VDD_1") (pintype "unspecified"))
      (node (ref "X16Y13") (pin "1") (pinfunction "VDD_1") (pintype "unspecified"))
      (node (ref "X16Y14") (pin "1") (pinfunction "VDD_1") (pintype "unspecified"))
      (node (ref "X16Y15") (pin "1") (pinfunction "VDD_1") (pintype "unspecified"))
      (node (ref "X16Y16") (pin "1") (pinfunction "VDD_1") (pintype "unspecified"))
      (node (ref "X16Y2") (pin "1") (pinfunction "VDD_1") (pintype "unspecified"))
      (node (ref "X16Y3") (pin "1") (pinfunction "VDD_1") (pintype "unspecified"))
      (node (ref "X16Y4") (pin "1") (pinfunction "VDD_1") (pintype "unspecified"))
      (node (ref "X16Y5") (pin "1") (pinfunction "VDD_1") (pintype "unspecified"))
      (node (ref "X16Y6") (pin "1") (pinfunction "VDD_1") (pintype "unspecified"))
      (node (ref "X16Y7") (pin "1") (pinfunction "VDD_1") (pintype "unspecified"))
      (node (ref "X16Y8") (pin "1") (pinfunction "VDD_1") (pintype "unspecified"))
      (node (ref "X16Y9") (pin "1") (pinfunction "VDD_1") (pintype "unspecified"))
      (node (ref "X1Y1") (pin "1") (pinfunction "VDD_1") (pintype "unspecified"))
      (node (ref "X1Y10") (pin "1") (pinfunction "VDD_1") (pintype "unspecified"))
      (node (ref "X1Y11") (pin "1") (pinfunction "VDD_1") (pintype "unspecified"))
      (node (ref "X1Y12") (pin "1") (pinfunction "VDD_1") (pintype "unspecified"))
      (node (ref "X1Y13") (pin "1") (pinfunction "VDD_1") (pintype "unspecified"))
      (node (ref "X1Y14") (pin "1") (pinfunction "VDD_1") (pintype "unspecified"))
      (node (ref "X1Y15") (pin "1") (pinfunction "VDD_1") (pintype "unspecified"))
      (node (ref "X1Y16") (pin "1") (pinfunction "VDD_1") (pintype "unspecified"))
      (node (ref "X1Y2") (pin "1") (pinfunction "VDD_1") (pintype "unspecified"))
      (node (ref "X1Y3") (pin "1") (pinfunction "VDD_1") (pintype "unspecified"))
      (node (ref "X1Y4") (pin "1") (pinfunction "VDD_1") (pintype "unspecified"))
      (node (ref "X1Y5") (pin "1") (pinfunction "VDD_1") (pintype "unspecified"))
      (node (ref "X1Y6") (pin "1") (pinfunction "VDD_1") (pintype "unspecified"))
      (node (ref "X1Y7") (pin "1") (pinfunction "VDD_1") (pintype "unspecified"))
      (node (ref "X1Y8") (pin "1") (pinfunction "VDD_1") (pintype "unspecified"))
      (node (ref "X1Y9") (pin "1") (pinfunction "VDD_1") (pintype "unspecified"))
      (node (ref "X2Y1") (pin "1") (pinfunction "VDD_1") (pintype "unspecified"))
      (node (ref "X2Y10") (pin "1") (pinfunction "VDD_1") (pintype "unspecified"))
      (node (ref "X2Y11") (pin "1") (pinfunction "VDD_1") (pintype "unspecified"))
      (node (ref "X2Y12") (pin "1") (pinfunction "VDD_1") (pintype "unspecified"))
      (node (ref "X2Y13") (pin "1") (pinfunction "VDD_1") (pintype "unspecified"))
      (node (ref "X2Y14") (pin "1") (pinfunction "VDD_1") (pintype "unspecified"))
      (node (ref "X2Y15") (pin "1") (pinfunction "VDD_1") (pintype "unspecified"))
      (node (ref "X2Y16") (pin "1") (pinfunction "VDD_1") (pintype "unspecified"))
      (node (ref "X2Y2") (pin "1") (pinfunction "VDD_1") (pintype "unspecified"))
      (node (ref "X2Y3") (pin "1") (pinfunction "VDD_1") (pintype "unspecified"))
      (node (ref "X2Y4") (pin "1") (pinfunction "VDD_1") (pintype "unspecified"))
      (node (ref "X2Y5") (pin "1") (pinfunction "VDD_1") (pintype "unspecified"))
      (node (ref "X2Y6") (pin "1") (pinfunction "VDD_1") (pintype "unspecified"))
      (node (ref "X2Y7") (pin "1") (pinfunction "VDD_1") (pintype "unspecified"))
      (node (ref "X2Y8") (pin "1") (pinfunction "VDD_1") (pintype "unspecified"))
      (node (ref "X2Y9") (pin "1") (pinfunction "VDD_1") (pintype "unspecified"))
      (node (ref "X3Y1") (pin "1") (pinfunction "VDD_1") (pintype "unspecified"))
      (node (ref "X3Y10") (pin "1") (pinfunction "VDD_1") (pintype "unspecified"))
      (node (ref "X3Y11") (pin "1") (pinfunction "VDD_1") (pintype "unspecified"))
      (node (ref "X3Y12") (pin "1") (pinfunction "VDD_1") (pintype "unspecified"))
      (node (ref "X3Y13") (pin "1") (pinfunction "VDD_1") (pintype "unspecified"))
      (node (ref "X3Y14") (pin "1") (pinfunction "VDD_1") (pintype "unspecified"))
      (node (ref "X3Y15") (pin "1") (pinfunction "VDD_1") (pintype "unspecified"))
      (node (ref "X3Y16") (pin "1") (pinfunction "VDD_1") (pintype "unspecified"))
      (node (ref "X3Y2") (pin "1") (pinfunction "VDD_1") (pintype "unspecified"))
      (node (ref "X3Y3") (pin "1") (pinfunction "VDD_1") (pintype "unspecified"))
      (node (ref "X3Y4") (pin "1") (pinfunction "VDD_1") (pintype "unspecified"))
      (node (ref "X3Y5") (pin "1") (pinfunction "VDD_1") (pintype "unspecified"))
      (node (ref "X3Y6") (pin "1") (pinfunction "VDD_1") (pintype "unspecified"))
      (node (ref "X3Y7") (pin "1") (pinfunction "VDD_1") (pintype "unspecified"))
      (node (ref "X3Y8") (pin "1") (pinfunction "VDD_1") (pintype "unspecified"))
      (node (ref "X3Y9") (pin "1") (pinfunction "VDD_1") (pintype "unspecified"))
      (node (ref "X4Y1") (pin "1") (pinfunction "VDD_1") (pintype "unspecified"))
      (node (ref "X4Y10") (pin "1") (pinfunction "VDD_1") (pintype "unspecified"))
      (node (ref "X4Y11") (pin "1") (pinfunction "VDD_1") (pintype "unspecified"))
      (node (ref "X4Y12") (pin "1") (pinfunction "VDD_1") (pintype "unspecified"))
      (node (ref "X4Y13") (pin "1") (pinfunction "VDD_1") (pintype "unspecified"))
      (node (ref "X4Y14") (pin "1") (pinfunction "VDD_1") (pintype "unspecified"))
      (node (ref "X4Y15") (pin "1") (pinfunction "VDD_1") (pintype "unspecified"))
      (node (ref "X4Y16") (pin "1") (pinfunction "VDD_1") (pintype "unspecified"))
      (node (ref "X4Y2") (pin "1") (pinfunction "VDD_1") (pintype "unspecified"))
      (node (ref "X4Y3") (pin "1") (pinfunction "VDD_1") (pintype "unspecified"))
      (node (ref "X4Y4") (pin "1") (pinfunction "VDD_1") (pintype "unspecified"))
      (node (ref "X4Y5") (pin "1") (pinfunction "VDD_1") (pintype "unspecified"))
      (node (ref "X4Y6") (pin "1") (pinfunction "VDD_1") (pintype "unspecified"))
      (node (ref "X4Y7") (pin "1") (pinfunction "VDD_1") (pintype "unspecified"))
      (node (ref "X4Y8") (pin "1") (pinfunction "VDD_1") (pintype "unspecified"))
      (node (ref "X4Y9") (pin "1") (pinfunction "VDD_1") (pintype "unspecified"))
      (node (ref "X5Y1") (pin "1") (pinfunction "VDD_1") (pintype "unspecified"))
      (node (ref "X5Y10") (pin "1") (pinfunction "VDD_1") (pintype "unspecified"))
      (node (ref "X5Y11") (pin "1") (pinfunction "VDD_1") (pintype "unspecified"))
      (node (ref "X5Y12") (pin "1") (pinfunction "VDD_1") (pintype "unspecified"))
      (node (ref "X5Y13") (pin "1") (pinfunction "VDD_1") (pintype "unspecified"))
      (node (ref "X5Y14") (pin "1") (pinfunction "VDD_1") (pintype "unspecified"))
      (node (ref "X5Y15") (pin "1") (pinfunction "VDD_1") (pintype "unspecified"))
      (node (ref "X5Y16") (pin "1") (pinfunction "VDD_1") (pintype "unspecified"))
      (node (ref "X5Y2") (pin "1") (pinfunction "VDD_1") (pintype "unspecified"))
      (node (ref "X5Y3") (pin "1") (pinfunction "VDD_1") (pintype "unspecified"))
      (node (ref "X5Y4") (pin "1") (pinfunction "VDD_1") (pintype "unspecified"))
      (node (ref "X5Y5") (pin "1") (pinfunction "VDD_1") (pintype "unspecified"))
      (node (ref "X5Y6") (pin "1") (pinfunction "VDD_1") (pintype "unspecified"))
      (node (ref "X5Y7") (pin "1") (pinfunction "VDD_1") (pintype "unspecified"))
      (node (ref "X5Y8") (pin "1") (pinfunction "VDD_1") (pintype "unspecified"))
      (node (ref "X5Y9") (pin "1") (pinfunction "VDD_1") (pintype "unspecified"))
      (node (ref "X6Y1") (pin "1") (pinfunction "VDD_1") (pintype "unspecified"))
      (node (ref "X6Y10") (pin "1") (pinfunction "VDD_1") (pintype "unspecified"))
      (node (ref "X6Y11") (pin "1") (pinfunction "VDD_1") (pintype "unspecified"))
      (node (ref "X6Y12") (pin "1") (pinfunction "VDD_1") (pintype "unspecified"))
      (node (ref "X6Y13") (pin "1") (pinfunction "VDD_1") (pintype "unspecified"))
      (node (ref "X6Y14") (pin "1") (pinfunction "VDD_1") (pintype "unspecified"))
      (node (ref "X6Y15") (pin "1") (pinfunction "VDD_1") (pintype "unspecified"))
      (node (ref "X6Y16") (pin "1") (pinfunction "VDD_1") (pintype "unspecified"))
      (node (ref "X6Y2") (pin "1") (pinfunction "VDD_1") (pintype "unspecified"))
      (node (ref "X6Y3") (pin "1") (pinfunction "VDD_1") (pintype "unspecified"))
      (node (ref "X6Y4") (pin "1") (pinfunction "VDD_1") (pintype "unspecified"))
      (node (ref "X6Y5") (pin "1") (pinfunction "VDD_1") (pintype "unspecified"))
      (node (ref "X6Y6") (pin "1") (pinfunction "VDD_1") (pintype "unspecified"))
      (node (ref "X6Y7") (pin "1") (pinfunction "VDD_1") (pintype "unspecified"))
      (node (ref "X6Y8") (pin "1") (pinfunction "VDD_1") (pintype "unspecified"))
      (node (ref "X6Y9") (pin "1") (pinfunction "VDD_1") (pintype "unspecified"))
      (node (ref "X7Y1") (pin "1") (pinfunction "VDD_1") (pintype "unspecified"))
      (node (ref "X7Y10") (pin "1") (pinfunction "VDD_1") (pintype "unspecified"))
      (node (ref "X7Y11") (pin "1") (pinfunction "VDD_1") (pintype "unspecified"))
      (node (ref "X7Y12") (pin "1") (pinfunction "VDD_1") (pintype "unspecified"))
      (node (ref "X7Y13") (pin "1") (pinfunction "VDD_1") (pintype "unspecified"))
      (node (ref "X7Y14") (pin "1") (pinfunction "VDD_1") (pintype "unspecified"))
      (node (ref "X7Y15") (pin "1") (pinfunction "VDD_1") (pintype "unspecified"))
      (node (ref "X7Y16") (pin "1") (pinfunction "VDD_1") (pintype "unspecified"))
      (node (ref "X7Y2") (pin "1") (pinfunction "VDD_1") (pintype "unspecified"))
      (node (ref "X7Y3") (pin "1") (pinfunction "VDD_1") (pintype "unspecified"))
      (node (ref "X7Y4") (pin "1") (pinfunction "VDD_1") (pintype "unspecified"))
      (node (ref "X7Y5") (pin "1") (pinfunction "VDD_1") (pintype "unspecified"))
      (node (ref "X7Y6") (pin "1") (pinfunction "VDD_1") (pintype "unspecified"))
      (node (ref "X7Y7") (pin "1") (pinfunction "VDD_1") (pintype "unspecified"))
      (node (ref "X7Y8") (pin "1") (pinfunction "VDD_1") (pintype "unspecified"))
      (node (ref "X7Y9") (pin "1") (pinfunction "VDD_1") (pintype "unspecified"))
      (node (ref "X8Y1") (pin "1") (pinfunction "VDD_1") (pintype "unspecified"))
      (node (ref "X8Y10") (pin "1") (pinfunction "VDD_1") (pintype "unspecified"))
      (node (ref "X8Y11") (pin "1") (pinfunction "VDD_1") (pintype "unspecified"))
      (node (ref "X8Y12") (pin "1") (pinfunction "VDD_1") (pintype "unspecified"))
      (node (ref "X8Y13") (pin "1") (pinfunction "VDD_1") (pintype "unspecified"))
      (node (ref "X8Y14") (pin "1") (pinfunction "VDD_1") (pintype "unspecified"))
      (node (ref "X8Y15") (pin "1") (pinfunction "VDD_1") (pintype "unspecified"))
      (node (ref "X8Y16") (pin "1") (pinfunction "VDD_1") (pintype "unspecified"))
      (node (ref "X8Y2") (pin "1") (pinfunction "VDD_1") (pintype "unspecified"))
      (node (ref "X8Y3") (pin "1") (pinfunction "VDD_1") (pintype "unspecified"))
      (node (ref "X8Y4") (pin "1") (pinfunction "VDD_1") (pintype "unspecified"))
      (node (ref "X8Y5") (pin "1") (pinfunction "VDD_1") (pintype "unspecified"))
      (node (ref "X8Y6") (pin "1") (pinfunction "VDD_1") (pintype "unspecified"))
      (node (ref "X8Y7") (pin "1") (pinfunction "VDD_1") (pintype "unspecified"))
      (node (ref "X8Y8") (pin "1") (pinfunction "VDD_1") (pintype "unspecified"))
      (node (ref "X8Y9") (pin "1") (pinfunction "VDD_1") (pintype "unspecified"))
      (node (ref "X9Y1") (pin "1") (pinfunction "VDD_1") (pintype "unspecified"))
      (node (ref "X9Y10") (pin "1") (pinfunction "VDD_1") (pintype "unspecified"))
      (node (ref "X9Y11") (pin "1") (pinfunction "VDD_1") (pintype "unspecified"))
      (node (ref "X9Y12") (pin "1") (pinfunction "VDD_1") (pintype "unspecified"))
      (node (ref "X9Y13") (pin "1") (pinfunction "VDD_1") (pintype "unspecified"))
      (node (ref "X9Y14") (pin "1") (pinfunction "VDD_1") (pintype "unspecified"))
      (node (ref "X9Y15") (pin "1") (pinfunction "VDD_1") (pintype "unspecified"))
      (node (ref "X9Y16") (pin "1") (pinfunction "VDD_1") (pintype "unspecified"))
      (node (ref "X9Y2") (pin "1") (pinfunction "VDD_1") (pintype "unspecified"))
      (node (ref "X9Y3") (pin "1") (pinfunction "VDD_1") (pintype "unspecified"))
      (node (ref "X9Y4") (pin "1") (pinfunction "VDD_1") (pintype "unspecified"))
      (node (ref "X9Y5") (pin "1") (pinfunction "VDD_1") (pintype "unspecified"))
      (node (ref "X9Y6") (pin "1") (pinfunction "VDD_1") (pintype "unspecified"))
      (node (ref "X9Y7") (pin "1") (pinfunction "VDD_1") (pintype "unspecified"))
      (node (ref "X9Y8") (pin "1") (pinfunction "VDD_1") (pintype "unspecified"))
      (node (ref "X9Y9") (pin "1") (pinfunction "VDD_1") (pintype "unspecified"))
    )
    (net (code "2") (name "GND") (class "Default")
      (node (ref "C1") (pin "1") (pinfunction "1_1") (pintype "unspecified"))
      (node (ref "C10") (pin "1") (pinfunction "1_1") (pintype "input"))
      (node (ref "C100") (pin "1") (pinfunction "1_1") (pintype "input"))
      (node (ref "C101") (pin "1") (pinfunction "1_1") (pintype "unspecified"))
      (node (ref "C102") (pin "1") (pinfunction "1_1") (pintype "input"))
      (node (ref "C103") (pin "1") (pinfunction "1_1") (pintype "input"))
      (node (ref "C104") (pin "1") (pinfunction "1_1") (pintype "unspecified"))
      (node (ref "C105") (pin "1") (pinfunction "1_1") (pintype "unspecified"))
      (node (ref "C106") (pin "1") (pinfunction "1_1") (pintype "input"))
      (node (ref "C107") (pin "1") (pinfunction "1_1") (pintype "unspecified"))
      (node (ref "C108") (pin "1") (pinfunction "1_1") (pintype "input"))
      (node (ref "C109") (pin "1") (pinfunction "1_1") (pintype "unspecified"))
      (node (ref "C11") (pin "1") (pinfunction "1_1") (pintype "unspecified"))
      (node (ref "C110") (pin "1") (pinfunction "1_1") (pintype "input"))
      (node (ref "C111") (pin "1") (pinfunction "1_1") (pintype "unspecified"))
      (node (ref "C112") (pin "1") (pinfunction "1_1") (pintype "input"))
      (node (ref "C113") (pin "1") (pinfunction "1_1") (pintype "unspecified"))
      (node (ref "C114") (pin "1") (pinfunction "1_1") (pintype "input"))
      (node (ref "C115") (pin "1") (pinfunction "1_1") (pintype "unspecified"))
      (node (ref "C116") (pin "1") (pinfunction "1_1") (pintype "input"))
      (node (ref "C117") (pin "1") (pinfunction "1_1") (pintype "unspecified"))
      (node (ref "C118") (pin "1") (pinfunction "1_1") (pintype "input"))
      (node (ref "C119") (pin "1") (pinfunction "1_1") (pintype "unspecified"))
      (node (ref "C12") (pin "1") (pinfunction "1_1") (pintype "input"))
      (node (ref "C120") (pin "1") (pinfunction "1_1") (pintype "input"))
      (node (ref "C121") (pin "1") (pinfunction "1_1") (pintype "unspecified"))
      (node (ref "C122") (pin "1") (pinfunction "1_1") (pintype "input"))
      (node (ref "C123") (pin "1") (pinfunction "1_1") (pintype "unspecified"))
      (node (ref "C124") (pin "1") (pinfunction "1_1") (pintype "input"))
      (node (ref "C125") (pin "1") (pinfunction "1_1") (pintype "unspecified"))
      (node (ref "C126") (pin "1") (pinfunction "1_1") (pintype "input"))
      (node (ref "C127") (pin "1") (pinfunction "1_1") (pintype "unspecified"))
      (node (ref "C128") (pin "1") (pinfunction "1_1") (pintype "input"))
      (node (ref "C129") (pin "1") (pinfunction "1_1") (pintype "unspecified"))
      (node (ref "C13") (pin "1") (pinfunction "1_1") (pintype "unspecified"))
      (node (ref "C130") (pin "1") (pinfunction "1_1") (pintype "input"))
      (node (ref "C131") (pin "1") (pinfunction "1_1") (pintype "input"))
      (node (ref "C132") (pin "1") (pinfunction "1_1") (pintype "unspecified"))
      (node (ref "C133") (pin "1") (pinfunction "1_1") (pintype "input"))
      (node (ref "C134") (pin "1") (pinfunction "1_1") (pintype "unspecified"))
      (node (ref "C135") (pin "1") (pinfunction "1_1") (pintype "input"))
      (node (ref "C136") (pin "1") (pinfunction "1_1") (pintype "unspecified"))
      (node (ref "C137") (pin "1") (pinfunction "1_1") (pintype "input"))
      (node (ref "C138") (pin "1") (pinfunction "1_1") (pintype "unspecified"))
      (node (ref "C139") (pin "1") (pinfunction "1_1") (pintype "input"))
      (node (ref "C14") (pin "1") (pinfunction "1_1") (pintype "input"))
      (node (ref "C140") (pin "1") (pinfunction "1_1") (pintype "unspecified"))
      (node (ref "C141") (pin "1") (pinfunction "1_1") (pintype "input"))
      (node (ref "C142") (pin "1") (pinfunction "1_1") (pintype "unspecified"))
      (node (ref "C143") (pin "1") (pinfunction "1_1") (pintype "input"))
      (node (ref "C144") (pin "1") (pinfunction "1_1") (pintype "unspecified"))
      (node (ref "C145") (pin "1") (pinfunction "1_1") (pintype "input"))
      (node (ref "C146") (pin "1") (pinfunction "1_1") (pintype "unspecified"))
      (node (ref "C147") (pin "1") (pinfunction "1_1") (pintype "input"))
      (node (ref "C148") (pin "1") (pinfunction "1_1") (pintype "unspecified"))
      (node (ref "C149") (pin "1") (pinfunction "1_1") (pintype "input"))
      (node (ref "C15") (pin "1") (pinfunction "1_1") (pintype "unspecified"))
      (node (ref "C150") (pin "1") (pinfunction "1_1") (pintype "unspecified"))
      (node (ref "C151") (pin "1") (pinfunction "1_1") (pintype "input"))
      (node (ref "C152") (pin "1") (pinfunction "1_1") (pintype "unspecified"))
      (node (ref "C153") (pin "1") (pinfunction "1_1") (pintype "input"))
      (node (ref "C154") (pin "1") (pinfunction "1_1") (pintype "unspecified"))
      (node (ref "C155") (pin "1") (pinfunction "1_1") (pintype "input"))
      (node (ref "C156") (pin "1") (pinfunction "1_1") (pintype "unspecified"))
      (node (ref "C157") (pin "1") (pinfunction "1_1") (pintype "input"))
      (node (ref "C158") (pin "1") (pinfunction "1_1") (pintype "unspecified"))
      (node (ref "C159") (pin "1") (pinfunction "1_1") (pintype "input"))
      (node (ref "C16") (pin "1") (pinfunction "1_1") (pintype "input"))
      (node (ref "C160") (pin "1") (pinfunction "1_1") (pintype "unspecified"))
      (node (ref "C161") (pin "1") (pinfunction "1_1") (pintype "input"))
      (node (ref "C162") (pin "1") (pinfunction "1_1") (pintype "unspecified"))
      (node (ref "C163") (pin "1") (pinfunction "1_1") (pintype "input"))
      (node (ref "C164") (pin "1") (pinfunction "1_1") (pintype "unspecified"))
      (node (ref "C165") (pin "1") (pinfunction "1_1") (pintype "input"))
      (node (ref "C166") (pin "1") (pinfunction "1_1") (pintype "unspecified"))
      (node (ref "C167") (pin "1") (pinfunction "1_1") (pintype "input"))
      (node (ref "C168") (pin "1") (pinfunction "1_1") (pintype "unspecified"))
      (node (ref "C169") (pin "1") (pinfunction "1_1") (pintype "input"))
      (node (ref "C17") (pin "1") (pinfunction "1_1") (pintype "unspecified"))
      (node (ref "C170") (pin "1") (pinfunction "1_1") (pintype "unspecified"))
      (node (ref "C171") (pin "1") (pinfunction "1_1") (pintype "input"))
      (node (ref "C172") (pin "1") (pinfunction "1_1") (pintype "unspecified"))
      (node (ref "C173") (pin "1") (pinfunction "1_1") (pintype "input"))
      (node (ref "C174") (pin "1") (pinfunction "1_1") (pintype "unspecified"))
      (node (ref "C175") (pin "1") (pinfunction "1_1") (pintype "input"))
      (node (ref "C176") (pin "1") (pinfunction "1_1") (pintype "unspecified"))
      (node (ref "C177") (pin "1") (pinfunction "1_1") (pintype "input"))
      (node (ref "C178") (pin "1") (pinfunction "1_1") (pintype "unspecified"))
      (node (ref "C179") (pin "1") (pinfunction "1_1") (pintype "input"))
      (node (ref "C18") (pin "1") (pinfunction "1_1") (pintype "input"))
      (node (ref "C180") (pin "1") (pinfunction "1_1") (pintype "unspecified"))
      (node (ref "C181") (pin "1") (pinfunction "1_1") (pintype "input"))
      (node (ref "C182") (pin "1") (pinfunction "1_1") (pintype "unspecified"))
      (node (ref "C183") (pin "1") (pinfunction "1_1") (pintype "input"))
      (node (ref "C184") (pin "1") (pinfunction "1_1") (pintype "unspecified"))
      (node (ref "C185") (pin "1") (pinfunction "1_1") (pintype "input"))
      (node (ref "C186") (pin "1") (pinfunction "1_1") (pintype "unspecified"))
      (node (ref "C187") (pin "1") (pinfunction "1_1") (pintype "input"))
      (node (ref "C188") (pin "1") (pinfunction "1_1") (pintype "unspecified"))
      (node (ref "C189") (pin "1") (pinfunction "1_1") (pintype "input"))
      (node (ref "C19") (pin "1") (pinfunction "1_1") (pintype "unspecified"))
      (node (ref "C190") (pin "1") (pinfunction "1_1") (pintype "unspecified"))
      (node (ref "C191") (pin "1") (pinfunction "1_1") (pintype "input"))
      (node (ref "C192") (pin "1") (pinfunction "1_1") (pintype "unspecified"))
      (node (ref "C193") (pin "1") (pinfunction "1_1") (pintype "input"))
      (node (ref "C194") (pin "1") (pinfunction "1_1") (pintype "unspecified"))
      (node (ref "C195") (pin "1") (pinfunction "1_1") (pintype "unspecified"))
      (node (ref "C196") (pin "1") (pinfunction "1_1") (pintype "input"))
      (node (ref "C197") (pin "1") (pinfunction "1_1") (pintype "unspecified"))
      (node (ref "C198") (pin "1") (pinfunction "1_1") (pintype "input"))
      (node (ref "C199") (pin "1") (pinfunction "1_1") (pintype "unspecified"))
      (node (ref "C2") (pin "1") (pinfunction "1_1") (pintype "input"))
      (node (ref "C20") (pin "1") (pinfunction "1_1") (pintype "input"))
      (node (ref "C200") (pin "1") (pinfunction "1_1") (pintype "input"))
      (node (ref "C201") (pin "1") (pinfunction "1_1") (pintype "unspecified"))
      (node (ref "C202") (pin "1") (pinfunction "1_1") (pintype "input"))
      (node (ref "C203") (pin "1") (pinfunction "1_1") (pintype "unspecified"))
      (node (ref "C204") (pin "1") (pinfunction "1_1") (pintype "input"))
      (node (ref "C205") (pin "1") (pinfunction "1_1") (pintype "unspecified"))
      (node (ref "C206") (pin "1") (pinfunction "1_1") (pintype "input"))
      (node (ref "C207") (pin "1") (pinfunction "1_1") (pintype "unspecified"))
      (node (ref "C208") (pin "1") (pinfunction "1_1") (pintype "input"))
      (node (ref "C209") (pin "1") (pinfunction "1_1") (pintype "unspecified"))
      (node (ref "C21") (pin "1") (pinfunction "1_1") (pintype "unspecified"))
      (node (ref "C210") (pin "1") (pinfunction "1_1") (pintype "input"))
      (node (ref "C211") (pin "1") (pinfunction "1_1") (pintype "unspecified"))
      (node (ref "C212") (pin "1") (pinfunction "1_1") (pintype "input"))
      (node (ref "C213") (pin "1") (pinfunction "1_1") (pintype "unspecified"))
      (node (ref "C214") (pin "1") (pinfunction "1_1") (pintype "input"))
      (node (ref "C215") (pin "1") (pinfunction "1_1") (pintype "unspecified"))
      (node (ref "C216") (pin "1") (pinfunction "1_1") (pintype "input"))
      (node (ref "C217") (pin "1") (pinfunction "1_1") (pintype "unspecified"))
      (node (ref "C218") (pin "1") (pinfunction "1_1") (pintype "input"))
      (node (ref "C219") (pin "1") (pinfunction "1_1") (pintype "unspecified"))
      (node (ref "C22") (pin "1") (pinfunction "1_1") (pintype "input"))
      (node (ref "C220") (pin "1") (pinfunction "1_1") (pintype "input"))
      (node (ref "C221") (pin "1") (pinfunction "1_1") (pintype "unspecified"))
      (node (ref "C222") (pin "1") (pinfunction "1_1") (pintype "input"))
      (node (ref "C223") (pin "1") (pinfunction "1_1") (pintype "unspecified"))
      (node (ref "C224") (pin "1") (pinfunction "1_1") (pintype "input"))
      (node (ref "C225") (pin "1") (pinfunction "1_1") (pintype "unspecified"))
      (node (ref "C226") (pin "1") (pinfunction "1_1") (pintype "input"))
      (node (ref "C227") (pin "1") (pinfunction "1_1") (pintype "input"))
      (node (ref "C228") (pin "1") (pinfunction "1_1") (pintype "unspecified"))
      (node (ref "C229") (pin "1") (pinfunction "1_1") (pintype "input"))
      (node (ref "C23") (pin "1") (pinfunction "1_1") (pintype "unspecified"))
      (node (ref "C230") (pin "1") (pinfunction "1_1") (pintype "unspecified"))
      (node (ref "C231") (pin "1") (pinfunction "1_1") (pintype "input"))
      (node (ref "C232") (pin "1") (pinfunction "1_1") (pintype "unspecified"))
      (node (ref "C233") (pin "1") (pinfunction "1_1") (pintype "input"))
      (node (ref "C234") (pin "1") (pinfunction "1_1") (pintype "unspecified"))
      (node (ref "C235") (pin "1") (pinfunction "1_1") (pintype "input"))
      (node (ref "C236") (pin "1") (pinfunction "1_1") (pintype "unspecified"))
      (node (ref "C237") (pin "1") (pinfunction "1_1") (pintype "input"))
      (node (ref "C238") (pin "1") (pinfunction "1_1") (pintype "unspecified"))
      (node (ref "C239") (pin "1") (pinfunction "1_1") (pintype "input"))
      (node (ref "C24") (pin "1") (pinfunction "1_1") (pintype "input"))
      (node (ref "C240") (pin "1") (pinfunction "1_1") (pintype "unspecified"))
      (node (ref "C241") (pin "1") (pinfunction "1_1") (pintype "input"))
      (node (ref "C242") (pin "1") (pinfunction "1_1") (pintype "unspecified"))
      (node (ref "C243") (pin "1") (pinfunction "1_1") (pintype "input"))
      (node (ref "C244") (pin "1") (pinfunction "1_1") (pintype "unspecified"))
      (node (ref "C245") (pin "1") (pinfunction "1_1") (pintype "input"))
      (node (ref "C246") (pin "1") (pinfunction "1_1") (pintype "unspecified"))
      (node (ref "C247") (pin "1") (pinfunction "1_1") (pintype "input"))
      (node (ref "C248") (pin "1") (pinfunction "1_1") (pintype "unspecified"))
      (node (ref "C249") (pin "1") (pinfunction "1_1") (pintype "input"))
      (node (ref "C25") (pin "1") (pinfunction "1_1") (pintype "unspecified"))
      (node (ref "C250") (pin "1") (pinfunction "1_1") (pintype "unspecified"))
      (node (ref "C251") (pin "1") (pinfunction "1_1") (pintype "input"))
      (node (ref "C252") (pin "1") (pinfunction "1_1") (pintype "unspecified"))
      (node (ref "C253") (pin "1") (pinfunction "1_1") (pintype "input"))
      (node (ref "C254") (pin "1") (pinfunction "1_1") (pintype "unspecified"))
      (node (ref "C255") (pin "1") (pinfunction "1_1") (pintype "input"))
      (node (ref "C256") (pin "1") (pinfunction "1_1") (pintype "unspecified"))
      (node (ref "C257") (pin "1") (pinfunction "1_1") (pintype "input"))
      (node (ref "C258") (pin "1") (pinfunction "1_1") (pintype "unspecified"))
      (node (ref "C259") (pin "1") (pinfunction "1_1") (pintype "unspecified"))
      (node (ref "C26") (pin "1") (pinfunction "1_1") (pintype "input"))
      (node (ref "C260") (pin "1") (pinfunction "1_1") (pintype "input"))
      (node (ref "C261") (pin "1") (pinfunction "1_1") (pintype "unspecified"))
      (node (ref "C262") (pin "1") (pinfunction "1_1") (pintype "input"))
      (node (ref "C263") (pin "1") (pinfunction "1_1") (pintype "unspecified"))
      (node (ref "C264") (pin "1") (pinfunction "1_1") (pintype "input"))
      (node (ref "C265") (pin "1") (pinfunction "1_1") (pintype "unspecified"))
      (node (ref "C266") (pin "1") (pinfunction "1_1") (pintype "input"))
      (node (ref "C267") (pin "1") (pinfunction "1_1") (pintype "unspecified"))
      (node (ref "C268") (pin "1") (pinfunction "1_1") (pintype "input"))
      (node (ref "C269") (pin "1") (pinfunction "1_1") (pintype "unspecified"))
      (node (ref "C27") (pin "1") (pinfunction "1_1") (pintype "unspecified"))
      (node (ref "C270") (pin "1") (pinfunction "1_1") (pintype "input"))
      (node (ref "C271") (pin "1") (pinfunction "1_1") (pintype "unspecified"))
      (node (ref "C272") (pin "1") (pinfunction "1_1") (pintype "input"))
      (node (ref "C273") (pin "1") (pinfunction "1_1") (pintype "unspecified"))
      (node (ref "C274") (pin "1") (pinfunction "1_1") (pintype "input"))
      (node (ref "C275") (pin "1") (pinfunction "1_1") (pintype "unspecified"))
      (node (ref "C276") (pin "1") (pinfunction "1_1") (pintype "input"))
      (node (ref "C277") (pin "1") (pinfunction "1_1") (pintype "unspecified"))
      (node (ref "C278") (pin "1") (pinfunction "1_1") (pintype "input"))
      (node (ref "C279") (pin "1") (pinfunction "1_1") (pintype "unspecified"))
      (node (ref "C28") (pin "1") (pinfunction "1_1") (pintype "input"))
      (node (ref "C280") (pin "1") (pinfunction "1_1") (pintype "input"))
      (node (ref "C281") (pin "1") (pinfunction "1_1") (pintype "unspecified"))
      (node (ref "C282") (pin "1") (pinfunction "1_1") (pintype "input"))
      (node (ref "C283") (pin "1") (pinfunction "1_1") (pintype "unspecified"))
      (node (ref "C284") (pin "1") (pinfunction "1_1") (pintype "input"))
      (node (ref "C285") (pin "1") (pinfunction "1_1") (pintype "unspecified"))
      (node (ref "C286") (pin "1") (pinfunction "1_1") (pintype "input"))
      (node (ref "C287") (pin "1") (pinfunction "1_1") (pintype "unspecified"))
      (node (ref "C288") (pin "1") (pinfunction "1_1") (pintype "input"))
      (node (ref "C289") (pin "1") (pinfunction "1_1") (pintype "unspecified"))
      (node (ref "C29") (pin "1") (pinfunction "1_1") (pintype "unspecified"))
      (node (ref "C290") (pin "1") (pinfunction "1_1") (pintype "input"))
      (node (ref "C291") (pin "1") (pinfunction "1_1") (pintype "input"))
      (node (ref "C292") (pin "1") (pinfunction "1_1") (pintype "unspecified"))
      (node (ref "C293") (pin "1") (pinfunction "1_1") (pintype "input"))
      (node (ref "C294") (pin "1") (pinfunction "1_1") (pintype "unspecified"))
      (node (ref "C295") (pin "1") (pinfunction "1_1") (pintype "input"))
      (node (ref "C296") (pin "1") (pinfunction "1_1") (pintype "unspecified"))
      (node (ref "C297") (pin "1") (pinfunction "1_1") (pintype "input"))
      (node (ref "C298") (pin "1") (pinfunction "1_1") (pintype "unspecified"))
      (node (ref "C299") (pin "1") (pinfunction "1_1") (pintype "input"))
      (node (ref "C3") (pin "1") (pinfunction "1_1") (pintype "unspecified"))
      (node (ref "C30") (pin "1") (pinfunction "1_1") (pintype "input"))
      (node (ref "C300") (pin "1") (pinfunction "1_1") (pintype "unspecified"))
      (node (ref "C301") (pin "1") (pinfunction "1_1") (pintype "input"))
      (node (ref "C302") (pin "1") (pinfunction "1_1") (pintype "unspecified"))
      (node (ref "C303") (pin "1") (pinfunction "1_1") (pintype "input"))
      (node (ref "C304") (pin "1") (pinfunction "1_1") (pintype "unspecified"))
      (node (ref "C305") (pin "1") (pinfunction "1_1") (pintype "input"))
      (node (ref "C306") (pin "1") (pinfunction "1_1") (pintype "unspecified"))
      (node (ref "C307") (pin "1") (pinfunction "1_1") (pintype "input"))
      (node (ref "C308") (pin "1") (pinfunction "1_1") (pintype "unspecified"))
      (node (ref "C309") (pin "1") (pinfunction "1_1") (pintype "input"))
      (node (ref "C31") (pin "1") (pinfunction "1_1") (pintype "unspecified"))
      (node (ref "C310") (pin "1") (pinfunction "1_1") (pintype "unspecified"))
      (node (ref "C311") (pin "1") (pinfunction "1_1") (pintype "input"))
      (node (ref "C312") (pin "1") (pinfunction "1_1") (pintype "unspecified"))
      (node (ref "C313") (pin "1") (pinfunction "1_1") (pintype "input"))
      (node (ref "C314") (pin "1") (pinfunction "1_1") (pintype "unspecified"))
      (node (ref "C315") (pin "1") (pinfunction "1_1") (pintype "input"))
      (node (ref "C316") (pin "1") (pinfunction "1_1") (pintype "unspecified"))
      (node (ref "C317") (pin "1") (pinfunction "1_1") (pintype "input"))
      (node (ref "C318") (pin "1") (pinfunction "1_1") (pintype "unspecified"))
      (node (ref "C319") (pin "1") (pinfunction "1_1") (pintype "input"))
      (node (ref "C32") (pin "1") (pinfunction "1_1") (pintype "input"))
      (node (ref "C320") (pin "1") (pinfunction "1_1") (pintype "unspecified"))
      (node (ref "C321") (pin "1") (pinfunction "1_1") (pintype "input"))
      (node (ref "C322") (pin "1") (pinfunction "1_1") (pintype "unspecified"))
      (node (ref "C323") (pin "1") (pinfunction "1_1") (pintype "unspecified"))
      (node (ref "C324") (pin "1") (pinfunction "1_1") (pintype "input"))
      (node (ref "C325") (pin "1") (pinfunction "1_1") (pintype "unspecified"))
      (node (ref "C326") (pin "1") (pinfunction "1_1") (pintype "input"))
      (node (ref "C327") (pin "1") (pinfunction "1_1") (pintype "unspecified"))
      (node (ref "C328") (pin "1") (pinfunction "1_1") (pintype "input"))
      (node (ref "C329") (pin "1") (pinfunction "1_1") (pintype "unspecified"))
      (node (ref "C33") (pin "1") (pinfunction "1_1") (pintype "input"))
      (node (ref "C330") (pin "1") (pinfunction "1_1") (pintype "input"))
      (node (ref "C331") (pin "1") (pinfunction "1_1") (pintype "unspecified"))
      (node (ref "C332") (pin "1") (pinfunction "1_1") (pintype "input"))
      (node (ref "C333") (pin "1") (pinfunction "1_1") (pintype "unspecified"))
      (node (ref "C334") (pin "1") (pinfunction "1_1") (pintype "input"))
      (node (ref "C335") (pin "1") (pinfunction "1_1") (pintype "unspecified"))
      (node (ref "C336") (pin "1") (pinfunction "1_1") (pintype "input"))
      (node (ref "C337") (pin "1") (pinfunction "1_1") (pintype "unspecified"))
      (node (ref "C338") (pin "1") (pinfunction "1_1") (pintype "input"))
      (node (ref "C339") (pin "1") (pinfunction "1_1") (pintype "unspecified"))
      (node (ref "C34") (pin "1") (pinfunction "1_1") (pintype "unspecified"))
      (node (ref "C340") (pin "1") (pinfunction "1_1") (pintype "input"))
      (node (ref "C341") (pin "1") (pinfunction "1_1") (pintype "unspecified"))
      (node (ref "C342") (pin "1") (pinfunction "1_1") (pintype "input"))
      (node (ref "C343") (pin "1") (pinfunction "1_1") (pintype "unspecified"))
      (node (ref "C344") (pin "1") (pinfunction "1_1") (pintype "input"))
      (node (ref "C345") (pin "1") (pinfunction "1_1") (pintype "unspecified"))
      (node (ref "C346") (pin "1") (pinfunction "1_1") (pintype "input"))
      (node (ref "C347") (pin "1") (pinfunction "1_1") (pintype "unspecified"))
      (node (ref "C348") (pin "1") (pinfunction "1_1") (pintype "input"))
      (node (ref "C349") (pin "1") (pinfunction "1_1") (pintype "unspecified"))
      (node (ref "C35") (pin "1") (pinfunction "1_1") (pintype "unspecified"))
      (node (ref "C350") (pin "1") (pinfunction "1_1") (pintype "input"))
      (node (ref "C351") (pin "1") (pinfunction "1_1") (pintype "unspecified"))
      (node (ref "C352") (pin "1") (pinfunction "1_1") (pintype "input"))
      (node (ref "C353") (pin "1") (pinfunction "1_1") (pintype "unspecified"))
      (node (ref "C354") (pin "1") (pinfunction "1_1") (pintype "input"))
      (node (ref "C355") (pin "1") (pinfunction "1_1") (pintype "input"))
      (node (ref "C356") (pin "1") (pinfunction "1_1") (pintype "unspecified"))
      (node (ref "C357") (pin "1") (pinfunction "1_1") (pintype "input"))
      (node (ref "C358") (pin "1") (pinfunction "1_1") (pintype "unspecified"))
      (node (ref "C359") (pin "1") (pinfunction "1_1") (pintype "input"))
      (node (ref "C36") (pin "1") (pinfunction "1_1") (pintype "input"))
      (node (ref "C360") (pin "1") (pinfunction "1_1") (pintype "unspecified"))
      (node (ref "C361") (pin "1") (pinfunction "1_1") (pintype "input"))
      (node (ref "C362") (pin "1") (pinfunction "1_1") (pintype "unspecified"))
      (node (ref "C363") (pin "1") (pinfunction "1_1") (pintype "input"))
      (node (ref "C364") (pin "1") (pinfunction "1_1") (pintype "unspecified"))
      (node (ref "C365") (pin "1") (pinfunction "1_1") (pintype "input"))
      (node (ref "C366") (pin "1") (pinfunction "1_1") (pintype "unspecified"))
      (node (ref "C367") (pin "1") (pinfunction "1_1") (pintype "input"))
      (node (ref "C368") (pin "1") (pinfunction "1_1") (pintype "unspecified"))
      (node (ref "C369") (pin "1") (pinfunction "1_1") (pintype "input"))
      (node (ref "C37") (pin "1") (pinfunction "1_1") (pintype "unspecified"))
      (node (ref "C370") (pin "1") (pinfunction "1_1") (pintype "unspecified"))
      (node (ref "C371") (pin "1") (pinfunction "1_1") (pintype "input"))
      (node (ref "C372") (pin "1") (pinfunction "1_1") (pintype "unspecified"))
      (node (ref "C373") (pin "1") (pinfunction "1_1") (pintype "input"))
      (node (ref "C374") (pin "1") (pinfunction "1_1") (pintype "unspecified"))
      (node (ref "C375") (pin "1") (pinfunction "1_1") (pintype "input"))
      (node (ref "C376") (pin "1") (pinfunction "1_1") (pintype "unspecified"))
      (node (ref "C377") (pin "1") (pinfunction "1_1") (pintype "input"))
      (node (ref "C378") (pin "1") (pinfunction "1_1") (pintype "unspecified"))
      (node (ref "C379") (pin "1") (pinfunction "1_1") (pintype "input"))
      (node (ref "C38") (pin "1") (pinfunction "1_1") (pintype "input"))
      (node (ref "C380") (pin "1") (pinfunction "1_1") (pintype "unspecified"))
      (node (ref "C381") (pin "1") (pinfunction "1_1") (pintype "input"))
      (node (ref "C382") (pin "1") (pinfunction "1_1") (pintype "unspecified"))
      (node (ref "C383") (pin "1") (pinfunction "1_1") (pintype "input"))
      (node (ref "C384") (pin "1") (pinfunction "1_1") (pintype "unspecified"))
      (node (ref "C385") (pin "1") (pinfunction "1_1") (pintype "input"))
      (node (ref "C386") (pin "1") (pinfunction "1_1") (pintype "unspecified"))
      (node (ref "C387") (pin "1") (pinfunction "1_1") (pintype "unspecified"))
      (node (ref "C388") (pin "1") (pinfunction "1_1") (pintype "input"))
      (node (ref "C389") (pin "1") (pinfunction "1_1") (pintype "unspecified"))
      (node (ref "C39") (pin "1") (pinfunction "1_1") (pintype "unspecified"))
      (node (ref "C390") (pin "1") (pinfunction "1_1") (pintype "input"))
      (node (ref "C391") (pin "1") (pinfunction "1_1") (pintype "unspecified"))
      (node (ref "C392") (pin "1") (pinfunction "1_1") (pintype "input"))
      (node (ref "C393") (pin "1") (pinfunction "1_1") (pintype "unspecified"))
      (node (ref "C394") (pin "1") (pinfunction "1_1") (pintype "input"))
      (node (ref "C395") (pin "1") (pinfunction "1_1") (pintype "unspecified"))
      (node (ref "C396") (pin "1") (pinfunction "1_1") (pintype "input"))
      (node (ref "C397") (pin "1") (pinfunction "1_1") (pintype "unspecified"))
      (node (ref "C398") (pin "1") (pinfunction "1_1") (pintype "input"))
      (node (ref "C399") (pin "1") (pinfunction "1_1") (pintype "unspecified"))
      (node (ref "C4") (pin "1") (pinfunction "1_1") (pintype "input"))
      (node (ref "C40") (pin "1") (pinfunction "1_1") (pintype "input"))
      (node (ref "C400") (pin "1") (pinfunction "1_1") (pintype "input"))
      (node (ref "C401") (pin "1") (pinfunction "1_1") (pintype "unspecified"))
      (node (ref "C402") (pin "1") (pinfunction "1_1") (pintype "input"))
      (node (ref "C403") (pin "1") (pinfunction "1_1") (pintype "unspecified"))
      (node (ref "C404") (pin "1") (pinfunction "1_1") (pintype "input"))
      (node (ref "C405") (pin "1") (pinfunction "1_1") (pintype "unspecified"))
      (node (ref "C406") (pin "1") (pinfunction "1_1") (pintype "input"))
      (node (ref "C407") (pin "1") (pinfunction "1_1") (pintype "unspecified"))
      (node (ref "C408") (pin "1") (pinfunction "1_1") (pintype "input"))
      (node (ref "C409") (pin "1") (pinfunction "1_1") (pintype "unspecified"))
      (node (ref "C41") (pin "1") (pinfunction "1_1") (pintype "unspecified"))
      (node (ref "C410") (pin "1") (pinfunction "1_1") (pintype "input"))
      (node (ref "C411") (pin "1") (pinfunction "1_1") (pintype "unspecified"))
      (node (ref "C412") (pin "1") (pinfunction "1_1") (pintype "input"))
      (node (ref "C413") (pin "1") (pinfunction "1_1") (pintype "unspecified"))
      (node (ref "C414") (pin "1") (pinfunction "1_1") (pintype "input"))
      (node (ref "C415") (pin "1") (pinfunction "1_1") (pintype "unspecified"))
      (node (ref "C416") (pin "1") (pinfunction "1_1") (pintype "input"))
      (node (ref "C417") (pin "1") (pinfunction "1_1") (pintype "unspecified"))
      (node (ref "C418") (pin "1") (pinfunction "1_1") (pintype "input"))
      (node (ref "C419") (pin "1") (pinfunction "1_1") (pintype "input"))
      (node (ref "C42") (pin "1") (pinfunction "1_1") (pintype "input"))
      (node (ref "C420") (pin "1") (pinfunction "1_1") (pintype "unspecified"))
      (node (ref "C421") (pin "1") (pinfunction "1_1") (pintype "input"))
      (node (ref "C422") (pin "1") (pinfunction "1_1") (pintype "unspecified"))
      (node (ref "C423") (pin "1") (pinfunction "1_1") (pintype "input"))
      (node (ref "C424") (pin "1") (pinfunction "1_1") (pintype "unspecified"))
      (node (ref "C425") (pin "1") (pinfunction "1_1") (pintype "input"))
      (node (ref "C426") (pin "1") (pinfunction "1_1") (pintype "unspecified"))
      (node (ref "C427") (pin "1") (pinfunction "1_1") (pintype "input"))
      (node (ref "C428") (pin "1") (pinfunction "1_1") (pintype "unspecified"))
      (node (ref "C429") (pin "1") (pinfunction "1_1") (pintype "input"))
      (node (ref "C43") (pin "1") (pinfunction "1_1") (pintype "unspecified"))
      (node (ref "C430") (pin "1") (pinfunction "1_1") (pintype "unspecified"))
      (node (ref "C431") (pin "1") (pinfunction "1_1") (pintype "input"))
      (node (ref "C432") (pin "1") (pinfunction "1_1") (pintype "unspecified"))
      (node (ref "C433") (pin "1") (pinfunction "1_1") (pintype "input"))
      (node (ref "C434") (pin "1") (pinfunction "1_1") (pintype "unspecified"))
      (node (ref "C435") (pin "1") (pinfunction "1_1") (pintype "input"))
      (node (ref "C436") (pin "1") (pinfunction "1_1") (pintype "unspecified"))
      (node (ref "C437") (pin "1") (pinfunction "1_1") (pintype "input"))
      (node (ref "C438") (pin "1") (pinfunction "1_1") (pintype "unspecified"))
      (node (ref "C439") (pin "1") (pinfunction "1_1") (pintype "input"))
      (node (ref "C44") (pin "1") (pinfunction "1_1") (pintype "input"))
      (node (ref "C440") (pin "1") (pinfunction "1_1") (pintype "unspecified"))
      (node (ref "C441") (pin "1") (pinfunction "1_1") (pintype "input"))
      (node (ref "C442") (pin "1") (pinfunction "1_1") (pintype "unspecified"))
      (node (ref "C443") (pin "1") (pinfunction "1_1") (pintype "input"))
      (node (ref "C444") (pin "1") (pinfunction "1_1") (pintype "unspecified"))
      (node (ref "C445") (pin "1") (pinfunction "1_1") (pintype "input"))
      (node (ref "C446") (pin "1") (pinfunction "1_1") (pintype "unspecified"))
      (node (ref "C447") (pin "1") (pinfunction "1_1") (pintype "input"))
      (node (ref "C448") (pin "1") (pinfunction "1_1") (pintype "unspecified"))
      (node (ref "C449") (pin "1") (pinfunction "1_1") (pintype "input"))
      (node (ref "C45") (pin "1") (pinfunction "1_1") (pintype "unspecified"))
      (node (ref "C450") (pin "1") (pinfunction "1_1") (pintype "unspecified"))
      (node (ref "C451") (pin "1") (pinfunction "1_1") (pintype "unspecified"))
      (node (ref "C452") (pin "1") (pinfunction "1_1") (pintype "input"))
      (node (ref "C453") (pin "1") (pinfunction "1_1") (pintype "unspecified"))
      (node (ref "C454") (pin "1") (pinfunction "1_1") (pintype "input"))
      (node (ref "C455") (pin "1") (pinfunction "1_1") (pintype "unspecified"))
      (node (ref "C456") (pin "1") (pinfunction "1_1") (pintype "input"))
      (node (ref "C457") (pin "1") (pinfunction "1_1") (pintype "unspecified"))
      (node (ref "C458") (pin "1") (pinfunction "1_1") (pintype "input"))
      (node (ref "C459") (pin "1") (pinfunction "1_1") (pintype "unspecified"))
      (node (ref "C46") (pin "1") (pinfunction "1_1") (pintype "input"))
      (node (ref "C460") (pin "1") (pinfunction "1_1") (pintype "input"))
      (node (ref "C461") (pin "1") (pinfunction "1_1") (pintype "unspecified"))
      (node (ref "C462") (pin "1") (pinfunction "1_1") (pintype "input"))
      (node (ref "C463") (pin "1") (pinfunction "1_1") (pintype "unspecified"))
      (node (ref "C464") (pin "1") (pinfunction "1_1") (pintype "input"))
      (node (ref "C465") (pin "1") (pinfunction "1_1") (pintype "unspecified"))
      (node (ref "C466") (pin "1") (pinfunction "1_1") (pintype "input"))
      (node (ref "C467") (pin "1") (pinfunction "1_1") (pintype "unspecified"))
      (node (ref "C468") (pin "1") (pinfunction "1_1") (pintype "input"))
      (node (ref "C469") (pin "1") (pinfunction "1_1") (pintype "unspecified"))
      (node (ref "C47") (pin "1") (pinfunction "1_1") (pintype "unspecified"))
      (node (ref "C470") (pin "1") (pinfunction "1_1") (pintype "input"))
      (node (ref "C471") (pin "1") (pinfunction "1_1") (pintype "unspecified"))
      (node (ref "C472") (pin "1") (pinfunction "1_1") (pintype "input"))
      (node (ref "C473") (pin "1") (pinfunction "1_1") (pintype "unspecified"))
      (node (ref "C474") (pin "1") (pinfunction "1_1") (pintype "input"))
      (node (ref "C475") (pin "1") (pinfunction "1_1") (pintype "unspecified"))
      (node (ref "C476") (pin "1") (pinfunction "1_1") (pintype "input"))
      (node (ref "C477") (pin "1") (pinfunction "1_1") (pintype "unspecified"))
      (node (ref "C478") (pin "1") (pinfunction "1_1") (pintype "input"))
      (node (ref "C479") (pin "1") (pinfunction "1_1") (pintype "unspecified"))
      (node (ref "C48") (pin "1") (pinfunction "1_1") (pintype "input"))
      (node (ref "C480") (pin "1") (pinfunction "1_1") (pintype "input"))
      (node (ref "C481") (pin "1") (pinfunction "1_1") (pintype "unspecified"))
      (node (ref "C482") (pin "1") (pinfunction "1_1") (pintype "input"))
      (node (ref "C483") (pin "1") (pinfunction "1_1") (pintype "input"))
      (node (ref "C484") (pin "1") (pinfunction "1_1") (pintype "unspecified"))
      (node (ref "C485") (pin "1") (pinfunction "1_1") (pintype "input"))
      (node (ref "C486") (pin "1") (pinfunction "1_1") (pintype "unspecified"))
      (node (ref "C487") (pin "1") (pinfunction "1_1") (pintype "input"))
      (node (ref "C488") (pin "1") (pinfunction "1_1") (pintype "unspecified"))
      (node (ref "C489") (pin "1") (pinfunction "1_1") (pintype "input"))
      (node (ref "C49") (pin "1") (pinfunction "1_1") (pintype "unspecified"))
      (node (ref "C490") (pin "1") (pinfunction "1_1") (pintype "unspecified"))
      (node (ref "C491") (pin "1") (pinfunction "1_1") (pintype "input"))
      (node (ref "C492") (pin "1") (pinfunction "1_1") (pintype "unspecified"))
      (node (ref "C493") (pin "1") (pinfunction "1_1") (pintype "input"))
      (node (ref "C494") (pin "1") (pinfunction "1_1") (pintype "unspecified"))
      (node (ref "C495") (pin "1") (pinfunction "1_1") (pintype "input"))
      (node (ref "C496") (pin "1") (pinfunction "1_1") (pintype "unspecified"))
      (node (ref "C497") (pin "1") (pinfunction "1_1") (pintype "input"))
      (node (ref "C498") (pin "1") (pinfunction "1_1") (pintype "unspecified"))
      (node (ref "C499") (pin "1") (pinfunction "1_1") (pintype "input"))
      (node (ref "C5") (pin "1") (pinfunction "1_1") (pintype "unspecified"))
      (node (ref "C50") (pin "1") (pinfunction "1_1") (pintype "input"))
      (node (ref "C500") (pin "1") (pinfunction "1_1") (pintype "unspecified"))
      (node (ref "C501") (pin "1") (pinfunction "1_1") (pintype "input"))
      (node (ref "C502") (pin "1") (pinfunction "1_1") (pintype "unspecified"))
      (node (ref "C503") (pin "1") (pinfunction "1_1") (pintype "input"))
      (node (ref "C504") (pin "1") (pinfunction "1_1") (pintype "unspecified"))
      (node (ref "C505") (pin "1") (pinfunction "1_1") (pintype "input"))
      (node (ref "C506") (pin "1") (pinfunction "1_1") (pintype "unspecified"))
      (node (ref "C507") (pin "1") (pinfunction "1_1") (pintype "input"))
      (node (ref "C508") (pin "1") (pinfunction "1_1") (pintype "unspecified"))
      (node (ref "C509") (pin "1") (pinfunction "1_1") (pintype "input"))
      (node (ref "C51") (pin "1") (pinfunction "1_1") (pintype "unspecified"))
      (node (ref "C510") (pin "1") (pinfunction "1_1") (pintype "unspecified"))
      (node (ref "C511") (pin "1") (pinfunction "1_1") (pintype "input"))
      (node (ref "C512") (pin "1") (pinfunction "1_1") (pintype "unspecified"))
      (node (ref "C52") (pin "1") (pinfunction "1_1") (pintype "input"))
      (node (ref "C53") (pin "1") (pinfunction "1_1") (pintype "unspecified"))
      (node (ref "C54") (pin "1") (pinfunction "1_1") (pintype "input"))
      (node (ref "C55") (pin "1") (pinfunction "1_1") (pintype "unspecified"))
      (node (ref "C56") (pin "1") (pinfunction "1_1") (pintype "input"))
      (node (ref "C57") (pin "1") (pinfunction "1_1") (pintype "unspecified"))
      (node (ref "C58") (pin "1") (pinfunction "1_1") (pintype "input"))
      (node (ref "C59") (pin "1") (pinfunction "1_1") (pintype "unspecified"))
      (node (ref "C6") (pin "1") (pinfunction "1_1") (pintype "input"))
      (node (ref "C60") (pin "1") (pinfunction "1_1") (pintype "input"))
      (node (ref "C61") (pin "1") (pinfunction "1_1") (pintype "unspecified"))
      (node (ref "C62") (pin "1") (pinfunction "1_1") (pintype "input"))
      (node (ref "C63") (pin "1") (pinfunction "1_1") (pintype "unspecified"))
      (node (ref "C64") (pin "1") (pinfunction "1_1") (pintype "input"))
      (node (ref "C65") (pin "1") (pinfunction "1_1") (pintype "unspecified"))
      (node (ref "C66") (pin "1") (pinfunction "1_1") (pintype "input"))
      (node (ref "C67") (pin "1") (pinfunction "1_1") (pintype "input"))
      (node (ref "C68") (pin "1") (pinfunction "1_1") (pintype "unspecified"))
      (node (ref "C69") (pin "1") (pinfunction "1_1") (pintype "input"))
      (node (ref "C7") (pin "1") (pinfunction "1_1") (pintype "unspecified"))
      (node (ref "C70") (pin "1") (pinfunction "1_1") (pintype "unspecified"))
      (node (ref "C71") (pin "1") (pinfunction "1_1") (pintype "input"))
      (node (ref "C72") (pin "1") (pinfunction "1_1") (pintype "unspecified"))
      (node (ref "C73") (pin "1") (pinfunction "1_1") (pintype "input"))
      (node (ref "C74") (pin "1") (pinfunction "1_1") (pintype "unspecified"))
      (node (ref "C75") (pin "1") (pinfunction "1_1") (pintype "input"))
      (node (ref "C76") (pin "1") (pinfunction "1_1") (pintype "unspecified"))
      (node (ref "C77") (pin "1") (pinfunction "1_1") (pintype "input"))
      (node (ref "C78") (pin "1") (pinfunction "1_1") (pintype "unspecified"))
      (node (ref "C79") (pin "1") (pinfunction "1_1") (pintype "input"))
      (node (ref "C8") (pin "1") (pinfunction "1_1") (pintype "input"))
      (node (ref "C80") (pin "1") (pinfunction "1_1") (pintype "unspecified"))
      (node (ref "C81") (pin "1") (pinfunction "1_1") (pintype "input"))
      (node (ref "C82") (pin "1") (pinfunction "1_1") (pintype "unspecified"))
      (node (ref "C83") (pin "1") (pinfunction "1_1") (pintype "input"))
      (node (ref "C84") (pin "1") (pinfunction "1_1") (pintype "unspecified"))
      (node (ref "C85") (pin "1") (pinfunction "1_1") (pintype "input"))
      (node (ref "C86") (pin "1") (pinfunction "1_1") (pintype "unspecified"))
      (node (ref "C87") (pin "1") (pinfunction "1_1") (pintype "input"))
      (node (ref "C88") (pin "1") (pinfunction "1_1") (pintype "unspecified"))
      (node (ref "C89") (pin "1") (pinfunction "1_1") (pintype "input"))
      (node (ref "C9") (pin "1") (pinfunction "1_1") (pintype "unspecified"))
      (node (ref "C90") (pin "1") (pinfunction "1_1") (pintype "unspecified"))
      (node (ref "C91") (pin "1") (pinfunction "1_1") (pintype "input"))
      (node (ref "C92") (pin "1") (pinfunction "1_1") (pintype "unspecified"))
      (node (ref "C93") (pin "1") (pinfunction "1_1") (pintype "input"))
      (node (ref "C94") (pin "1") (pinfunction "1_1") (pintype "unspecified"))
      (node (ref "C95") (pin "1") (pinfunction "1_1") (pintype "input"))
      (node (ref "C96") (pin "1") (pinfunction "1_1") (pintype "unspecified"))
      (node (ref "C97") (pin "1") (pinfunction "1_1") (pintype "unspecified"))
      (node (ref "C98") (pin "1") (pinfunction "1_1") (pintype "input"))
      (node (ref "C99") (pin "1") (pinfunction "1_1") (pintype "unspecified"))
      (node (ref "X10Y1") (pin "3") (pinfunction "GND_3") (pintype "unspecified"))
      (node (ref "X10Y10") (pin "3") (pinfunction "GND_3") (pintype "unspecified"))
      (node (ref "X10Y11") (pin "3") (pinfunction "GND_3") (pintype "unspecified"))
      (node (ref "X10Y12") (pin "3") (pinfunction "GND_3") (pintype "unspecified"))
      (node (ref "X10Y13") (pin "3") (pinfunction "GND_3") (pintype "unspecified"))
      (node (ref "X10Y14") (pin "3") (pinfunction "GND_3") (pintype "unspecified"))
      (node (ref "X10Y15") (pin "3") (pinfunction "GND_3") (pintype "unspecified"))
      (node (ref "X10Y16") (pin "3") (pinfunction "GND_3") (pintype "unspecified"))
      (node (ref "X10Y2") (pin "3") (pinfunction "GND_3") (pintype "unspecified"))
      (node (ref "X10Y3") (pin "3") (pinfunction "GND_3") (pintype "unspecified"))
      (node (ref "X10Y4") (pin "3") (pinfunction "GND_3") (pintype "unspecified"))
      (node (ref "X10Y5") (pin "3") (pinfunction "GND_3") (pintype "unspecified"))
      (node (ref "X10Y6") (pin "3") (pinfunction "GND_3") (pintype "unspecified"))
      (node (ref "X10Y7") (pin "3") (pinfunction "GND_3") (pintype "unspecified"))
      (node (ref "X10Y8") (pin "3") (pinfunction "GND_3") (pintype "unspecified"))
      (node (ref "X10Y9") (pin "3") (pinfunction "GND_3") (pintype "unspecified"))
      (node (ref "X11Y1") (pin "3") (pinfunction "GND_3") (pintype "unspecified"))
      (node (ref "X11Y10") (pin "3") (pinfunction "GND_3") (pintype "unspecified"))
      (node (ref "X11Y11") (pin "3") (pinfunction "GND_3") (pintype "unspecified"))
      (node (ref "X11Y12") (pin "3") (pinfunction "GND_3") (pintype "unspecified"))
      (node (ref "X11Y13") (pin "3") (pinfunction "GND_3") (pintype "unspecified"))
      (node (ref "X11Y14") (pin "3") (pinfunction "GND_3") (pintype "unspecified"))
      (node (ref "X11Y15") (pin "3") (pinfunction "GND_3") (pintype "unspecified"))
      (node (ref "X11Y16") (pin "3") (pinfunction "GND_3") (pintype "unspecified"))
      (node (ref "X11Y2") (pin "3") (pinfunction "GND_3") (pintype "unspecified"))
      (node (ref "X11Y3") (pin "3") (pinfunction "GND_3") (pintype "unspecified"))
      (node (ref "X11Y4") (pin "3") (pinfunction "GND_3") (pintype "unspecified"))
      (node (ref "X11Y5") (pin "3") (pinfunction "GND_3") (pintype "unspecified"))
      (node (ref "X11Y6") (pin "3") (pinfunction "GND_3") (pintype "unspecified"))
      (node (ref "X11Y7") (pin "3") (pinfunction "GND_3") (pintype "unspecified"))
      (node (ref "X11Y8") (pin "3") (pinfunction "GND_3") (pintype "unspecified"))
      (node (ref "X11Y9") (pin "3") (pinfunction "GND_3") (pintype "unspecified"))
      (node (ref "X12Y1") (pin "3") (pinfunction "GND_3") (pintype "unspecified"))
      (node (ref "X12Y10") (pin "3") (pinfunction "GND_3") (pintype "unspecified"))
      (node (ref "X12Y11") (pin "3") (pinfunction "GND_3") (pintype "unspecified"))
      (node (ref "X12Y12") (pin "3") (pinfunction "GND_3") (pintype "unspecified"))
      (node (ref "X12Y13") (pin "3") (pinfunction "GND_3") (pintype "unspecified"))
      (node (ref "X12Y14") (pin "3") (pinfunction "GND_3") (pintype "unspecified"))
      (node (ref "X12Y15") (pin "3") (pinfunction "GND_3") (pintype "unspecified"))
      (node (ref "X12Y16") (pin "3") (pinfunction "GND_3") (pintype "unspecified"))
      (node (ref "X12Y2") (pin "3") (pinfunction "GND_3") (pintype "unspecified"))
      (node (ref "X12Y3") (pin "3") (pinfunction "GND_3") (pintype "unspecified"))
      (node (ref "X12Y4") (pin "3") (pinfunction "GND_3") (pintype "unspecified"))
      (node (ref "X12Y5") (pin "3") (pinfunction "GND_3") (pintype "unspecified"))
      (node (ref "X12Y6") (pin "3") (pinfunction "GND_3") (pintype "unspecified"))
      (node (ref "X12Y7") (pin "3") (pinfunction "GND_3") (pintype "unspecified"))
      (node (ref "X12Y8") (pin "3") (pinfunction "GND_3") (pintype "unspecified"))
      (node (ref "X12Y9") (pin "3") (pinfunction "GND_3") (pintype "unspecified"))
      (node (ref "X13Y1") (pin "3") (pinfunction "GND_3") (pintype "unspecified"))
      (node (ref "X13Y10") (pin "3") (pinfunction "GND_3") (pintype "unspecified"))
      (node (ref "X13Y11") (pin "3") (pinfunction "GND_3") (pintype "unspecified"))
      (node (ref "X13Y12") (pin "3") (pinfunction "GND_3") (pintype "unspecified"))
      (node (ref "X13Y13") (pin "3") (pinfunction "GND_3") (pintype "unspecified"))
      (node (ref "X13Y14") (pin "3") (pinfunction "GND_3") (pintype "unspecified"))
      (node (ref "X13Y15") (pin "3") (pinfunction "GND_3") (pintype "unspecified"))
      (node (ref "X13Y16") (pin "3") (pinfunction "GND_3") (pintype "unspecified"))
      (node (ref "X13Y2") (pin "3") (pinfunction "GND_3") (pintype "unspecified"))
      (node (ref "X13Y3") (pin "3") (pinfunction "GND_3") (pintype "unspecified"))
      (node (ref "X13Y4") (pin "3") (pinfunction "GND_3") (pintype "unspecified"))
      (node (ref "X13Y5") (pin "3") (pinfunction "GND_3") (pintype "unspecified"))
      (node (ref "X13Y6") (pin "3") (pinfunction "GND_3") (pintype "unspecified"))
      (node (ref "X13Y7") (pin "3") (pinfunction "GND_3") (pintype "unspecified"))
      (node (ref "X13Y8") (pin "3") (pinfunction "GND_3") (pintype "unspecified"))
      (node (ref "X13Y9") (pin "3") (pinfunction "GND_3") (pintype "unspecified"))
      (node (ref "X14Y1") (pin "3") (pinfunction "GND_3") (pintype "unspecified"))
      (node (ref "X14Y10") (pin "3") (pinfunction "GND_3") (pintype "unspecified"))
      (node (ref "X14Y11") (pin "3") (pinfunction "GND_3") (pintype "unspecified"))
      (node (ref "X14Y12") (pin "3") (pinfunction "GND_3") (pintype "unspecified"))
      (node (ref "X14Y13") (pin "3") (pinfunction "GND_3") (pintype "unspecified"))
      (node (ref "X14Y14") (pin "3") (pinfunction "GND_3") (pintype "unspecified"))
      (node (ref "X14Y15") (pin "3") (pinfunction "GND_3") (pintype "unspecified"))
      (node (ref "X14Y16") (pin "3") (pinfunction "GND_3") (pintype "unspecified"))
      (node (ref "X14Y2") (pin "3") (pinfunction "GND_3") (pintype "unspecified"))
      (node (ref "X14Y3") (pin "3") (pinfunction "GND_3") (pintype "unspecified"))
      (node (ref "X14Y4") (pin "3") (pinfunction "GND_3") (pintype "unspecified"))
      (node (ref "X14Y5") (pin "3") (pinfunction "GND_3") (pintype "unspecified"))
      (node (ref "X14Y6") (pin "3") (pinfunction "GND_3") (pintype "unspecified"))
      (node (ref "X14Y7") (pin "3") (pinfunction "GND_3") (pintype "unspecified"))
      (node (ref "X14Y8") (pin "3") (pinfunction "GND_3") (pintype "unspecified"))
      (node (ref "X14Y9") (pin "3") (pinfunction "GND_3") (pintype "unspecified"))
      (node (ref "X15Y1") (pin "3") (pinfunction "GND_3") (pintype "unspecified"))
      (node (ref "X15Y10") (pin "3") (pinfunction "GND_3") (pintype "unspecified"))
      (node (ref "X15Y11") (pin "3") (pinfunction "GND_3") (pintype "unspecified"))
      (node (ref "X15Y12") (pin "3") (pinfunction "GND_3") (pintype "unspecified"))
      (node (ref "X15Y13") (pin "3") (pinfunction "GND_3") (pintype "unspecified"))
      (node (ref "X15Y14") (pin "3") (pinfunction "GND_3") (pintype "unspecified"))
      (node (ref "X15Y15") (pin "3") (pinfunction "GND_3") (pintype "unspecified"))
      (node (ref "X15Y16") (pin "3") (pinfunction "GND_3") (pintype "unspecified"))
      (node (ref "X15Y2") (pin "3") (pinfunction "GND_3") (pintype "unspecified"))
      (node (ref "X15Y3") (pin "3") (pinfunction "GND_3") (pintype "unspecified"))
      (node (ref "X15Y4") (pin "3") (pinfunction "GND_3") (pintype "unspecified"))
      (node (ref "X15Y5") (pin "3") (pinfunction "GND_3") (pintype "unspecified"))
      (node (ref "X15Y6") (pin "3") (pinfunction "GND_3") (pintype "unspecified"))
      (node (ref "X15Y7") (pin "3") (pinfunction "GND_3") (pintype "unspecified"))
      (node (ref "X15Y8") (pin "3") (pinfunction "GND_3") (pintype "unspecified"))
      (node (ref "X15Y9") (pin "3") (pinfunction "GND_3") (pintype "unspecified"))
      (node (ref "X16Y1") (pin "3") (pinfunction "GND_3") (pintype "unspecified"))
      (node (ref "X16Y10") (pin "3") (pinfunction "GND_3") (pintype "unspecified"))
      (node (ref "X16Y11") (pin "3") (pinfunction "GND_3") (pintype "unspecified"))
      (node (ref "X16Y12") (pin "3") (pinfunction "GND_3") (pintype "unspecified"))
      (node (ref "X16Y13") (pin "3") (pinfunction "GND_3") (pintype "unspecified"))
      (node (ref "X16Y14") (pin "3") (pinfunction "GND_3") (pintype "unspecified"))
      (node (ref "X16Y15") (pin "3") (pinfunction "GND_3") (pintype "unspecified"))
      (node (ref "X16Y16") (pin "3") (pinfunction "GND_3") (pintype "unspecified"))
      (node (ref "X16Y2") (pin "3") (pinfunction "GND_3") (pintype "unspecified"))
      (node (ref "X16Y3") (pin "3") (pinfunction "GND_3") (pintype "unspecified"))
      (node (ref "X16Y4") (pin "3") (pinfunction "GND_3") (pintype "unspecified"))
      (node (ref "X16Y5") (pin "3") (pinfunction "GND_3") (pintype "unspecified"))
      (node (ref "X16Y6") (pin "3") (pinfunction "GND_3") (pintype "unspecified"))
      (node (ref "X16Y7") (pin "3") (pinfunction "GND_3") (pintype "unspecified"))
      (node (ref "X16Y8") (pin "3") (pinfunction "GND_3") (pintype "unspecified"))
      (node (ref "X16Y9") (pin "3") (pinfunction "GND_3") (pintype "unspecified"))
      (node (ref "X1Y1") (pin "3") (pinfunction "GND_3") (pintype "unspecified"))
      (node (ref "X1Y10") (pin "3") (pinfunction "GND_3") (pintype "unspecified"))
      (node (ref "X1Y11") (pin "3") (pinfunction "GND_3") (pintype "unspecified"))
      (node (ref "X1Y12") (pin "3") (pinfunction "GND_3") (pintype "unspecified"))
      (node (ref "X1Y13") (pin "3") (pinfunction "GND_3") (pintype "unspecified"))
      (node (ref "X1Y14") (pin "3") (pinfunction "GND_3") (pintype "unspecified"))
      (node (ref "X1Y15") (pin "3") (pinfunction "GND_3") (pintype "unspecified"))
      (node (ref "X1Y16") (pin "3") (pinfunction "GND_3") (pintype "unspecified"))
      (node (ref "X1Y2") (pin "3") (pinfunction "GND_3") (pintype "unspecified"))
      (node (ref "X1Y3") (pin "3") (pinfunction "GND_3") (pintype "unspecified"))
      (node (ref "X1Y4") (pin "3") (pinfunction "GND_3") (pintype "unspecified"))
      (node (ref "X1Y5") (pin "3") (pinfunction "GND_3") (pintype "unspecified"))
      (node (ref "X1Y6") (pin "3") (pinfunction "GND_3") (pintype "unspecified"))
      (node (ref "X1Y7") (pin "3") (pinfunction "GND_3") (pintype "unspecified"))
      (node (ref "X1Y8") (pin "3") (pinfunction "GND_3") (pintype "unspecified"))
      (node (ref "X1Y9") (pin "3") (pinfunction "GND_3") (pintype "unspecified"))
      (node (ref "X2Y1") (pin "3") (pinfunction "GND_3") (pintype "unspecified"))
      (node (ref "X2Y10") (pin "3") (pinfunction "GND_3") (pintype "unspecified"))
      (node (ref "X2Y11") (pin "3") (pinfunction "GND_3") (pintype "unspecified"))
      (node (ref "X2Y12") (pin "3") (pinfunction "GND_3") (pintype "unspecified"))
      (node (ref "X2Y13") (pin "3") (pinfunction "GND_3") (pintype "unspecified"))
      (node (ref "X2Y14") (pin "3") (pinfunction "GND_3") (pintype "unspecified"))
      (node (ref "X2Y15") (pin "3") (pinfunction "GND_3") (pintype "unspecified"))
      (node (ref "X2Y16") (pin "3") (pinfunction "GND_3") (pintype "unspecified"))
      (node (ref "X2Y2") (pin "3") (pinfunction "GND_3") (pintype "unspecified"))
      (node (ref "X2Y3") (pin "3") (pinfunction "GND_3") (pintype "unspecified"))
      (node (ref "X2Y4") (pin "3") (pinfunction "GND_3") (pintype "unspecified"))
      (node (ref "X2Y5") (pin "3") (pinfunction "GND_3") (pintype "unspecified"))
      (node (ref "X2Y6") (pin "3") (pinfunction "GND_3") (pintype "unspecified"))
      (node (ref "X2Y7") (pin "3") (pinfunction "GND_3") (pintype "unspecified"))
      (node (ref "X2Y8") (pin "3") (pinfunction "GND_3") (pintype "unspecified"))
      (node (ref "X2Y9") (pin "3") (pinfunction "GND_3") (pintype "unspecified"))
      (node (ref "X3Y1") (pin "3") (pinfunction "GND_3") (pintype "unspecified"))
      (node (ref "X3Y10") (pin "3") (pinfunction "GND_3") (pintype "unspecified"))
      (node (ref "X3Y11") (pin "3") (pinfunction "GND_3") (pintype "unspecified"))
      (node (ref "X3Y12") (pin "3") (pinfunction "GND_3") (pintype "unspecified"))
      (node (ref "X3Y13") (pin "3") (pinfunction "GND_3") (pintype "unspecified"))
      (node (ref "X3Y14") (pin "3") (pinfunction "GND_3") (pintype "unspecified"))
      (node (ref "X3Y15") (pin "3") (pinfunction "GND_3") (pintype "unspecified"))
      (node (ref "X3Y16") (pin "3") (pinfunction "GND_3") (pintype "unspecified"))
      (node (ref "X3Y2") (pin "3") (pinfunction "GND_3") (pintype "unspecified"))
      (node (ref "X3Y3") (pin "3") (pinfunction "GND_3") (pintype "unspecified"))
      (node (ref "X3Y4") (pin "3") (pinfunction "GND_3") (pintype "unspecified"))
      (node (ref "X3Y5") (pin "3") (pinfunction "GND_3") (pintype "unspecified"))
      (node (ref "X3Y6") (pin "3") (pinfunction "GND_3") (pintype "unspecified"))
      (node (ref "X3Y7") (pin "3") (pinfunction "GND_3") (pintype "unspecified"))
      (node (ref "X3Y8") (pin "3") (pinfunction "GND_3") (pintype "unspecified"))
      (node (ref "X3Y9") (pin "3") (pinfunction "GND_3") (pintype "unspecified"))
      (node (ref "X4Y1") (pin "3") (pinfunction "GND_3") (pintype "unspecified"))
      (node (ref "X4Y10") (pin "3") (pinfunction "GND_3") (pintype "unspecified"))
      (node (ref "X4Y11") (pin "3") (pinfunction "GND_3") (pintype "unspecified"))
      (node (ref "X4Y12") (pin "3") (pinfunction "GND_3") (pintype "unspecified"))
      (node (ref "X4Y13") (pin "3") (pinfunction "GND_3") (pintype "unspecified"))
      (node (ref "X4Y14") (pin "3") (pinfunction "GND_3") (pintype "unspecified"))
      (node (ref "X4Y15") (pin "3") (pinfunction "GND_3") (pintype "unspecified"))
      (node (ref "X4Y16") (pin "3") (pinfunction "GND_3") (pintype "unspecified"))
      (node (ref "X4Y2") (pin "3") (pinfunction "GND_3") (pintype "unspecified"))
      (node (ref "X4Y3") (pin "3") (pinfunction "GND_3") (pintype "unspecified"))
      (node (ref "X4Y4") (pin "3") (pinfunction "GND_3") (pintype "unspecified"))
      (node (ref "X4Y5") (pin "3") (pinfunction "GND_3") (pintype "unspecified"))
      (node (ref "X4Y6") (pin "3") (pinfunction "GND_3") (pintype "unspecified"))
      (node (ref "X4Y7") (pin "3") (pinfunction "GND_3") (pintype "unspecified"))
      (node (ref "X4Y8") (pin "3") (pinfunction "GND_3") (pintype "unspecified"))
      (node (ref "X4Y9") (pin "3") (pinfunction "GND_3") (pintype "unspecified"))
      (node (ref "X5Y1") (pin "3") (pinfunction "GND_3") (pintype "unspecified"))
      (node (ref "X5Y10") (pin "3") (pinfunction "GND_3") (pintype "unspecified"))
      (node (ref "X5Y11") (pin "3") (pinfunction "GND_3") (pintype "unspecified"))
      (node (ref "X5Y12") (pin "3") (pinfunction "GND_3") (pintype "unspecified"))
      (node (ref "X5Y13") (pin "3") (pinfunction "GND_3") (pintype "unspecified"))
      (node (ref "X5Y14") (pin "3") (pinfunction "GND_3") (pintype "unspecified"))
      (node (ref "X5Y15") (pin "3") (pinfunction "GND_3") (pintype "unspecified"))
      (node (ref "X5Y16") (pin "3") (pinfunction "GND_3") (pintype "unspecified"))
      (node (ref "X5Y2") (pin "3") (pinfunction "GND_3") (pintype "unspecified"))
      (node (ref "X5Y3") (pin "3") (pinfunction "GND_3") (pintype "unspecified"))
      (node (ref "X5Y4") (pin "3") (pinfunction "GND_3") (pintype "unspecified"))
      (node (ref "X5Y5") (pin "3") (pinfunction "GND_3") (pintype "unspecified"))
      (node (ref "X5Y6") (pin "3") (pinfunction "GND_3") (pintype "unspecified"))
      (node (ref "X5Y7") (pin "3") (pinfunction "GND_3") (pintype "unspecified"))
      (node (ref "X5Y8") (pin "3") (pinfunction "GND_3") (pintype "unspecified"))
      (node (ref "X5Y9") (pin "3") (pinfunction "GND_3") (pintype "unspecified"))
      (node (ref "X6Y1") (pin "3") (pinfunction "GND_3") (pintype "unspecified"))
      (node (ref "X6Y10") (pin "3") (pinfunction "GND_3") (pintype "unspecified"))
      (node (ref "X6Y11") (pin "3") (pinfunction "GND_3") (pintype "unspecified"))
      (node (ref "X6Y12") (pin "3") (pinfunction "GND_3") (pintype "unspecified"))
      (node (ref "X6Y13") (pin "3") (pinfunction "GND_3") (pintype "unspecified"))
      (node (ref "X6Y14") (pin "3") (pinfunction "GND_3") (pintype "unspecified"))
      (node (ref "X6Y15") (pin "3") (pinfunction "GND_3") (pintype "unspecified"))
      (node (ref "X6Y16") (pin "3") (pinfunction "GND_3") (pintype "unspecified"))
      (node (ref "X6Y2") (pin "3") (pinfunction "GND_3") (pintype "unspecified"))
      (node (ref "X6Y3") (pin "3") (pinfunction "GND_3") (pintype "unspecified"))
      (node (ref "X6Y4") (pin "3") (pinfunction "GND_3") (pintype "unspecified"))
      (node (ref "X6Y5") (pin "3") (pinfunction "GND_3") (pintype "unspecified"))
      (node (ref "X6Y6") (pin "3") (pinfunction "GND_3") (pintype "unspecified"))
      (node (ref "X6Y7") (pin "3") (pinfunction "GND_3") (pintype "unspecified"))
      (node (ref "X6Y8") (pin "3") (pinfunction "GND_3") (pintype "unspecified"))
      (node (ref "X6Y9") (pin "3") (pinfunction "GND_3") (pintype "unspecified"))
      (node (ref "X7Y1") (pin "3") (pinfunction "GND_3") (pintype "unspecified"))
      (node (ref "X7Y10") (pin "3") (pinfunction "GND_3") (pintype "unspecified"))
      (node (ref "X7Y11") (pin "3") (pinfunction "GND_3") (pintype "unspecified"))
      (node (ref "X7Y12") (pin "3") (pinfunction "GND_3") (pintype "unspecified"))
      (node (ref "X7Y13") (pin "3") (pinfunction "GND_3") (pintype "unspecified"))
      (node (ref "X7Y14") (pin "3") (pinfunction "GND_3") (pintype "unspecified"))
      (node (ref "X7Y15") (pin "3") (pinfunction "GND_3") (pintype "unspecified"))
      (node (ref "X7Y16") (pin "3") (pinfunction "GND_3") (pintype "unspecified"))
      (node (ref "X7Y2") (pin "3") (pinfunction "GND_3") (pintype "unspecified"))
      (node (ref "X7Y3") (pin "3") (pinfunction "GND_3") (pintype "unspecified"))
      (node (ref "X7Y4") (pin "3") (pinfunction "GND_3") (pintype "unspecified"))
      (node (ref "X7Y5") (pin "3") (pinfunction "GND_3") (pintype "unspecified"))
      (node (ref "X7Y6") (pin "3") (pinfunction "GND_3") (pintype "unspecified"))
      (node (ref "X7Y7") (pin "3") (pinfunction "GND_3") (pintype "unspecified"))
      (node (ref "X7Y8") (pin "3") (pinfunction "GND_3") (pintype "unspecified"))
      (node (ref "X7Y9") (pin "3") (pinfunction "GND_3") (pintype "unspecified"))
      (node (ref "X8Y1") (pin "3") (pinfunction "GND_3") (pintype "unspecified"))
      (node (ref "X8Y10") (pin "3") (pinfunction "GND_3") (pintype "unspecified"))
      (node (ref "X8Y11") (pin "3") (pinfunction "GND_3") (pintype "unspecified"))
      (node (ref "X8Y12") (pin "3") (pinfunction "GND_3") (pintype "unspecified"))
      (node (ref "X8Y13") (pin "3") (pinfunction "GND_3") (pintype "unspecified"))
      (node (ref "X8Y14") (pin "3") (pinfunction "GND_3") (pintype "unspecified"))
      (node (ref "X8Y15") (pin "3") (pinfunction "GND_3") (pintype "unspecified"))
      (node (ref "X8Y16") (pin "3") (pinfunction "GND_3") (pintype "unspecified"))
      (node (ref "X8Y2") (pin "3") (pinfunction "GND_3") (pintype "unspecified"))
      (node (ref "X8Y3") (pin "3") (pinfunction "GND_3") (pintype "unspecified"))
      (node (ref "X8Y4") (pin "3") (pinfunction "GND_3") (pintype "unspecified"))
      (node (ref "X8Y5") (pin "3") (pinfunction "GND_3") (pintype "unspecified"))
      (node (ref "X8Y6") (pin "3") (pinfunction "GND_3") (pintype "unspecified"))
      (node (ref "X8Y7") (pin "3") (pinfunction "GND_3") (pintype "unspecified"))
      (node (ref "X8Y8") (pin "3") (pinfunction "GND_3") (pintype "unspecified"))
      (node (ref "X8Y9") (pin "3") (pinfunction "GND_3") (pintype "unspecified"))
      (node (ref "X9Y1") (pin "3") (pinfunction "GND_3") (pintype "unspecified"))
      (node (ref "X9Y10") (pin "3") (pinfunction "GND_3") (pintype "unspecified"))
      (node (ref "X9Y11") (pin "3") (pinfunction "GND_3") (pintype "unspecified"))
      (node (ref "X9Y12") (pin "3") (pinfunction "GND_3") (pintype "unspecified"))
      (node (ref "X9Y13") (pin "3") (pinfunction "GND_3") (pintype "unspecified"))
      (node (ref "X9Y14") (pin "3") (pinfunction "GND_3") (pintype "unspecified"))
      (node (ref "X9Y15") (pin "3") (pinfunction "GND_3") (pintype "unspecified"))
      (node (ref "X9Y16") (pin "3") (pinfunction "GND_3") (pintype "unspecified"))
      (node (ref "X9Y2") (pin "3") (pinfunction "GND_3") (pintype "unspecified"))
      (node (ref "X9Y3") (pin "3") (pinfunction "GND_3") (pintype "unspecified"))
      (node (ref "X9Y4") (pin "3") (pinfunction "GND_3") (pintype "unspecified"))
      (node (ref "X9Y5") (pin "3") (pinfunction "GND_3") (pintype "unspecified"))
      (node (ref "X9Y6") (pin "3") (pinfunction "GND_3") (pintype "unspecified"))
      (node (ref "X9Y7") (pin "3") (pinfunction "GND_3") (pintype "unspecified"))
      (node (ref "X9Y8") (pin "3") (pinfunction "GND_3") (pintype "unspecified"))
      (node (ref "X9Y9") (pin "3") (pinfunction "GND_3") (pintype "unspecified"))
    )
    (net (code "3") (name "X1Y1") (class "Default")
      (node (ref "C2") (pin "2") (pinfunction "2_2") (pintype "input"))
      (node (ref "X1Y1") (pin "2") (pinfunction "OUT_2") (pintype "unspecified"))
    )
    (net (code "4") (name "X1Y2") (class "Default")
      (node (ref "C4") (pin "2") (pinfunction "2_2") (pintype "input"))
      (node (ref "X1Y2") (pin "2") (pinfunction "OUT_2") (pintype "unspecified"))
    )
    (net (code "5") (name "X1Y3") (class "Default")
      (node (ref "C6") (pin "2") (pinfunction "2_2") (pintype "input"))
      (node (ref "X1Y3") (pin "2") (pinfunction "OUT_2") (pintype "unspecified"))
    )
    (net (code "6") (name "X1Y4") (class "Default")
      (node (ref "C8") (pin "2") (pinfunction "2_2") (pintype "input"))
      (node (ref "X1Y4") (pin "2") (pinfunction "OUT_2") (pintype "unspecified"))
    )
    (net (code "7") (name "X1Y5") (class "Default")
      (node (ref "C10") (pin "2") (pinfunction "2_2") (pintype "input"))
      (node (ref "X1Y5") (pin "2") (pinfunction "OUT_2") (pintype "unspecified"))
    )
    (net (code "8") (name "X1Y6") (class "Default")
      (node (ref "C12") (pin "2") (pinfunction "2_2") (pintype "input"))
      (node (ref "X1Y6") (pin "2") (pinfunction "OUT_2") (pintype "unspecified"))
    )
    (net (code "9") (name "X1Y7") (class "Default")
      (node (ref "C14") (pin "2") (pinfunction "2_2") (pintype "input"))
      (node (ref "X1Y7") (pin "2") (pinfunction "OUT_2") (pintype "unspecified"))
    )
    (net (code "10") (name "X1Y8") (class "Default")
      (node (ref "C16") (pin "2") (pinfunction "2_2") (pintype "input"))
      (node (ref "X1Y8") (pin "2") (pinfunction "OUT_2") (pintype "unspecified"))
    )
    (net (code "11") (name "X1Y9") (class "Default")
      (node (ref "C18") (pin "2") (pinfunction "2_2") (pintype "input"))
      (node (ref "X1Y9") (pin "2") (pinfunction "OUT_2") (pintype "unspecified"))
    )
    (net (code "12") (name "X1Y10") (class "Default")
      (node (ref "C20") (pin "2") (pinfunction "2_2") (pintype "input"))
      (node (ref "X1Y10") (pin "2") (pinfunction "OUT_2") (pintype "unspecified"))
    )
    (net (code "13") (name "X1Y11") (class "Default")
      (node (ref "C22") (pin "2") (pinfunction "2_2") (pintype "input"))
      (node (ref "X1Y11") (pin "2") (pinfunction "OUT_2") (pintype "unspecified"))
    )
    (net (code "14") (name "X1Y12") (class "Default")
      (node (ref "C24") (pin "2") (pinfunction "2_2") (pintype "input"))
      (node (ref "X1Y12") (pin "2") (pinfunction "OUT_2") (pintype "unspecified"))
    )
    (net (code "15") (name "X1Y13") (class "Default")
      (node (ref "C26") (pin "2") (pinfunction "2_2") (pintype "input"))
      (node (ref "X1Y13") (pin "2") (pinfunction "OUT_2") (pintype "unspecified"))
    )
    (net (code "16") (name "X1Y14") (class "Default")
      (node (ref "C28") (pin "2") (pinfunction "2_2") (pintype "input"))
      (node (ref "X1Y14") (pin "2") (pinfunction "OUT_2") (pintype "unspecified"))
    )
    (net (code "17") (name "X1Y15") (class "Default")
      (node (ref "C30") (pin "2") (pinfunction "2_2") (pintype "input"))
      (node (ref "X1Y15") (pin "2") (pinfunction "OUT_2") (pintype "unspecified"))
    )
    (net (code "18") (name "X1Y16") (class "Default")
      (node (ref "C32") (pin "2") (pinfunction "2_2") (pintype "input"))
      (node (ref "X1Y16") (pin "2") (pinfunction "OUT_2") (pintype "unspecified"))
    )
    (net (code "19") (name "X2Y1") (class "Default")
      (node (ref "C33") (pin "2") (pinfunction "2_2") (pintype "input"))
      (node (ref "X2Y1") (pin "2") (pinfunction "OUT_2") (pintype "unspecified"))
    )
    (net (code "20") (name "X2Y2") (class "Default")
      (node (ref "C36") (pin "2") (pinfunction "2_2") (pintype "input"))
      (node (ref "X2Y2") (pin "2") (pinfunction "OUT_2") (pintype "unspecified"))
    )
    (net (code "21") (name "X2Y3") (class "Default")
      (node (ref "C38") (pin "2") (pinfunction "2_2") (pintype "input"))
      (node (ref "X2Y3") (pin "2") (pinfunction "OUT_2") (pintype "unspecified"))
    )
    (net (code "22") (name "X2Y4") (class "Default")
      (node (ref "C40") (pin "2") (pinfunction "2_2") (pintype "input"))
      (node (ref "X2Y4") (pin "2") (pinfunction "OUT_2") (pintype "unspecified"))
    )
    (net (code "23") (name "X2Y5") (class "Default")
      (node (ref "C42") (pin "2") (pinfunction "2_2") (pintype "input"))
      (node (ref "X2Y5") (pin "2") (pinfunction "OUT_2") (pintype "unspecified"))
    )
    (net (code "24") (name "X2Y6") (class "Default")
      (node (ref "C44") (pin "2") (pinfunction "2_2") (pintype "input"))
      (node (ref "X2Y6") (pin "2") (pinfunction "OUT_2") (pintype "unspecified"))
    )
    (net (code "25") (name "X2Y7") (class "Default")
      (node (ref "C46") (pin "2") (pinfunction "2_2") (pintype "input"))
      (node (ref "X2Y7") (pin "2") (pinfunction "OUT_2") (pintype "unspecified"))
    )
    (net (code "26") (name "X2Y8") (class "Default")
      (node (ref "C48") (pin "2") (pinfunction "2_2") (pintype "input"))
      (node (ref "X2Y8") (pin "2") (pinfunction "OUT_2") (pintype "unspecified"))
    )
    (net (code "27") (name "X2Y9") (class "Default")
      (node (ref "C50") (pin "2") (pinfunction "2_2") (pintype "input"))
      (node (ref "X2Y9") (pin "2") (pinfunction "OUT_2") (pintype "unspecified"))
    )
    (net (code "28") (name "X2Y10") (class "Default")
      (node (ref "C52") (pin "2") (pinfunction "2_2") (pintype "input"))
      (node (ref "X2Y10") (pin "2") (pinfunction "OUT_2") (pintype "unspecified"))
    )
    (net (code "29") (name "X2Y11") (class "Default")
      (node (ref "C54") (pin "2") (pinfunction "2_2") (pintype "input"))
      (node (ref "X2Y11") (pin "2") (pinfunction "OUT_2") (pintype "unspecified"))
    )
    (net (code "30") (name "X2Y12") (class "Default")
      (node (ref "C56") (pin "2") (pinfunction "2_2") (pintype "input"))
      (node (ref "X2Y12") (pin "2") (pinfunction "OUT_2") (pintype "unspecified"))
    )
    (net (code "31") (name "X2Y13") (class "Default")
      (node (ref "C58") (pin "2") (pinfunction "2_2") (pintype "input"))
      (node (ref "X2Y13") (pin "2") (pinfunction "OUT_2") (pintype "unspecified"))
    )
    (net (code "32") (name "X2Y14") (class "Default")
      (node (ref "C60") (pin "2") (pinfunction "2_2") (pintype "input"))
      (node (ref "X2Y14") (pin "2") (pinfunction "OUT_2") (pintype "unspecified"))
    )
    (net (code "33") (name "X2Y15") (class "Default")
      (node (ref "C62") (pin "2") (pinfunction "2_2") (pintype "input"))
      (node (ref "X2Y15") (pin "2") (pinfunction "OUT_2") (pintype "unspecified"))
    )
    (net (code "34") (name "X2Y16") (class "Default")
      (node (ref "C64") (pin "2") (pinfunction "2_2") (pintype "input"))
      (node (ref "X2Y16") (pin "2") (pinfunction "OUT_2") (pintype "unspecified"))
    )
    (net (code "35") (name "X3Y1") (class "Default")
      (node (ref "C66") (pin "2") (pinfunction "2_2") (pintype "input"))
      (node (ref "X3Y1") (pin "2") (pinfunction "OUT_2") (pintype "unspecified"))
    )
    (net (code "36") (name "X3Y2") (class "Default")
      (node (ref "C67") (pin "2") (pinfunction "2_2") (pintype "input"))
      (node (ref "X3Y2") (pin "2") (pinfunction "OUT_2") (pintype "unspecified"))
    )
    (net (code "37") (name "X3Y3") (class "Default")
      (node (ref "C71") (pin "2") (pinfunction "2_2") (pintype "input"))
      (node (ref "X3Y4") (pin "2") (pinfunction "OUT_2") (pintype "unspecified"))
    )
    (net (code "38") (name "X3Y4") (class "Default")
      (node (ref "C69") (pin "2") (pinfunction "2_2") (pintype "input"))
      (node (ref "X3Y3") (pin "2") (pinfunction "OUT_2") (pintype "unspecified"))
    )
    (net (code "39") (name "X3Y5") (class "Default")
      (node (ref "C73") (pin "2") (pinfunction "2_2") (pintype "input"))
      (node (ref "X3Y5") (pin "2") (pinfunction "OUT_2") (pintype "unspecified"))
    )
    (net (code "40") (name "X3Y6") (class "Default")
      (node (ref "C75") (pin "2") (pinfunction "2_2") (pintype "input"))
      (node (ref "X3Y6") (pin "2") (pinfunction "OUT_2") (pintype "unspecified"))
    )
    (net (code "41") (name "X3Y7") (class "Default")
      (node (ref "C77") (pin "2") (pinfunction "2_2") (pintype "input"))
      (node (ref "X3Y7") (pin "2") (pinfunction "OUT_2") (pintype "unspecified"))
    )
    (net (code "42") (name "X3Y8") (class "Default")
      (node (ref "C79") (pin "2") (pinfunction "2_2") (pintype "input"))
      (node (ref "X3Y8") (pin "2") (pinfunction "OUT_2") (pintype "unspecified"))
    )
    (net (code "43") (name "X3Y9") (class "Default")
      (node (ref "C81") (pin "2") (pinfunction "2_2") (pintype "input"))
      (node (ref "X3Y9") (pin "2") (pinfunction "OUT_2") (pintype "unspecified"))
    )
    (net (code "44") (name "X3Y10") (class "Default")
      (node (ref "C83") (pin "2") (pinfunction "2_2") (pintype "input"))
      (node (ref "X3Y10") (pin "2") (pinfunction "OUT_2") (pintype "unspecified"))
    )
    (net (code "45") (name "X3Y11") (class "Default")
      (node (ref "C85") (pin "2") (pinfunction "2_2") (pintype "input"))
      (node (ref "X3Y11") (pin "2") (pinfunction "OUT_2") (pintype "unspecified"))
    )
    (net (code "46") (name "X3Y12") (class "Default")
      (node (ref "C87") (pin "2") (pinfunction "2_2") (pintype "input"))
      (node (ref "X3Y12") (pin "2") (pinfunction "OUT_2") (pintype "unspecified"))
    )
    (net (code "47") (name "X3Y13") (class "Default")
      (node (ref "C89") (pin "2") (pinfunction "2_2") (pintype "input"))
      (node (ref "X3Y13") (pin "2") (pinfunction "OUT_2") (pintype "unspecified"))
    )
    (net (code "48") (name "X3Y14") (class "Default")
      (node (ref "C91") (pin "2") (pinfunction "2_2") (pintype "input"))
      (node (ref "X3Y14") (pin "2") (pinfunction "OUT_2") (pintype "unspecified"))
    )
    (net (code "49") (name "X3Y15") (class "Default")
      (node (ref "C93") (pin "2") (pinfunction "2_2") (pintype "input"))
      (node (ref "X3Y15") (pin "2") (pinfunction "OUT_2") (pintype "unspecified"))
    )
    (net (code "50") (name "X3Y16") (class "Default")
      (node (ref "C95") (pin "2") (pinfunction "2_2") (pintype "input"))
      (node (ref "X3Y16") (pin "2") (pinfunction "OUT_2") (pintype "unspecified"))
    )
    (net (code "51") (name "X4Y1") (class "Default")
      (node (ref "C103") (pin "2") (pinfunction "2_2") (pintype "input"))
      (node (ref "X4Y1") (pin "2") (pinfunction "OUT_2") (pintype "unspecified"))
    )
    (net (code "52") (name "X4Y2") (class "Default")
      (node (ref "C98") (pin "2") (pinfunction "2_2") (pintype "input"))
      (node (ref "X4Y2") (pin "2") (pinfunction "OUT_2") (pintype "unspecified"))
    )
    (net (code "53") (name "X4Y3") (class "Default")
      (node (ref "C100") (pin "2") (pinfunction "2_2") (pintype "input"))
      (node (ref "X4Y3") (pin "2") (pinfunction "OUT_2") (pintype "unspecified"))
    )
    (net (code "54") (name "X4Y4") (class "Default")
      (node (ref "C102") (pin "2") (pinfunction "2_2") (pintype "input"))
      (node (ref "X4Y4") (pin "2") (pinfunction "OUT_2") (pintype "unspecified"))
    )
    (net (code "55") (name "X4Y5") (class "Default")
      (node (ref "C106") (pin "2") (pinfunction "2_2") (pintype "input"))
      (node (ref "X4Y5") (pin "2") (pinfunction "OUT_2") (pintype "unspecified"))
    )
    (net (code "56") (name "X4Y6") (class "Default")
      (node (ref "C108") (pin "2") (pinfunction "2_2") (pintype "input"))
      (node (ref "X4Y6") (pin "2") (pinfunction "OUT_2") (pintype "unspecified"))
    )
    (net (code "57") (name "X4Y7") (class "Default")
      (node (ref "C110") (pin "2") (pinfunction "2_2") (pintype "input"))
      (node (ref "X4Y7") (pin "2") (pinfunction "OUT_2") (pintype "unspecified"))
    )
    (net (code "58") (name "X4Y8") (class "Default")
      (node (ref "C112") (pin "2") (pinfunction "2_2") (pintype "input"))
      (node (ref "X4Y8") (pin "2") (pinfunction "OUT_2") (pintype "unspecified"))
    )
    (net (code "59") (name "X4Y9") (class "Default")
      (node (ref "C114") (pin "2") (pinfunction "2_2") (pintype "input"))
      (node (ref "X4Y9") (pin "2") (pinfunction "OUT_2") (pintype "unspecified"))
    )
    (net (code "60") (name "X4Y10") (class "Default")
      (node (ref "C116") (pin "2") (pinfunction "2_2") (pintype "input"))
      (node (ref "X4Y10") (pin "2") (pinfunction "OUT_2") (pintype "unspecified"))
    )
    (net (code "61") (name "X4Y11") (class "Default")
      (node (ref "C118") (pin "2") (pinfunction "2_2") (pintype "input"))
      (node (ref "X4Y11") (pin "2") (pinfunction "OUT_2") (pintype "unspecified"))
    )
    (net (code "62") (name "X4Y12") (class "Default")
      (node (ref "C120") (pin "2") (pinfunction "2_2") (pintype "input"))
      (node (ref "X4Y12") (pin "2") (pinfunction "OUT_2") (pintype "unspecified"))
    )
    (net (code "63") (name "X4Y13") (class "Default")
      (node (ref "C122") (pin "2") (pinfunction "2_2") (pintype "input"))
      (node (ref "X4Y13") (pin "2") (pinfunction "OUT_2") (pintype "unspecified"))
    )
    (net (code "64") (name "X4Y14") (class "Default")
      (node (ref "C124") (pin "2") (pinfunction "2_2") (pintype "input"))
      (node (ref "X4Y14") (pin "2") (pinfunction "OUT_2") (pintype "unspecified"))
    )
    (net (code "65") (name "X4Y15") (class "Default")
      (node (ref "C126") (pin "2") (pinfunction "2_2") (pintype "input"))
      (node (ref "X4Y15") (pin "2") (pinfunction "OUT_2") (pintype "unspecified"))
    )
    (net (code "66") (name "X4Y16") (class "Default")
      (node (ref "C128") (pin "2") (pinfunction "2_2") (pintype "input"))
      (node (ref "X4Y16") (pin "2") (pinfunction "OUT_2") (pintype "unspecified"))
    )
    (net (code "67") (name "X5Y1") (class "Default")
      (node (ref "C130") (pin "2") (pinfunction "2_2") (pintype "input"))
      (node (ref "X5Y1") (pin "2") (pinfunction "OUT_2") (pintype "unspecified"))
    )
    (net (code "68") (name "X5Y2") (class "Default")
      (node (ref "C131") (pin "2") (pinfunction "2_2") (pintype "input"))
      (node (ref "X5Y2") (pin "2") (pinfunction "OUT_2") (pintype "unspecified"))
    )
    (net (code "69") (name "X5Y3") (class "Default")
      (node (ref "C133") (pin "2") (pinfunction "2_2") (pintype "input"))
      (node (ref "X5Y3") (pin "2") (pinfunction "OUT_2") (pintype "unspecified"))
    )
    (net (code "70") (name "X5Y4") (class "Default")
      (node (ref "C135") (pin "2") (pinfunction "2_2") (pintype "input"))
      (node (ref "X5Y4") (pin "2") (pinfunction "OUT_2") (pintype "unspecified"))
    )
    (net (code "71") (name "X5Y5") (class "Default")
      (node (ref "C137") (pin "2") (pinfunction "2_2") (pintype "input"))
      (node (ref "X5Y5") (pin "2") (pinfunction "OUT_2") (pintype "unspecified"))
    )
    (net (code "72") (name "X5Y6") (class "Default")
      (node (ref "C139") (pin "2") (pinfunction "2_2") (pintype "input"))
      (node (ref "X5Y6") (pin "2") (pinfunction "OUT_2") (pintype "unspecified"))
    )
    (net (code "73") (name "X5Y7") (class "Default")
      (node (ref "C141") (pin "2") (pinfunction "2_2") (pintype "input"))
      (node (ref "X5Y7") (pin "2") (pinfunction "OUT_2") (pintype "unspecified"))
    )
    (net (code "74") (name "X5Y8") (class "Default")
      (node (ref "C143") (pin "2") (pinfunction "2_2") (pintype "input"))
      (node (ref "X5Y8") (pin "2") (pinfunction "OUT_2") (pintype "unspecified"))
    )
    (net (code "75") (name "X5Y9") (class "Default")
      (node (ref "C145") (pin "2") (pinfunction "2_2") (pintype "input"))
      (node (ref "X5Y9") (pin "2") (pinfunction "OUT_2") (pintype "unspecified"))
    )
    (net (code "76") (name "X5Y10") (class "Default")
      (node (ref "C147") (pin "2") (pinfunction "2_2") (pintype "input"))
      (node (ref "X5Y10") (pin "2") (pinfunction "OUT_2") (pintype "unspecified"))
    )
    (net (code "77") (name "X5Y11") (class "Default")
      (node (ref "C149") (pin "2") (pinfunction "2_2") (pintype "input"))
      (node (ref "X5Y11") (pin "2") (pinfunction "OUT_2") (pintype "unspecified"))
    )
    (net (code "78") (name "X5Y12") (class "Default")
      (node (ref "C151") (pin "2") (pinfunction "2_2") (pintype "input"))
      (node (ref "X5Y12") (pin "2") (pinfunction "OUT_2") (pintype "unspecified"))
    )
    (net (code "79") (name "X5Y13") (class "Default")
      (node (ref "C153") (pin "2") (pinfunction "2_2") (pintype "input"))
      (node (ref "X5Y13") (pin "2") (pinfunction "OUT_2") (pintype "unspecified"))
    )
    (net (code "80") (name "X5Y14") (class "Default")
      (node (ref "C155") (pin "2") (pinfunction "2_2") (pintype "input"))
      (node (ref "X5Y14") (pin "2") (pinfunction "OUT_2") (pintype "unspecified"))
    )
    (net (code "81") (name "X5Y15") (class "Default")
      (node (ref "C157") (pin "2") (pinfunction "2_2") (pintype "input"))
      (node (ref "X5Y15") (pin "2") (pinfunction "OUT_2") (pintype "unspecified"))
    )
    (net (code "82") (name "X5Y16") (class "Default")
      (node (ref "C159") (pin "2") (pinfunction "2_2") (pintype "input"))
      (node (ref "X5Y16") (pin "2") (pinfunction "OUT_2") (pintype "unspecified"))
    )
    (net (code "83") (name "X6Y1") (class "Default")
      (node (ref "C161") (pin "2") (pinfunction "2_2") (pintype "input"))
      (node (ref "X6Y1") (pin "2") (pinfunction "OUT_2") (pintype "unspecified"))
    )
    (net (code "84") (name "X6Y2") (class "Default")
      (node (ref "C163") (pin "2") (pinfunction "2_2") (pintype "input"))
      (node (ref "X6Y2") (pin "2") (pinfunction "OUT_2") (pintype "unspecified"))
    )
    (net (code "85") (name "X6Y3") (class "Default")
      (node (ref "C165") (pin "2") (pinfunction "2_2") (pintype "input"))
      (node (ref "X6Y3") (pin "2") (pinfunction "OUT_2") (pintype "unspecified"))
    )
    (net (code "86") (name "X6Y4") (class "Default")
      (node (ref "C167") (pin "2") (pinfunction "2_2") (pintype "input"))
      (node (ref "X6Y4") (pin "2") (pinfunction "OUT_2") (pintype "unspecified"))
    )
    (net (code "87") (name "X6Y5") (class "Default")
      (node (ref "C169") (pin "2") (pinfunction "2_2") (pintype "input"))
      (node (ref "X6Y5") (pin "2") (pinfunction "OUT_2") (pintype "unspecified"))
    )
    (net (code "88") (name "X6Y6") (class "Default")
      (node (ref "C171") (pin "2") (pinfunction "2_2") (pintype "input"))
      (node (ref "X6Y6") (pin "2") (pinfunction "OUT_2") (pintype "unspecified"))
    )
    (net (code "89") (name "X6Y7") (class "Default")
      (node (ref "C173") (pin "2") (pinfunction "2_2") (pintype "input"))
      (node (ref "X6Y7") (pin "2") (pinfunction "OUT_2") (pintype "unspecified"))
    )
    (net (code "90") (name "X6Y8") (class "Default")
      (node (ref "C175") (pin "2") (pinfunction "2_2") (pintype "input"))
      (node (ref "X6Y8") (pin "2") (pinfunction "OUT_2") (pintype "unspecified"))
    )
    (net (code "91") (name "X6Y9") (class "Default")
      (node (ref "C177") (pin "2") (pinfunction "2_2") (pintype "input"))
      (node (ref "X6Y9") (pin "2") (pinfunction "OUT_2") (pintype "unspecified"))
    )
    (net (code "92") (name "X6Y10") (class "Default")
      (node (ref "C179") (pin "2") (pinfunction "2_2") (pintype "input"))
      (node (ref "X6Y10") (pin "2") (pinfunction "OUT_2") (pintype "unspecified"))
    )
    (net (code "93") (name "X6Y11") (class "Default")
      (node (ref "C181") (pin "2") (pinfunction "2_2") (pintype "input"))
      (node (ref "X6Y11") (pin "2") (pinfunction "OUT_2") (pintype "unspecified"))
    )
    (net (code "94") (name "X6Y12") (class "Default")
      (node (ref "C183") (pin "2") (pinfunction "2_2") (pintype "input"))
      (node (ref "X6Y12") (pin "2") (pinfunction "OUT_2") (pintype "unspecified"))
    )
    (net (code "95") (name "X6Y13") (class "Default")
      (node (ref "C185") (pin "2") (pinfunction "2_2") (pintype "input"))
      (node (ref "X6Y13") (pin "2") (pinfunction "OUT_2") (pintype "unspecified"))
    )
    (net (code "96") (name "X6Y14") (class "Default")
      (node (ref "C187") (pin "2") (pinfunction "2_2") (pintype "input"))
      (node (ref "X6Y14") (pin "2") (pinfunction "OUT_2") (pintype "unspecified"))
    )
    (net (code "97") (name "X6Y15") (class "Default")
      (node (ref "C189") (pin "2") (pinfunction "2_2") (pintype "input"))
      (node (ref "X6Y15") (pin "2") (pinfunction "OUT_2") (pintype "unspecified"))
    )
    (net (code "98") (name "X6Y16") (class "Default")
      (node (ref "C191") (pin "2") (pinfunction "2_2") (pintype "input"))
      (node (ref "X6Y16") (pin "2") (pinfunction "OUT_2") (pintype "unspecified"))
    )
    (net (code "99") (name "X7Y1") (class "Default")
      (node (ref "C193") (pin "2") (pinfunction "2_2") (pintype "input"))
      (node (ref "X7Y1") (pin "2") (pinfunction "OUT_2") (pintype "unspecified"))
    )
    (net (code "100") (name "X7Y2") (class "Default")
      (node (ref "C196") (pin "2") (pinfunction "2_2") (pintype "input"))
      (node (ref "X7Y2") (pin "2") (pinfunction "OUT_2") (pintype "unspecified"))
    )
    (net (code "101") (name "X7Y3") (class "Default")
      (node (ref "C200") (pin "2") (pinfunction "2_2") (pintype "input"))
      (node (ref "X7Y4") (pin "2") (pinfunction "OUT_2") (pintype "unspecified"))
    )
    (net (code "102") (name "X7Y4") (class "Default")
      (node (ref "C198") (pin "2") (pinfunction "2_2") (pintype "input"))
      (node (ref "X7Y3") (pin "2") (pinfunction "OUT_2") (pintype "unspecified"))
    )
    (net (code "103") (name "X7Y5") (class "Default")
      (node (ref "C202") (pin "2") (pinfunction "2_2") (pintype "input"))
      (node (ref "X7Y5") (pin "2") (pinfunction "OUT_2") (pintype "unspecified"))
    )
    (net (code "104") (name "X7Y6") (class "Default")
      (node (ref "C204") (pin "2") (pinfunction "2_2") (pintype "input"))
      (node (ref "X7Y6") (pin "2") (pinfunction "OUT_2") (pintype "unspecified"))
    )
    (net (code "105") (name "X7Y7") (class "Default")
      (node (ref "C206") (pin "2") (pinfunction "2_2") (pintype "input"))
      (node (ref "X7Y7") (pin "2") (pinfunction "OUT_2") (pintype "unspecified"))
    )
    (net (code "106") (name "X7Y8") (class "Default")
      (node (ref "C208") (pin "2") (pinfunction "2_2") (pintype "input"))
      (node (ref "X7Y8") (pin "2") (pinfunction "OUT_2") (pintype "unspecified"))
    )
    (net (code "107") (name "X7Y9") (class "Default")
      (node (ref "C210") (pin "2") (pinfunction "2_2") (pintype "input"))
      (node (ref "X7Y9") (pin "2") (pinfunction "OUT_2") (pintype "unspecified"))
    )
    (net (code "108") (name "X7Y10") (class "Default")
      (node (ref "C212") (pin "2") (pinfunction "2_2") (pintype "input"))
      (node (ref "X7Y10") (pin "2") (pinfunction "OUT_2") (pintype "unspecified"))
    )
    (net (code "109") (name "X7Y11") (class "Default")
      (node (ref "C214") (pin "2") (pinfunction "2_2") (pintype "input"))
      (node (ref "X7Y11") (pin "2") (pinfunction "OUT_2") (pintype "unspecified"))
    )
    (net (code "110") (name "X7Y12") (class "Default")
      (node (ref "C216") (pin "2") (pinfunction "2_2") (pintype "input"))
      (node (ref "X7Y12") (pin "2") (pinfunction "OUT_2") (pintype "unspecified"))
    )
    (net (code "111") (name "X7Y13") (class "Default")
      (node (ref "C218") (pin "2") (pinfunction "2_2") (pintype "input"))
      (node (ref "X7Y13") (pin "2") (pinfunction "OUT_2") (pintype "unspecified"))
    )
    (net (code "112") (name "X7Y14") (class "Default")
      (node (ref "C220") (pin "2") (pinfunction "2_2") (pintype "input"))
      (node (ref "X7Y14") (pin "2") (pinfunction "OUT_2") (pintype "unspecified"))
    )
    (net (code "113") (name "X7Y15") (class "Default")
      (node (ref "C222") (pin "2") (pinfunction "2_2") (pintype "input"))
      (node (ref "X7Y15") (pin "2") (pinfunction "OUT_2") (pintype "unspecified"))
    )
    (net (code "114") (name "X7Y16") (class "Default")
      (node (ref "C224") (pin "2") (pinfunction "2_2") (pintype "input"))
      (node (ref "X7Y16") (pin "2") (pinfunction "OUT_2") (pintype "unspecified"))
    )
    (net (code "115") (name "X8Y1") (class "Default")
      (node (ref "C226") (pin "2") (pinfunction "2_2") (pintype "input"))
      (node (ref "X8Y1") (pin "2") (pinfunction "OUT_2") (pintype "unspecified"))
    )
    (net (code "116") (name "X8Y2") (class "Default")
      (node (ref "C227") (pin "2") (pinfunction "2_2") (pintype "input"))
      (node (ref "X8Y2") (pin "2") (pinfunction "OUT_2") (pintype "unspecified"))
    )
    (net (code "117") (name "X8Y3") (class "Default")
      (node (ref "C229") (pin "2") (pinfunction "2_2") (pintype "input"))
      (node (ref "X8Y3") (pin "2") (pinfunction "OUT_2") (pintype "unspecified"))
    )
    (net (code "118") (name "X8Y4") (class "Default")
      (node (ref "C231") (pin "2") (pinfunction "2_2") (pintype "input"))
      (node (ref "X8Y4") (pin "2") (pinfunction "OUT_2") (pintype "unspecified"))
    )
    (net (code "119") (name "X8Y5") (class "Default")
      (node (ref "C233") (pin "2") (pinfunction "2_2") (pintype "input"))
      (node (ref "X8Y5") (pin "2") (pinfunction "OUT_2") (pintype "unspecified"))
    )
    (net (code "120") (name "X8Y6") (class "Default")
      (node (ref "C235") (pin "2") (pinfunction "2_2") (pintype "input"))
      (node (ref "X8Y6") (pin "2") (pinfunction "OUT_2") (pintype "unspecified"))
    )
    (net (code "121") (name "X8Y7") (class "Default")
      (node (ref "C237") (pin "2") (pinfunction "2_2") (pintype "input"))
      (node (ref "X8Y7") (pin "2") (pinfunction "OUT_2") (pintype "unspecified"))
    )
    (net (code "122") (name "X8Y8") (class "Default")
      (node (ref "C239") (pin "2") (pinfunction "2_2") (pintype "input"))
      (node (ref "X8Y8") (pin "2") (pinfunction "OUT_2") (pintype "unspecified"))
    )
    (net (code "123") (name "X8Y9") (class "Default")
      (node (ref "C241") (pin "2") (pinfunction "2_2") (pintype "input"))
      (node (ref "X8Y9") (pin "2") (pinfunction "OUT_2") (pintype "unspecified"))
    )
    (net (code "124") (name "X8Y10") (class "Default")
      (node (ref "C243") (pin "2") (pinfunction "2_2") (pintype "input"))
      (node (ref "X8Y10") (pin "2") (pinfunction "OUT_2") (pintype "unspecified"))
    )
    (net (code "125") (name "X8Y11") (class "Default")
      (node (ref "C245") (pin "2") (pinfunction "2_2") (pintype "input"))
      (node (ref "X8Y11") (pin "2") (pinfunction "OUT_2") (pintype "unspecified"))
    )
    (net (code "126") (name "X8Y12") (class "Default")
      (node (ref "C247") (pin "2") (pinfunction "2_2") (pintype "input"))
      (node (ref "X8Y12") (pin "2") (pinfunction "OUT_2") (pintype "unspecified"))
    )
    (net (code "127") (name "X8Y13") (class "Default")
      (node (ref "C249") (pin "2") (pinfunction "2_2") (pintype "input"))
      (node (ref "X8Y13") (pin "2") (pinfunction "OUT_2") (pintype "unspecified"))
    )
    (net (code "128") (name "X8Y14") (class "Default")
      (node (ref "C251") (pin "2") (pinfunction "2_2") (pintype "input"))
      (node (ref "X8Y14") (pin "2") (pinfunction "OUT_2") (pintype "unspecified"))
    )
    (net (code "129") (name "X8Y15") (class "Default")
      (node (ref "C253") (pin "2") (pinfunction "2_2") (pintype "input"))
      (node (ref "X8Y15") (pin "2") (pinfunction "OUT_2") (pintype "unspecified"))
    )
    (net (code "130") (name "X8Y16") (class "Default")
      (node (ref "C255") (pin "2") (pinfunction "2_2") (pintype "input"))
      (node (ref "X8Y16") (pin "2") (pinfunction "OUT_2") (pintype "unspecified"))
    )
    (net (code "131") (name "X9Y1") (class "Default")
      (node (ref "C257") (pin "2") (pinfunction "2_2") (pintype "input"))
      (node (ref "X9Y1") (pin "2") (pinfunction "OUT_2") (pintype "unspecified"))
    )
    (net (code "132") (name "X9Y2") (class "Default")
      (node (ref "C260") (pin "2") (pinfunction "2_2") (pintype "input"))
      (node (ref "X9Y2") (pin "2") (pinfunction "OUT_2") (pintype "unspecified"))
    )
    (net (code "133") (name "X9Y3") (class "Default")
      (node (ref "C262") (pin "2") (pinfunction "2_2") (pintype "input"))
      (node (ref "X9Y3") (pin "2") (pinfunction "OUT_2") (pintype "unspecified"))
    )
    (net (code "134") (name "X9Y4") (class "Default")
      (node (ref "C264") (pin "2") (pinfunction "2_2") (pintype "input"))
      (node (ref "X9Y4") (pin "2") (pinfunction "OUT_2") (pintype "unspecified"))
    )
    (net (code "135") (name "X9Y5") (class "Default")
      (node (ref "C266") (pin "2") (pinfunction "2_2") (pintype "input"))
      (node (ref "X9Y5") (pin "2") (pinfunction "OUT_2") (pintype "unspecified"))
    )
    (net (code "136") (name "X9Y6") (class "Default")
      (node (ref "C268") (pin "2") (pinfunction "2_2") (pintype "input"))
      (node (ref "X9Y6") (pin "2") (pinfunction "OUT_2") (pintype "unspecified"))
    )
    (net (code "137") (name "X9Y7") (class "Default")
      (node (ref "C270") (pin "2") (pinfunction "2_2") (pintype "input"))
      (node (ref "X9Y7") (pin "2") (pinfunction "OUT_2") (pintype "unspecified"))
    )
    (net (code "138") (name "X9Y8") (class "Default")
      (node (ref "C272") (pin "2") (pinfunction "2_2") (pintype "input"))
      (node (ref "X9Y8") (pin "2") (pinfunction "OUT_2") (pintype "unspecified"))
    )
    (net (code "139") (name "X9Y9") (class "Default")
      (node (ref "C274") (pin "2") (pinfunction "2_2") (pintype "input"))
      (node (ref "X9Y9") (pin "2") (pinfunction "OUT_2") (pintype "unspecified"))
    )
    (net (code "140") (name "X9Y10") (class "Default")
      (node (ref "C278") (pin "2") (pinfunction "2_2") (pintype "input"))
      (node (ref "X9Y10") (pin "2") (pinfunction "OUT_2") (pintype "unspecified"))
    )
    (net (code "141") (name "X9Y11") (class "Default")
      (node (ref "C276") (pin "2") (pinfunction "2_2") (pintype "input"))
      (node (ref "X9Y11") (pin "2") (pinfunction "OUT_2") (pintype "unspecified"))
    )
    (net (code "142") (name "X9Y12") (class "Default")
      (node (ref "C280") (pin "2") (pinfunction "2_2") (pintype "input"))
      (node (ref "X9Y12") (pin "2") (pinfunction "OUT_2") (pintype "unspecified"))
    )
    (net (code "143") (name "X9Y13") (class "Default")
      (node (ref "C282") (pin "2") (pinfunction "2_2") (pintype "input"))
      (node (ref "X9Y13") (pin "2") (pinfunction "OUT_2") (pintype "unspecified"))
    )
    (net (code "144") (name "X9Y14") (class "Default")
      (node (ref "C284") (pin "2") (pinfunction "2_2") (pintype "input"))
      (node (ref "X9Y14") (pin "2") (pinfunction "OUT_2") (pintype "unspecified"))
    )
    (net (code "145") (name "X9Y15") (class "Default")
      (node (ref "C286") (pin "2") (pinfunction "2_2") (pintype "input"))
      (node (ref "X9Y15") (pin "2") (pinfunction "OUT_2") (pintype "unspecified"))
    )
    (net (code "146") (name "X9Y16") (class "Default")
      (node (ref "C288") (pin "2") (pinfunction "2_2") (pintype "input"))
      (node (ref "X9Y16") (pin "2") (pinfunction "OUT_2") (pintype "unspecified"))
    )
    (net (code "147") (name "X10Y1") (class "Default")
      (node (ref "C290") (pin "2") (pinfunction "2_2") (pintype "input"))
      (node (ref "X10Y1") (pin "2") (pinfunction "OUT_2") (pintype "unspecified"))
    )
    (net (code "148") (name "X10Y2") (class "Default")
      (node (ref "C291") (pin "2") (pinfunction "2_2") (pintype "input"))
      (node (ref "X10Y2") (pin "2") (pinfunction "OUT_2") (pintype "unspecified"))
    )
    (net (code "149") (name "X10Y3") (class "Default")
      (node (ref "C293") (pin "2") (pinfunction "2_2") (pintype "input"))
      (node (ref "X10Y3") (pin "2") (pinfunction "OUT_2") (pintype "unspecified"))
    )
    (net (code "150") (name "X10Y4") (class "Default")
      (node (ref "C295") (pin "2") (pinfunction "2_2") (pintype "input"))
      (node (ref "X10Y4") (pin "2") (pinfunction "OUT_2") (pintype "unspecified"))
    )
    (net (code "151") (name "X10Y5") (class "Default")
      (node (ref "C297") (pin "2") (pinfunction "2_2") (pintype "input"))
      (node (ref "X10Y5") (pin "2") (pinfunction "OUT_2") (pintype "unspecified"))
    )
    (net (code "152") (name "X10Y6") (class "Default")
      (node (ref "C299") (pin "2") (pinfunction "2_2") (pintype "input"))
      (node (ref "X10Y6") (pin "2") (pinfunction "OUT_2") (pintype "unspecified"))
    )
    (net (code "153") (name "X10Y7") (class "Default")
      (node (ref "C301") (pin "2") (pinfunction "2_2") (pintype "input"))
      (node (ref "X10Y7") (pin "2") (pinfunction "OUT_2") (pintype "unspecified"))
    )
    (net (code "154") (name "X10Y8") (class "Default")
      (node (ref "C303") (pin "2") (pinfunction "2_2") (pintype "input"))
      (node (ref "X10Y8") (pin "2") (pinfunction "OUT_2") (pintype "unspecified"))
    )
    (net (code "155") (name "X10Y9") (class "Default")
      (node (ref "C305") (pin "2") (pinfunction "2_2") (pintype "input"))
      (node (ref "X10Y9") (pin "2") (pinfunction "OUT_2") (pintype "unspecified"))
    )
    (net (code "156") (name "X10Y10") (class "Default")
      (node (ref "C307") (pin "2") (pinfunction "2_2") (pintype "input"))
      (node (ref "X10Y10") (pin "2") (pinfunction "OUT_2") (pintype "unspecified"))
    )
    (net (code "157") (name "X10Y11") (class "Default")
      (node (ref "C309") (pin "2") (pinfunction "2_2") (pintype "input"))
      (node (ref "X10Y11") (pin "2") (pinfunction "OUT_2") (pintype "unspecified"))
    )
    (net (code "158") (name "X10Y12") (class "Default")
      (node (ref "C311") (pin "2") (pinfunction "2_2") (pintype "input"))
      (node (ref "X10Y12") (pin "2") (pinfunction "OUT_2") (pintype "unspecified"))
    )
    (net (code "159") (name "X10Y13") (class "Default")
      (node (ref "C313") (pin "2") (pinfunction "2_2") (pintype "input"))
      (node (ref "X10Y13") (pin "2") (pinfunction "OUT_2") (pintype "unspecified"))
    )
    (net (code "160") (name "X10Y14") (class "Default")
      (node (ref "C315") (pin "2") (pinfunction "2_2") (pintype "input"))
      (node (ref "X10Y14") (pin "2") (pinfunction "OUT_2") (pintype "unspecified"))
    )
    (net (code "161") (name "X10Y15") (class "Default")
      (node (ref "C317") (pin "2") (pinfunction "2_2") (pintype "input"))
      (node (ref "X10Y15") (pin "2") (pinfunction "OUT_2") (pintype "unspecified"))
    )
    (net (code "162") (name "X10Y16") (class "Default")
      (node (ref "C319") (pin "2") (pinfunction "2_2") (pintype "input"))
      (node (ref "X10Y16") (pin "2") (pinfunction "OUT_2") (pintype "unspecified"))
    )
    (net (code "163") (name "X11Y1") (class "Default")
      (node (ref "C321") (pin "2") (pinfunction "2_2") (pintype "input"))
      (node (ref "X11Y1") (pin "2") (pinfunction "OUT_2") (pintype "unspecified"))
    )
    (net (code "164") (name "X11Y2") (class "Default")
      (node (ref "C324") (pin "2") (pinfunction "2_2") (pintype "input"))
      (node (ref "X11Y2") (pin "2") (pinfunction "OUT_2") (pintype "unspecified"))
    )
    (net (code "165") (name "X11Y3") (class "Default")
      (node (ref "C326") (pin "2") (pinfunction "2_2") (pintype "input"))
      (node (ref "X11Y3") (pin "2") (pinfunction "OUT_2") (pintype "unspecified"))
    )
    (net (code "166") (name "X11Y4") (class "Default")
      (node (ref "C328") (pin "2") (pinfunction "2_2") (pintype "input"))
      (node (ref "X11Y4") (pin "2") (pinfunction "OUT_2") (pintype "unspecified"))
    )
    (net (code "167") (name "X11Y5") (class "Default")
      (node (ref "C330") (pin "2") (pinfunction "2_2") (pintype "input"))
      (node (ref "X11Y5") (pin "2") (pinfunction "OUT_2") (pintype "unspecified"))
    )
    (net (code "168") (name "X11Y6") (class "Default")
      (node (ref "C332") (pin "2") (pinfunction "2_2") (pintype "input"))
      (node (ref "X11Y6") (pin "2") (pinfunction "OUT_2") (pintype "unspecified"))
    )
    (net (code "169") (name "X11Y7") (class "Default")
      (node (ref "C334") (pin "2") (pinfunction "2_2") (pintype "input"))
      (node (ref "X11Y7") (pin "2") (pinfunction "OUT_2") (pintype "unspecified"))
    )
    (net (code "170") (name "X11Y8") (class "Default")
      (node (ref "C336") (pin "2") (pinfunction "2_2") (pintype "input"))
      (node (ref "X11Y8") (pin "2") (pinfunction "OUT_2") (pintype "unspecified"))
    )
    (net (code "171") (name "X11Y9") (class "Default")
      (node (ref "C338") (pin "2") (pinfunction "2_2") (pintype "input"))
      (node (ref "X11Y9") (pin "2") (pinfunction "OUT_2") (pintype "unspecified"))
    )
    (net (code "172") (name "X11Y10") (class "Default")
      (node (ref "C340") (pin "2") (pinfunction "2_2") (pintype "input"))
      (node (ref "X11Y10") (pin "2") (pinfunction "OUT_2") (pintype "unspecified"))
    )
    (net (code "173") (name "X11Y11") (class "Default")
      (node (ref "C342") (pin "2") (pinfunction "2_2") (pintype "input"))
      (node (ref "X11Y11") (pin "2") (pinfunction "OUT_2") (pintype "unspecified"))
    )
    (net (code "174") (name "X11Y12") (class "Default")
      (node (ref "C344") (pin "2") (pinfunction "2_2") (pintype "input"))
      (node (ref "X11Y12") (pin "2") (pinfunction "OUT_2") (pintype "unspecified"))
    )
    (net (code "175") (name "X11Y13") (class "Default")
      (node (ref "C346") (pin "2") (pinfunction "2_2") (pintype "input"))
      (node (ref "X11Y13") (pin "2") (pinfunction "OUT_2") (pintype "unspecified"))
    )
    (net (code "176") (name "X11Y14") (class "Default")
      (node (ref "C348") (pin "2") (pinfunction "2_2") (pintype "input"))
      (node (ref "X11Y14") (pin "2") (pinfunction "OUT_2") (pintype "unspecified"))
    )
    (net (code "177") (name "X11Y15") (class "Default")
      (node (ref "C350") (pin "2") (pinfunction "2_2") (pintype "input"))
      (node (ref "X11Y15") (pin "2") (pinfunction "OUT_2") (pintype "unspecified"))
    )
    (net (code "178") (name "X11Y16") (class "Default")
      (node (ref "C352") (pin "2") (pinfunction "2_2") (pintype "input"))
      (node (ref "X11Y16") (pin "2") (pinfunction "OUT_2") (pintype "unspecified"))
    )
    (net (code "179") (name "X12Y1") (class "Default")
      (node (ref "C354") (pin "2") (pinfunction "2_2") (pintype "input"))
      (node (ref "X12Y1") (pin "2") (pinfunction "OUT_2") (pintype "unspecified"))
    )
    (net (code "180") (name "X12Y2") (class "Default")
      (node (ref "C355") (pin "2") (pinfunction "2_2") (pintype "input"))
      (node (ref "X12Y2") (pin "2") (pinfunction "OUT_2") (pintype "unspecified"))
    )
    (net (code "181") (name "X12Y3") (class "Default")
      (node (ref "C357") (pin "2") (pinfunction "2_2") (pintype "input"))
      (node (ref "X12Y3") (pin "2") (pinfunction "OUT_2") (pintype "unspecified"))
    )
    (net (code "182") (name "X12Y4") (class "Default")
      (node (ref "C359") (pin "2") (pinfunction "2_2") (pintype "input"))
      (node (ref "X12Y4") (pin "2") (pinfunction "OUT_2") (pintype "unspecified"))
    )
    (net (code "183") (name "X12Y5") (class "Default")
      (node (ref "C361") (pin "2") (pinfunction "2_2") (pintype "input"))
      (node (ref "X12Y5") (pin "2") (pinfunction "OUT_2") (pintype "unspecified"))
    )
    (net (code "184") (name "X12Y6") (class "Default")
      (node (ref "C363") (pin "2") (pinfunction "2_2") (pintype "input"))
      (node (ref "X12Y6") (pin "2") (pinfunction "OUT_2") (pintype "unspecified"))
    )
    (net (code "185") (name "X12Y7") (class "Default")
      (node (ref "C365") (pin "2") (pinfunction "2_2") (pintype "input"))
      (node (ref "X12Y7") (pin "2") (pinfunction "OUT_2") (pintype "unspecified"))
    )
    (net (code "186") (name "X12Y8") (class "Default")
      (node (ref "C367") (pin "2") (pinfunction "2_2") (pintype "input"))
      (node (ref "X12Y8") (pin "2") (pinfunction "OUT_2") (pintype "unspecified"))
    )
    (net (code "187") (name "X12Y9") (class "Default")
      (node (ref "C369") (pin "2") (pinfunction "2_2") (pintype "input"))
      (node (ref "X12Y9") (pin "2") (pinfunction "OUT_2") (pintype "unspecified"))
    )
    (net (code "188") (name "X12Y10") (class "Default")
      (node (ref "C371") (pin "2") (pinfunction "2_2") (pintype "input"))
      (node (ref "X12Y10") (pin "2") (pinfunction "OUT_2") (pintype "unspecified"))
    )
    (net (code "189") (name "X12Y11") (class "Default")
      (node (ref "C373") (pin "2") (pinfunction "2_2") (pintype "input"))
      (node (ref "X12Y11") (pin "2") (pinfunction "OUT_2") (pintype "unspecified"))
    )
    (net (code "190") (name "X12Y12") (class "Default")
      (node (ref "C375") (pin "2") (pinfunction "2_2") (pintype "input"))
      (node (ref "X12Y12") (pin "2") (pinfunction "OUT_2") (pintype "unspecified"))
    )
    (net (code "191") (name "X12Y13") (class "Default")
      (node (ref "C377") (pin "2") (pinfunction "2_2") (pintype "input"))
      (node (ref "X12Y13") (pin "2") (pinfunction "OUT_2") (pintype "unspecified"))
    )
    (net (code "192") (name "X12Y14") (class "Default")
      (node (ref "C379") (pin "2") (pinfunction "2_2") (pintype "input"))
      (node (ref "X12Y14") (pin "2") (pinfunction "OUT_2") (pintype "unspecified"))
    )
    (net (code "193") (name "X12Y15") (class "Default")
      (node (ref "C381") (pin "2") (pinfunction "2_2") (pintype "input"))
      (node (ref "X12Y15") (pin "2") (pinfunction "OUT_2") (pintype "unspecified"))
    )
    (net (code "194") (name "X12Y16") (class "Default")
      (node (ref "C383") (pin "2") (pinfunction "2_2") (pintype "input"))
      (node (ref "X12Y16") (pin "2") (pinfunction "OUT_2") (pintype "unspecified"))
    )
    (net (code "195") (name "X13Y1") (class "Default")
      (node (ref "C385") (pin "2") (pinfunction "2_2") (pintype "input"))
      (node (ref "X13Y1") (pin "2") (pinfunction "OUT_2") (pintype "unspecified"))
    )
    (net (code "196") (name "X13Y2") (class "Default")
      (node (ref "C388") (pin "2") (pinfunction "2_2") (pintype "input"))
      (node (ref "X13Y2") (pin "2") (pinfunction "OUT_2") (pintype "unspecified"))
    )
    (net (code "197") (name "X13Y3") (class "Default")
      (node (ref "C390") (pin "2") (pinfunction "2_2") (pintype "input"))
      (node (ref "X13Y3") (pin "2") (pinfunction "OUT_2") (pintype "unspecified"))
    )
    (net (code "198") (name "X13Y4") (class "Default")
      (node (ref "C392") (pin "2") (pinfunction "2_2") (pintype "input"))
      (node (ref "X13Y4") (pin "2") (pinfunction "OUT_2") (pintype "unspecified"))
    )
    (net (code "199") (name "X13Y5") (class "Default")
      (node (ref "C394") (pin "2") (pinfunction "2_2") (pintype "input"))
      (node (ref "X13Y5") (pin "2") (pinfunction "OUT_2") (pintype "unspecified"))
    )
    (net (code "200") (name "X13Y6") (class "Default")
      (node (ref "C396") (pin "2") (pinfunction "2_2") (pintype "input"))
      (node (ref "X13Y6") (pin "2") (pinfunction "OUT_2") (pintype "unspecified"))
    )
    (net (code "201") (name "X13Y7") (class "Default")
      (node (ref "C398") (pin "2") (pinfunction "2_2") (pintype "input"))
      (node (ref "X13Y7") (pin "2") (pinfunction "OUT_2") (pintype "unspecified"))
    )
    (net (code "202") (name "X13Y8") (class "Default")
      (node (ref "C400") (pin "2") (pinfunction "2_2") (pintype "input"))
      (node (ref "X13Y8") (pin "2") (pinfunction "OUT_2") (pintype "unspecified"))
    )
    (net (code "203") (name "X13Y9") (class "Default")
      (node (ref "C402") (pin "2") (pinfunction "2_2") (pintype "input"))
      (node (ref "X13Y9") (pin "2") (pinfunction "OUT_2") (pintype "unspecified"))
    )
    (net (code "204") (name "X13Y10") (class "Default")
      (node (ref "C404") (pin "2") (pinfunction "2_2") (pintype "input"))
      (node (ref "X13Y10") (pin "2") (pinfunction "OUT_2") (pintype "unspecified"))
    )
    (net (code "205") (name "X13Y11") (class "Default")
      (node (ref "C406") (pin "2") (pinfunction "2_2") (pintype "input"))
      (node (ref "X13Y11") (pin "2") (pinfunction "OUT_2") (pintype "unspecified"))
    )
    (net (code "206") (name "X13Y12") (class "Default")
      (node (ref "C408") (pin "2") (pinfunction "2_2") (pintype "input"))
      (node (ref "X13Y12") (pin "2") (pinfunction "OUT_2") (pintype "unspecified"))
    )
    (net (code "207") (name "X13Y13") (class "Default")
      (node (ref "C410") (pin "2") (pinfunction "2_2") (pintype "input"))
      (node (ref "X13Y13") (pin "2") (pinfunction "OUT_2") (pintype "unspecified"))
    )
    (net (code "208") (name "X13Y14") (class "Default")
      (node (ref "C412") (pin "2") (pinfunction "2_2") (pintype "input"))
      (node (ref "X13Y14") (pin "2") (pinfunction "OUT_2") (pintype "unspecified"))
    )
    (net (code "209") (name "X13Y15") (class "Default")
      (node (ref "C414") (pin "2") (pinfunction "2_2") (pintype "input"))
      (node (ref "X13Y15") (pin "2") (pinfunction "OUT_2") (pintype "unspecified"))
    )
    (net (code "210") (name "X13Y16") (class "Default")
      (node (ref "C416") (pin "2") (pinfunction "2_2") (pintype "input"))
      (node (ref "X13Y16") (pin "2") (pinfunction "OUT_2") (pintype "unspecified"))
    )
    (net (code "211") (name "X14Y1") (class "Default")
      (node (ref "C418") (pin "2") (pinfunction "2_2") (pintype "input"))
      (node (ref "X14Y1") (pin "2") (pinfunction "OUT_2") (pintype "unspecified"))
    )
    (net (code "212") (name "X14Y2") (class "Default")
      (node (ref "C419") (pin "2") (pinfunction "2_2") (pintype "input"))
      (node (ref "X14Y2") (pin "2") (pinfunction "OUT_2") (pintype "unspecified"))
    )
    (net (code "213") (name "X14Y3") (class "Default")
      (node (ref "C421") (pin "2") (pinfunction "2_2") (pintype "input"))
      (node (ref "X14Y3") (pin "2") (pinfunction "OUT_2") (pintype "unspecified"))
    )
    (net (code "214") (name "X14Y4") (class "Default")
      (node (ref "C423") (pin "2") (pinfunction "2_2") (pintype "input"))
      (node (ref "X14Y4") (pin "2") (pinfunction "OUT_2") (pintype "unspecified"))
    )
    (net (code "215") (name "X14Y5") (class "Default")
      (node (ref "C425") (pin "2") (pinfunction "2_2") (pintype "input"))
      (node (ref "X14Y5") (pin "2") (pinfunction "OUT_2") (pintype "unspecified"))
    )
    (net (code "216") (name "X14Y6") (class "Default")
      (node (ref "C427") (pin "2") (pinfunction "2_2") (pintype "input"))
      (node (ref "X14Y6") (pin "2") (pinfunction "OUT_2") (pintype "unspecified"))
    )
    (net (code "217") (name "X14Y7") (class "Default")
      (node (ref "C429") (pin "2") (pinfunction "2_2") (pintype "input"))
      (node (ref "X14Y7") (pin "2") (pinfunction "OUT_2") (pintype "unspecified"))
    )
    (net (code "218") (name "X14Y8") (class "Default")
      (node (ref "C431") (pin "2") (pinfunction "2_2") (pintype "input"))
      (node (ref "X14Y8") (pin "2") (pinfunction "OUT_2") (pintype "unspecified"))
    )
    (net (code "219") (name "X14Y9") (class "Default")
      (node (ref "C433") (pin "2") (pinfunction "2_2") (pintype "input"))
      (node (ref "X14Y9") (pin "2") (pinfunction "OUT_2") (pintype "unspecified"))
    )
    (net (code "220") (name "X14Y10") (class "Default")
      (node (ref "C435") (pin "2") (pinfunction "2_2") (pintype "input"))
      (node (ref "X14Y10") (pin "2") (pinfunction "OUT_2") (pintype "unspecified"))
    )
    (net (code "221") (name "X14Y11") (class "Default")
      (node (ref "C437") (pin "2") (pinfunction "2_2") (pintype "input"))
      (node (ref "X14Y11") (pin "2") (pinfunction "OUT_2") (pintype "unspecified"))
    )
    (net (code "222") (name "X14Y12") (class "Default")
      (node (ref "C439") (pin "2") (pinfunction "2_2") (pintype "input"))
      (node (ref "X14Y12") (pin "2") (pinfunction "OUT_2") (pintype "unspecified"))
    )
    (net (code "223") (name "X14Y13") (class "Default")
      (node (ref "C441") (pin "2") (pinfunction "2_2") (pintype "input"))
      (node (ref "X14Y13") (pin "2") (pinfunction "OUT_2") (pintype "unspecified"))
    )
    (net (code "224") (name "X14Y14") (class "Default")
      (node (ref "C443") (pin "2") (pinfunction "2_2") (pintype "input"))
      (node (ref "X14Y14") (pin "2") (pinfunction "OUT_2") (pintype "unspecified"))
    )
    (net (code "225") (name "X14Y15") (class "Default")
      (node (ref "C445") (pin "2") (pinfunction "2_2") (pintype "input"))
      (node (ref "X14Y15") (pin "2") (pinfunction "OUT_2") (pintype "unspecified"))
    )
    (net (code "226") (name "X14Y16") (class "Default")
      (node (ref "C447") (pin "2") (pinfunction "2_2") (pintype "input"))
      (node (ref "X14Y16") (pin "2") (pinfunction "OUT_2") (pintype "unspecified"))
    )
    (net (code "227") (name "X15Y1") (class "Default")
      (node (ref "C449") (pin "2") (pinfunction "2_2") (pintype "input"))
      (node (ref "X15Y1") (pin "2") (pinfunction "OUT_2") (pintype "unspecified"))
    )
    (net (code "228") (name "X15Y2") (class "Default")
      (node (ref "C452") (pin "2") (pinfunction "2_2") (pintype "input"))
      (node (ref "X15Y2") (pin "2") (pinfunction "OUT_2") (pintype "unspecified"))
    )
    (net (code "229") (name "X15Y3") (class "Default")
      (node (ref "C454") (pin "2") (pinfunction "2_2") (pintype "input"))
      (node (ref "X15Y3") (pin "2") (pinfunction "OUT_2") (pintype "unspecified"))
    )
    (net (code "230") (name "X15Y4") (class "Default")
      (node (ref "C456") (pin "2") (pinfunction "2_2") (pintype "input"))
      (node (ref "X15Y4") (pin "2") (pinfunction "OUT_2") (pintype "unspecified"))
    )
    (net (code "231") (name "X15Y5") (class "Default")
      (node (ref "C458") (pin "2") (pinfunction "2_2") (pintype "input"))
      (node (ref "X15Y5") (pin "2") (pinfunction "OUT_2") (pintype "unspecified"))
    )
    (net (code "232") (name "X15Y6") (class "Default")
      (node (ref "C460") (pin "2") (pinfunction "2_2") (pintype "input"))
      (node (ref "X15Y6") (pin "2") (pinfunction "OUT_2") (pintype "unspecified"))
    )
    (net (code "233") (name "X15Y7") (class "Default")
      (node (ref "C462") (pin "2") (pinfunction "2_2") (pintype "input"))
      (node (ref "X15Y7") (pin "2") (pinfunction "OUT_2") (pintype "unspecified"))
    )
    (net (code "234") (name "X15Y8") (class "Default")
      (node (ref "C464") (pin "2") (pinfunction "2_2") (pintype "input"))
      (node (ref "X15Y8") (pin "2") (pinfunction "OUT_2") (pintype "unspecified"))
    )
    (net (code "235") (name "X15Y9") (class "Default")
      (node (ref "C466") (pin "2") (pinfunction "2_2") (pintype "input"))
      (node (ref "X15Y9") (pin "2") (pinfunction "OUT_2") (pintype "unspecified"))
    )
    (net (code "236") (name "X15Y10") (class "Default")
      (node (ref "C468") (pin "2") (pinfunction "2_2") (pintype "input"))
      (node (ref "X15Y10") (pin "2") (pinfunction "OUT_2") (pintype "unspecified"))
    )
    (net (code "237") (name "X15Y11") (class "Default")
      (node (ref "C470") (pin "2") (pinfunction "2_2") (pintype "input"))
      (node (ref "X15Y11") (pin "2") (pinfunction "OUT_2") (pintype "unspecified"))
    )
    (net (code "238") (name "X15Y12") (class "Default")
      (node (ref "C472") (pin "2") (pinfunction "2_2") (pintype "input"))
      (node (ref "X15Y12") (pin "2") (pinfunction "OUT_2") (pintype "unspecified"))
    )
    (net (code "239") (name "X15Y13") (class "Default")
      (node (ref "C474") (pin "2") (pinfunction "2_2") (pintype "input"))
      (node (ref "X15Y13") (pin "2") (pinfunction "OUT_2") (pintype "unspecified"))
    )
    (net (code "240") (name "X15Y14") (class "Default")
      (node (ref "C476") (pin "2") (pinfunction "2_2") (pintype "input"))
      (node (ref "X15Y14") (pin "2") (pinfunction "OUT_2") (pintype "unspecified"))
    )
    (net (code "241") (name "X15Y15") (class "Default")
      (node (ref "C478") (pin "2") (pinfunction "2_2") (pintype "input"))
      (node (ref "X15Y15") (pin "2") (pinfunction "OUT_2") (pintype "unspecified"))
    )
    (net (code "242") (name "X15Y16") (class "Default")
      (node (ref "C480") (pin "2") (pinfunction "2_2") (pintype "input"))
      (node (ref "X15Y16") (pin "2") (pinfunction "OUT_2") (pintype "unspecified"))
    )
    (net (code "243") (name "X16Y1") (class "Default")
      (node (ref "C482") (pin "2") (pinfunction "2_2") (pintype "input"))
      (node (ref "X16Y1") (pin "2") (pinfunction "OUT_2") (pintype "unspecified"))
    )
    (net (code "244") (name "X16Y2") (class "Default")
      (node (ref "C483") (pin "2") (pinfunction "2_2") (pintype "input"))
      (node (ref "X16Y2") (pin "2") (pinfunction "OUT_2") (pintype "unspecified"))
    )
    (net (code "245") (name "X16Y3") (class "Default")
      (node (ref "C485") (pin "2") (pinfunction "2_2") (pintype "input"))
      (node (ref "X16Y3") (pin "2") (pinfunction "OUT_2") (pintype "unspecified"))
    )
    (net (code "246") (name "X16Y4") (class "Default")
      (node (ref "C487") (pin "2") (pinfunction "2_2") (pintype "input"))
      (node (ref "X16Y4") (pin "2") (pinfunction "OUT_2") (pintype "unspecified"))
    )
    (net (code "247") (name "X16Y5") (class "Default")
      (node (ref "C489") (pin "2") (pinfunction "2_2") (pintype "input"))
      (node (ref "X16Y5") (pin "2") (pinfunction "OUT_2") (pintype "unspecified"))
    )
    (net (code "248") (name "X16Y6") (class "Default")
      (node (ref "C491") (pin "2") (pinfunction "2_2") (pintype "input"))
      (node (ref "X16Y6") (pin "2") (pinfunction "OUT_2") (pintype "unspecified"))
    )
    (net (code "249") (name "X16Y7") (class "Default")
      (node (ref "C493") (pin "2") (pinfunction "2_2") (pintype "input"))
      (node (ref "X16Y7") (pin "2") (pinfunction "OUT_2") (pintype "unspecified"))
    )
    (net (code "250") (name "X16Y8") (class "Default")
      (node (ref "C495") (pin "2") (pinfunction "2_2") (pintype "input"))
      (node (ref "X16Y8") (pin "2") (pinfunction "OUT_2") (pintype "unspecified"))
    )
    (net (code "251") (name "X16Y9") (class "Default")
      (node (ref "C497") (pin "2") (pinfunction "2_2") (pintype "input"))
      (node (ref "X16Y9") (pin "2") (pinfunction "OUT_2") (pintype "unspecified"))
    )
    (net (code "252") (name "X16Y10") (class "Default")
      (node (ref "C499") (pin "2") (pinfunction "2_2") (pintype "input"))
      (node (ref "X16Y10") (pin "2") (pinfunction "OUT_2") (pintype "unspecified"))
    )
    (net (code "253") (name "X16Y11") (class "Default")
      (node (ref "C501") (pin "2") (pinfunction "2_2") (pintype "input"))
      (node (ref "X16Y11") (pin "2") (pinfunction "OUT_2") (pintype "unspecified"))
    )
    (net (code "254") (name "X16Y12") (class "Default")
      (node (ref "C503") (pin "2") (pinfunction "2_2") (pintype "input"))
      (node (ref "X16Y12") (pin "2") (pinfunction "OUT_2") (pintype "unspecified"))
    )
    (net (code "255") (name "X16Y13") (class "Default")
      (node (ref "C505") (pin "2") (pinfunction "2_2") (pintype "input"))
      (node (ref "X16Y13") (pin "2") (pinfunction "OUT_2") (pintype "unspecified"))
    )
    (net (code "256") (name "X16Y14") (class "Default")
      (node (ref "C507") (pin "2") (pinfunction "2_2") (pintype "input"))
      (node (ref "X16Y14") (pin "2") (pinfunction "OUT_2") (pintype "unspecified"))
    )
    (net (code "257") (name "X16Y15") (class "Default")
      (node (ref "C509") (pin "2") (pinfunction "2_2") (pintype "input"))
      (node (ref "X16Y15") (pin "2") (pinfunction "OUT_2") (pintype "unspecified"))
    )
    (net (code "258") (name "X16Y16") (class "Default")
      (node (ref "C511") (pin "2") (pinfunction "2_2") (pintype "input"))
      (node (ref "X16Y16") (pin "2") (pinfunction "OUT_2") (pintype "unspecified"))
    )
  )
)
